# EEZ_DIB_DCP505_r1B3.net
KiCad netlist of a schematic drawn in EAGLE
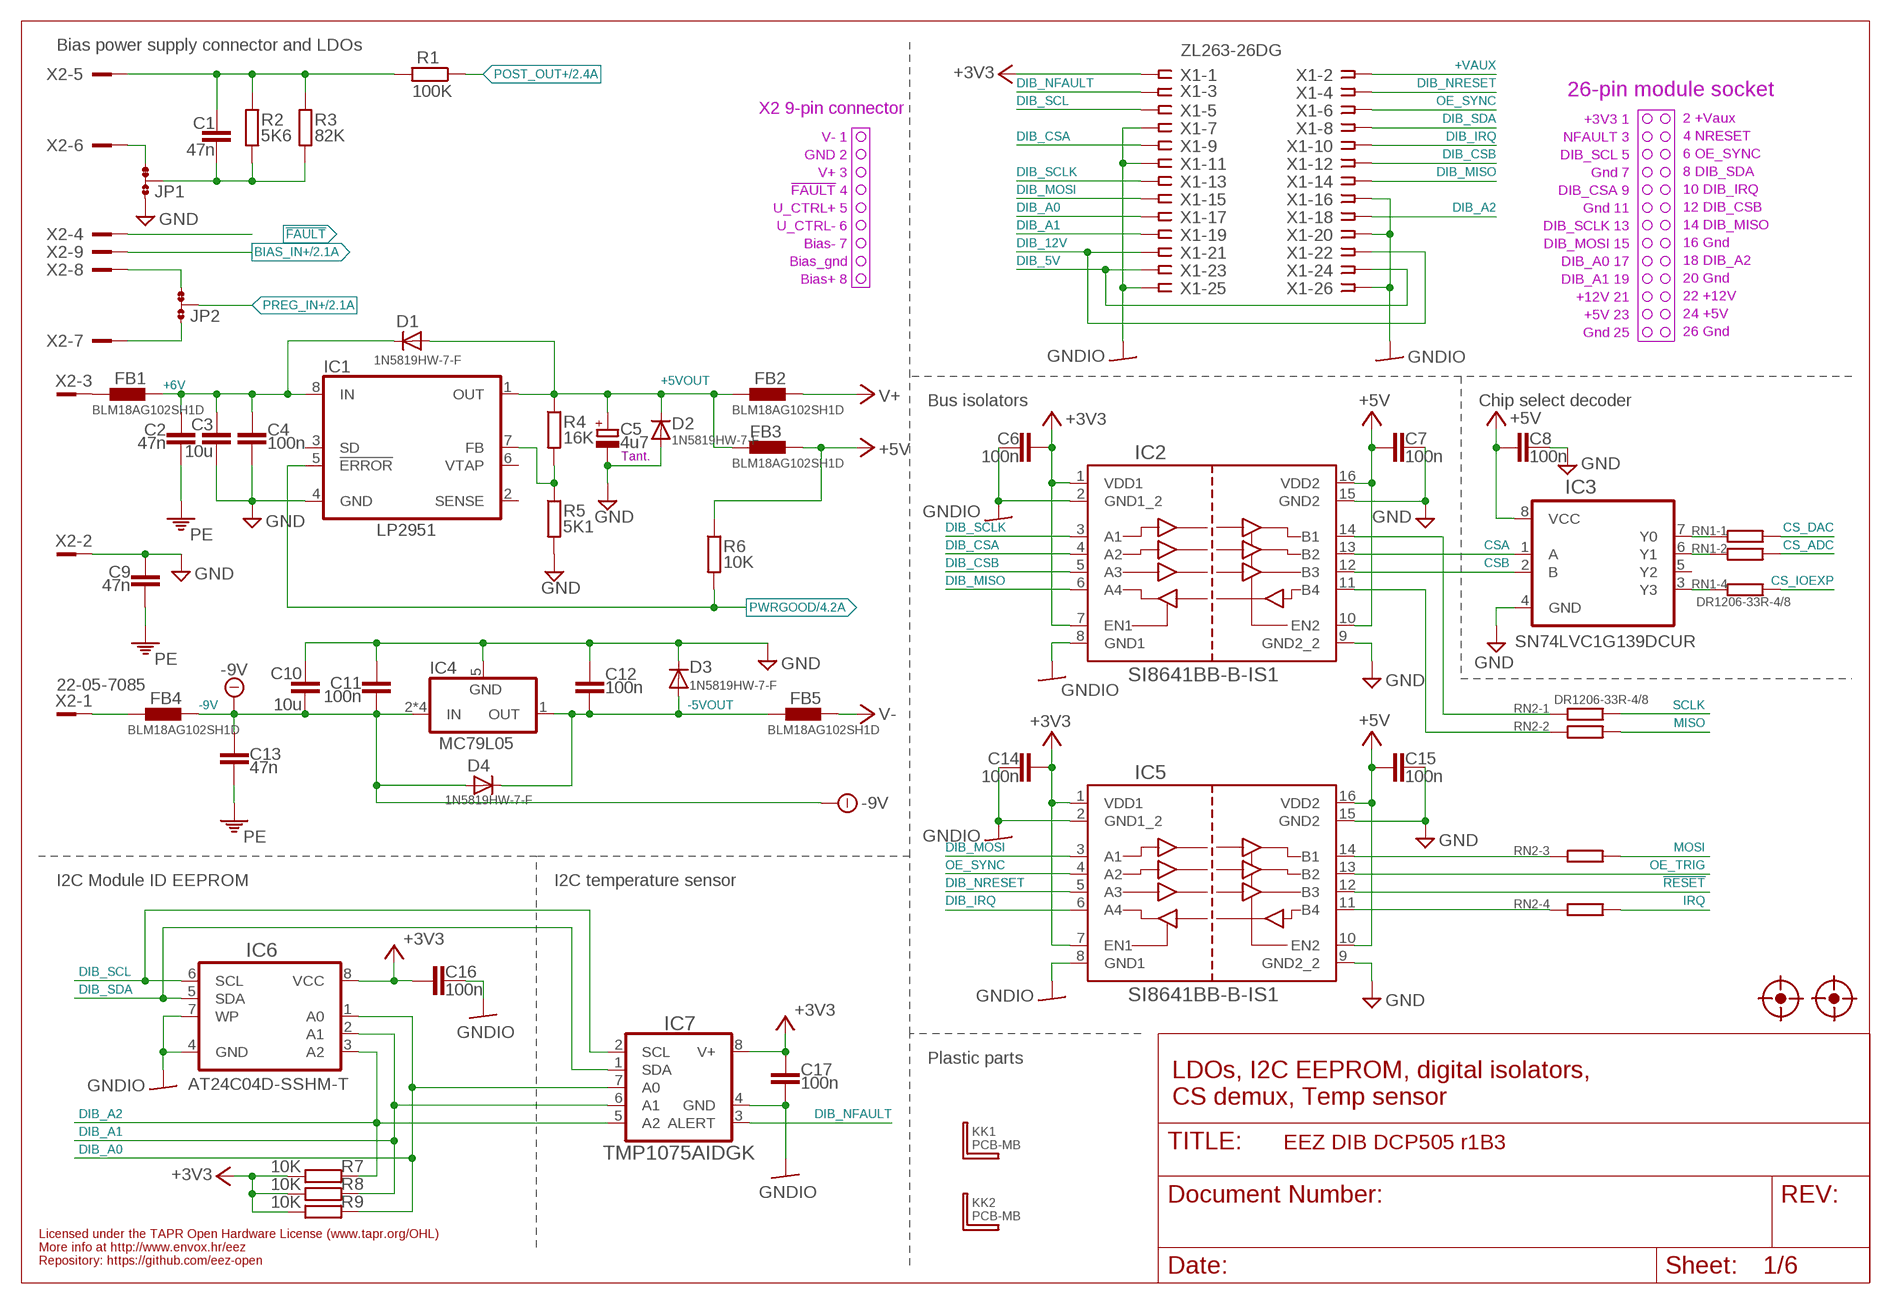
[diagram p0: schematic, sheet 1]
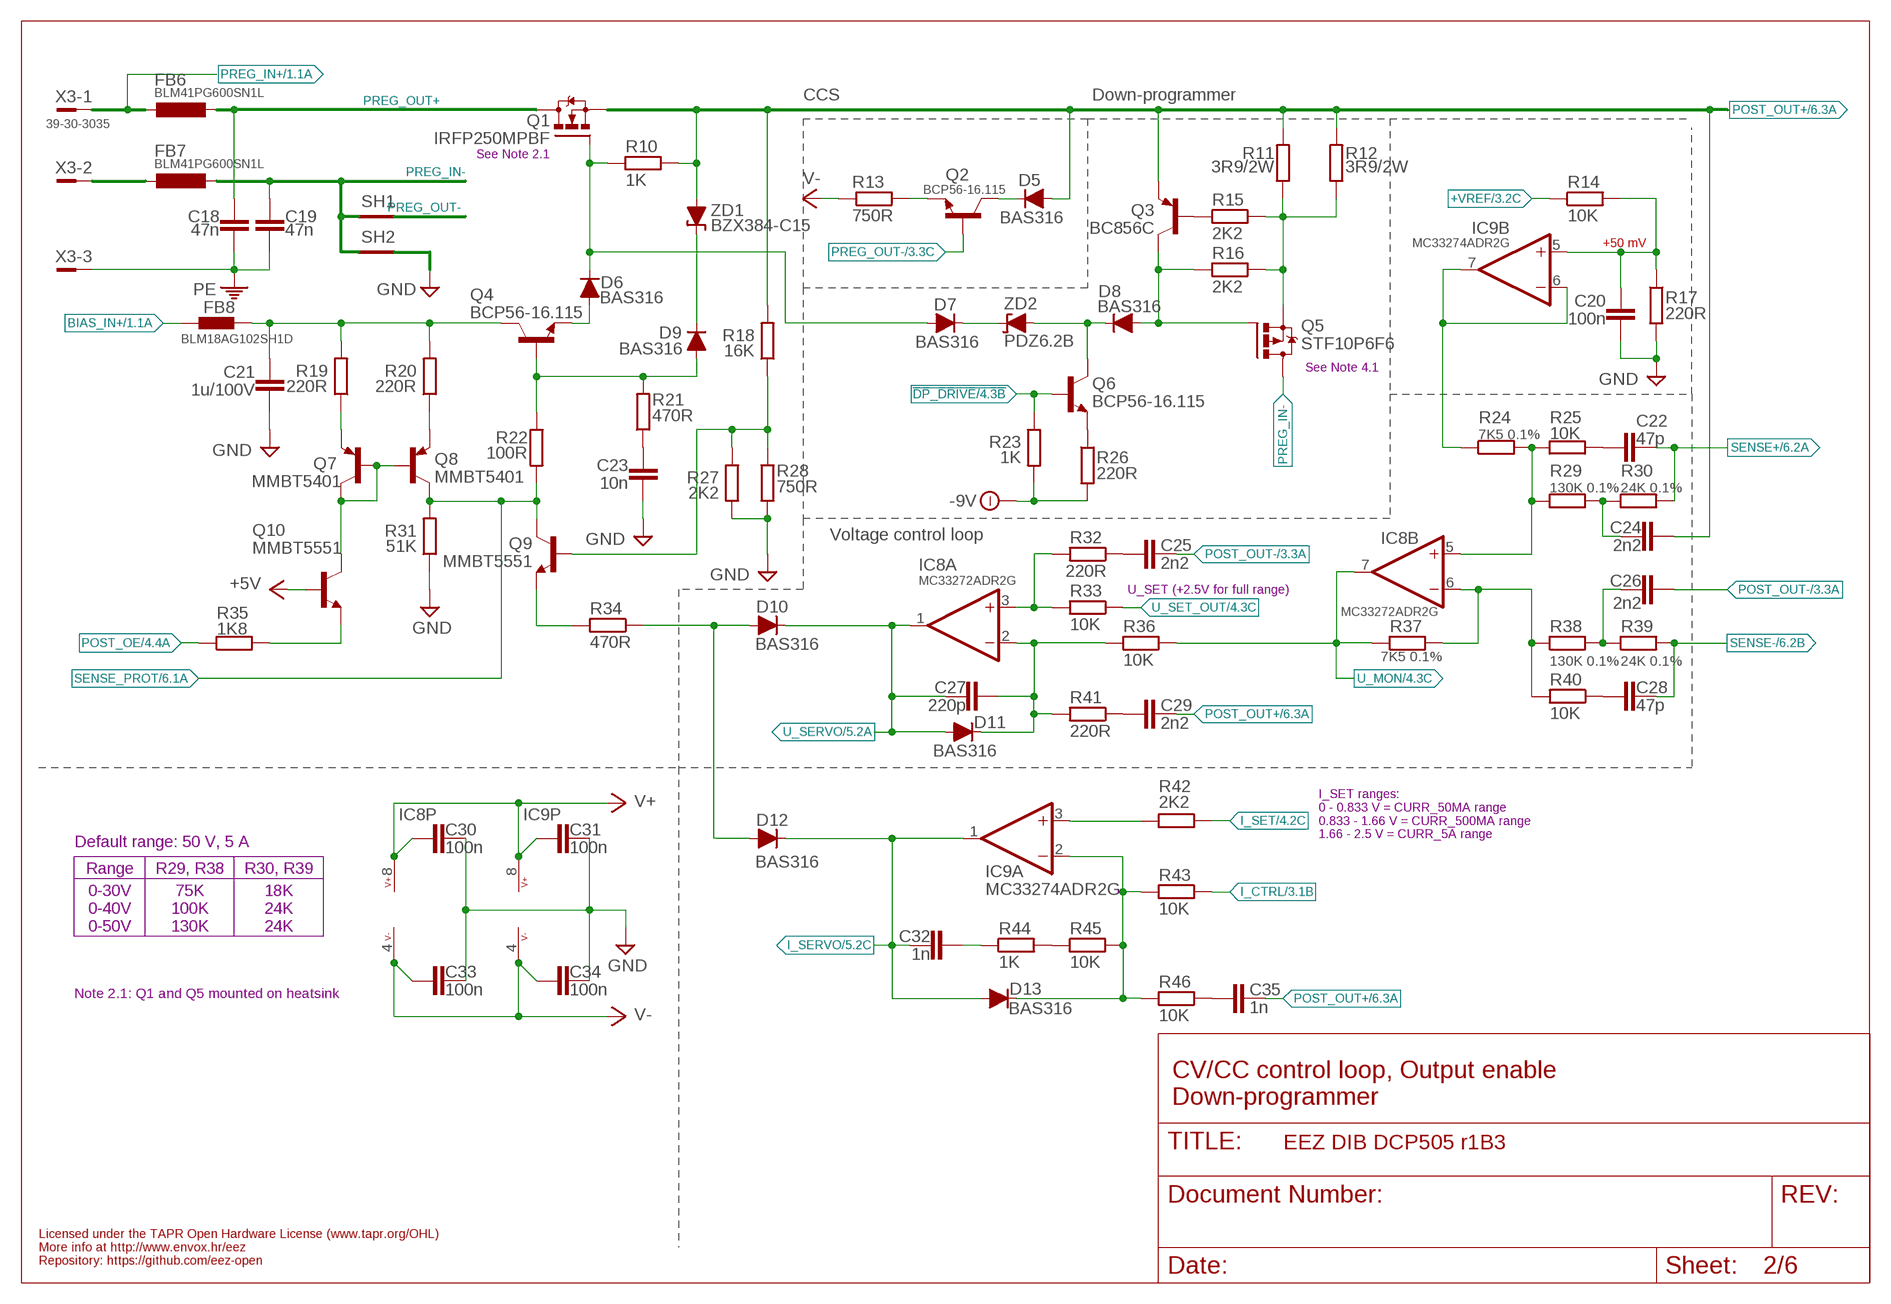
[diagram p1: schematic, sheet 2]
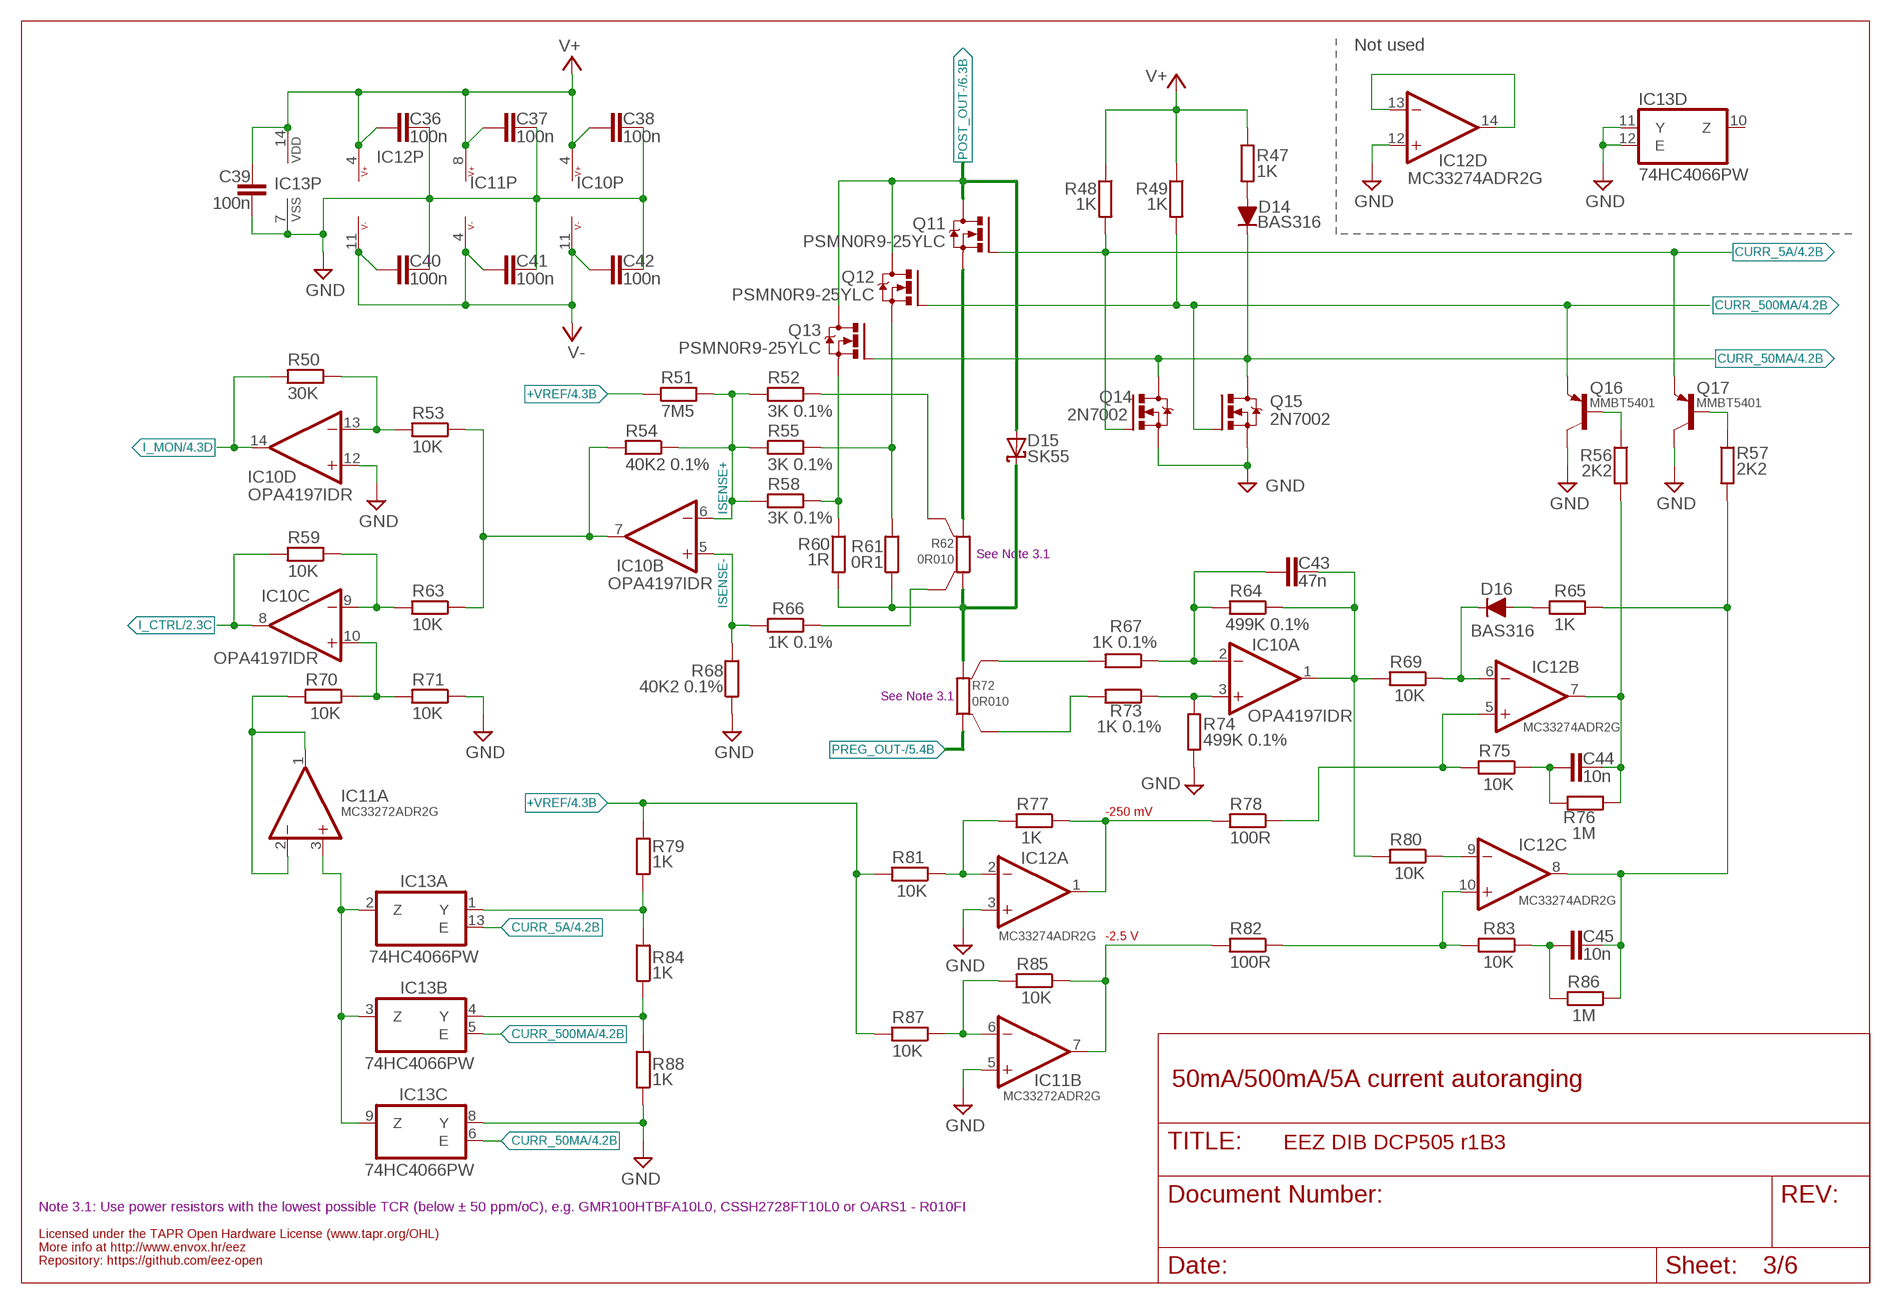
[diagram p2: schematic, sheet 3]
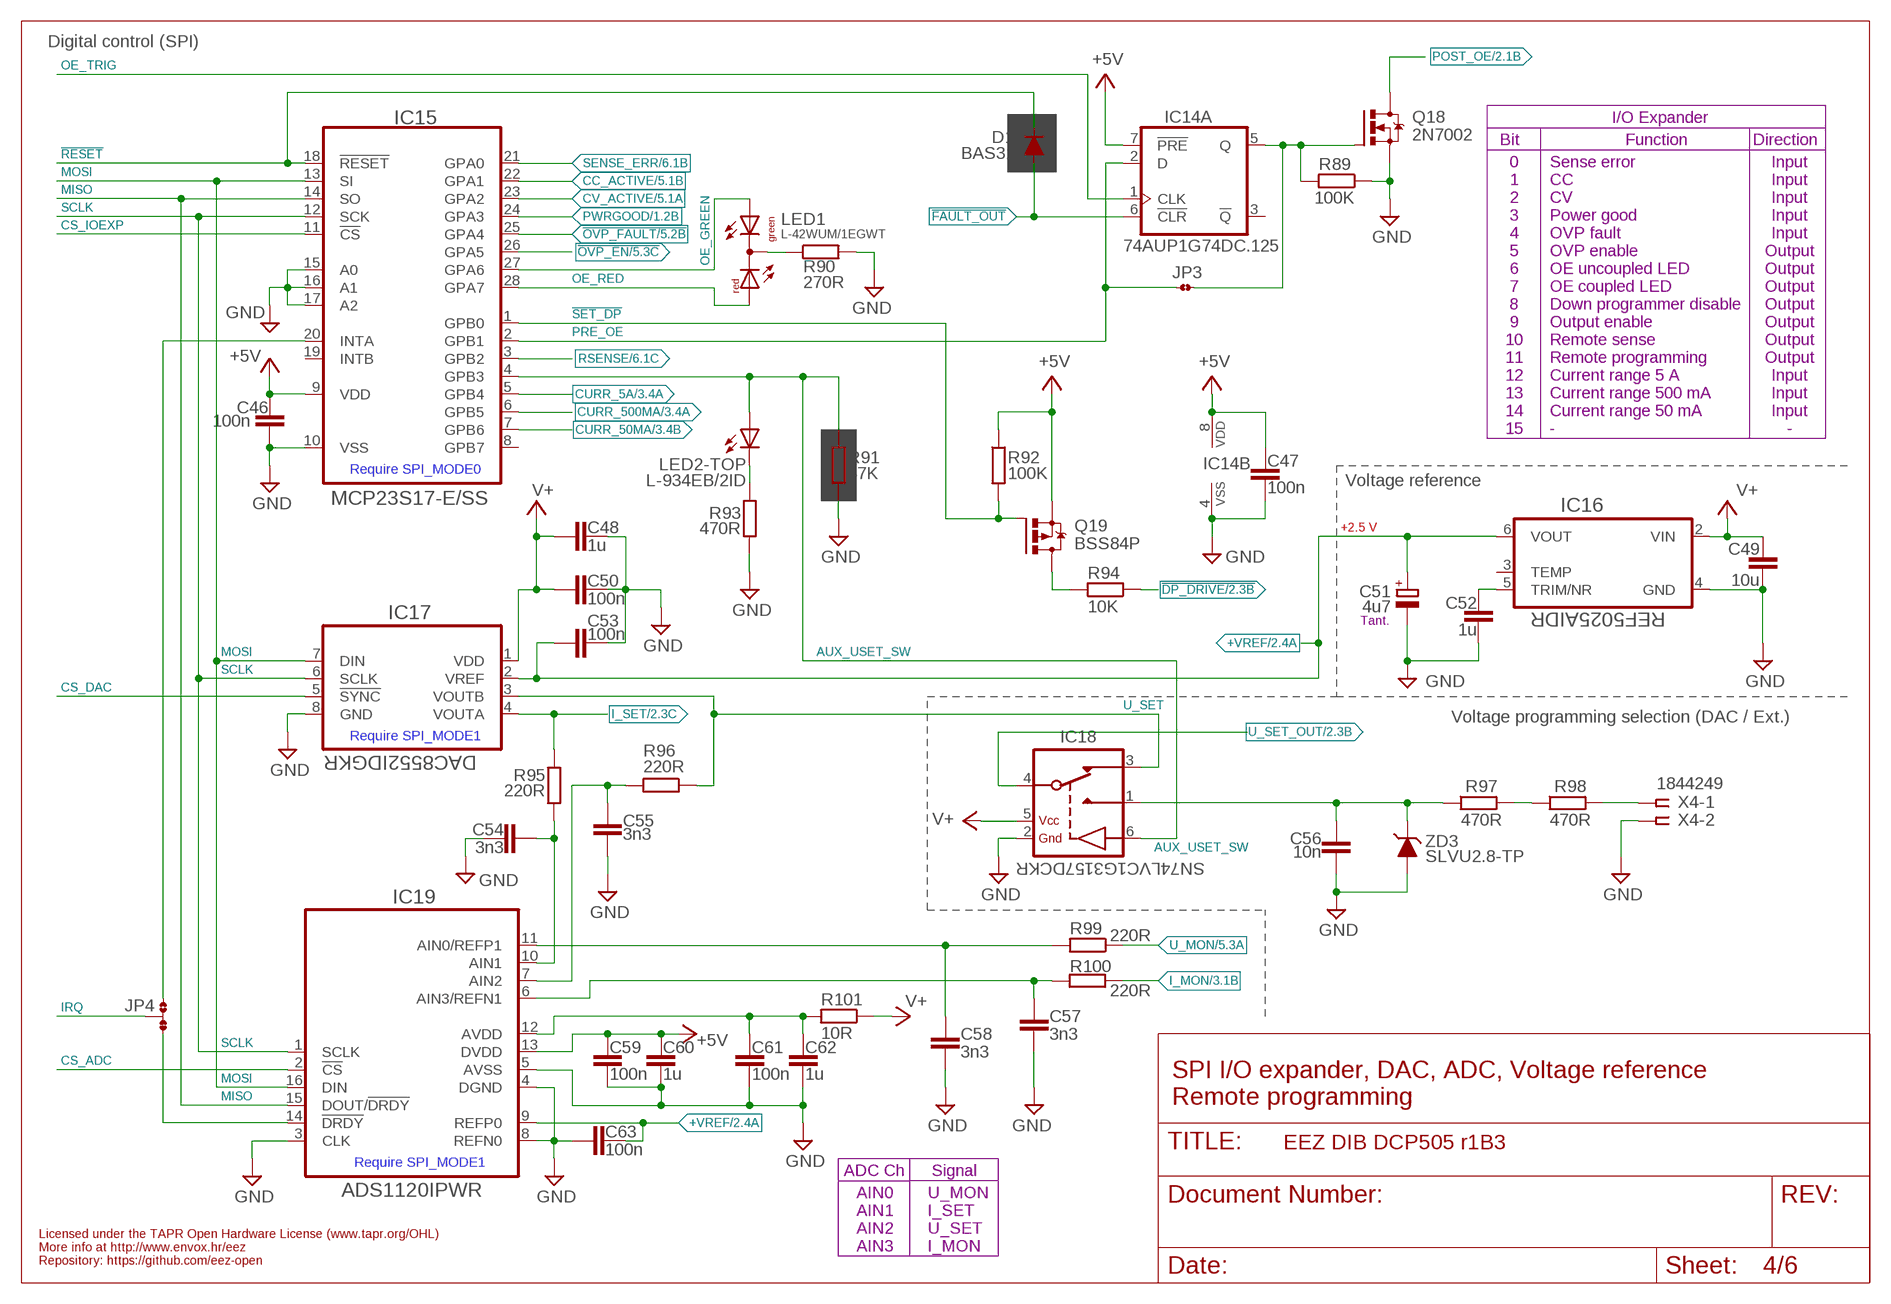
[diagram p3: schematic, sheet 4]
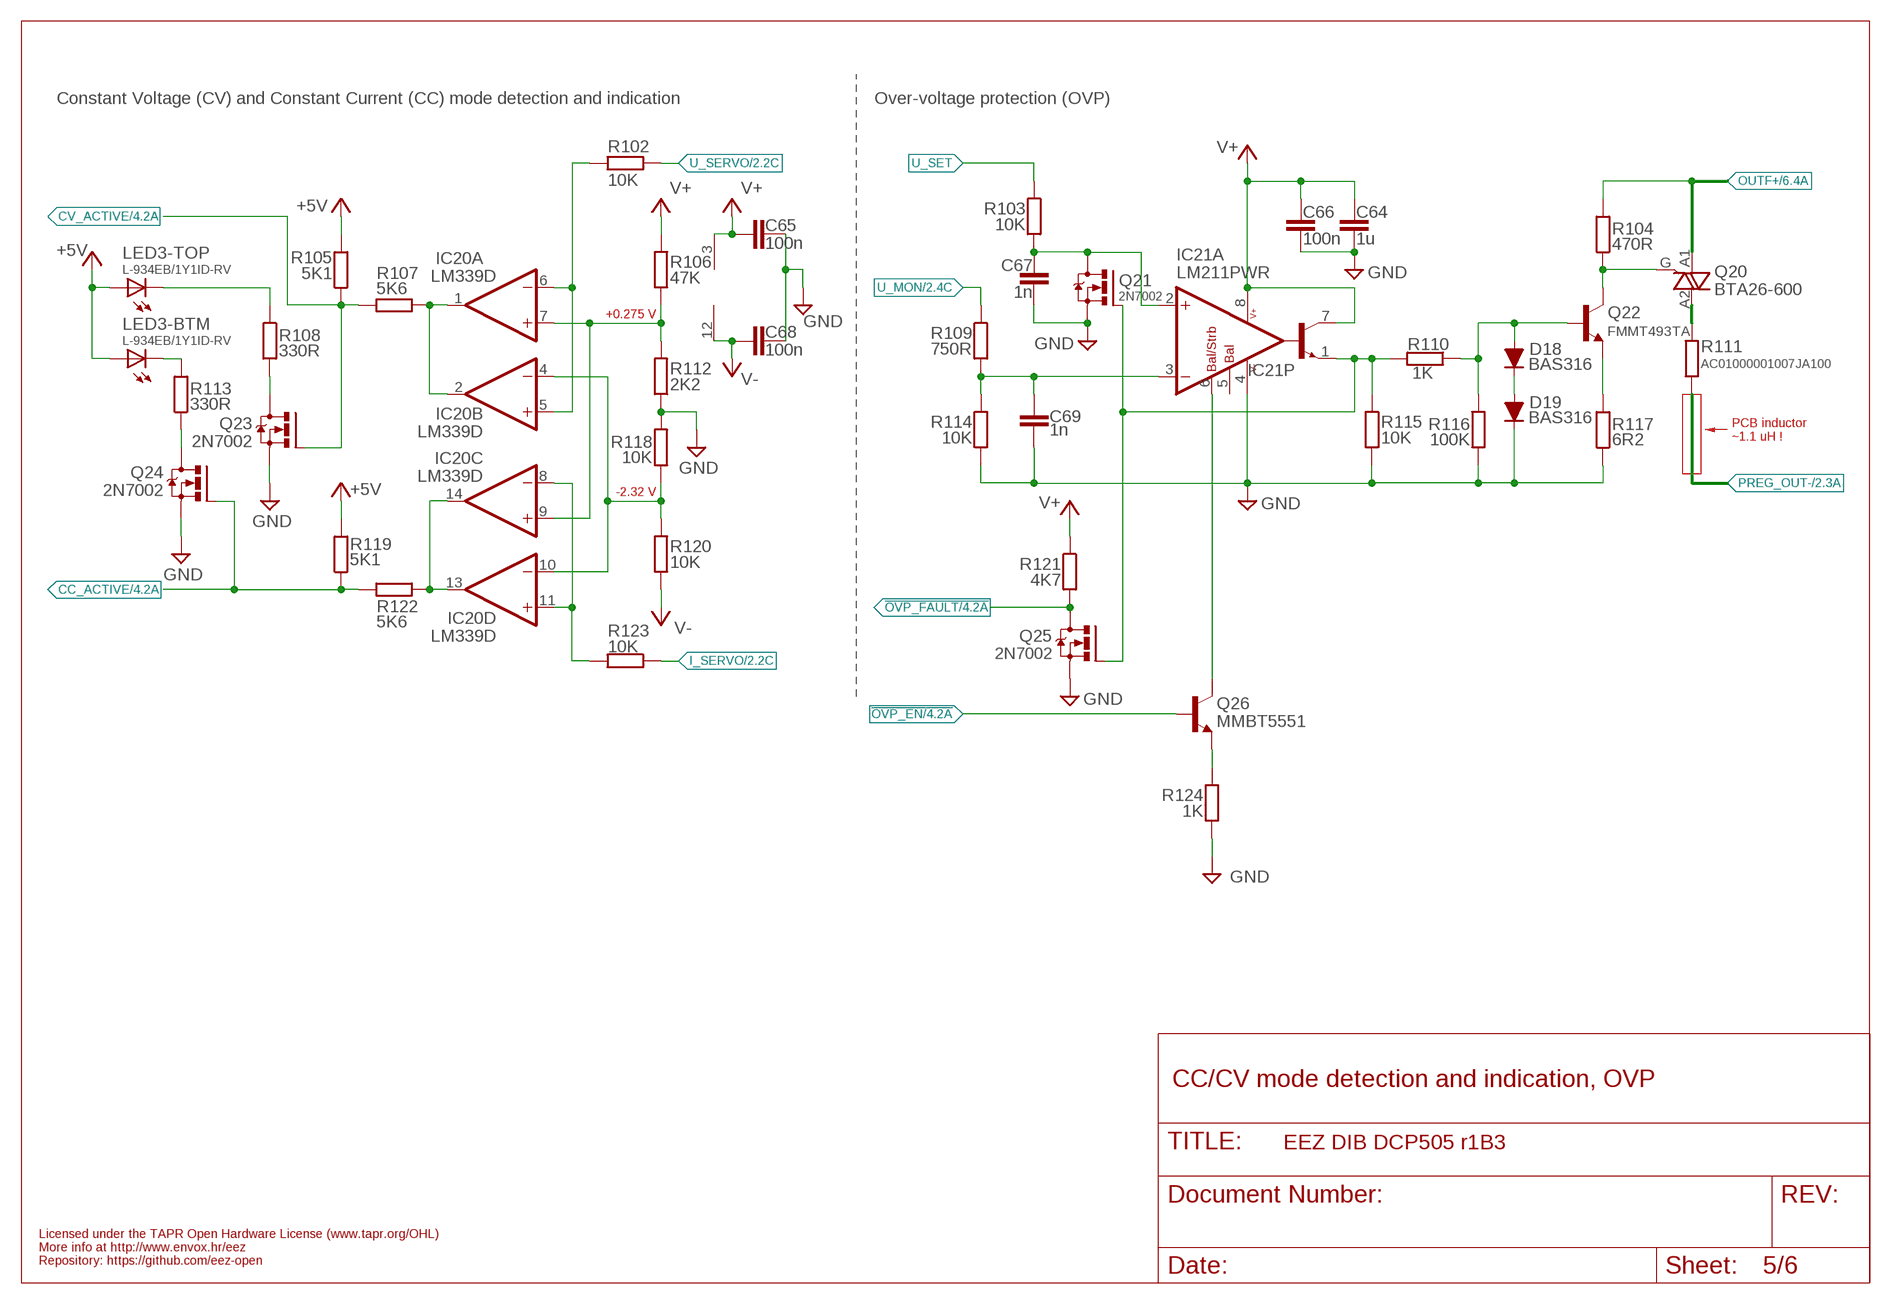
[diagram p4: schematic, sheet 5]
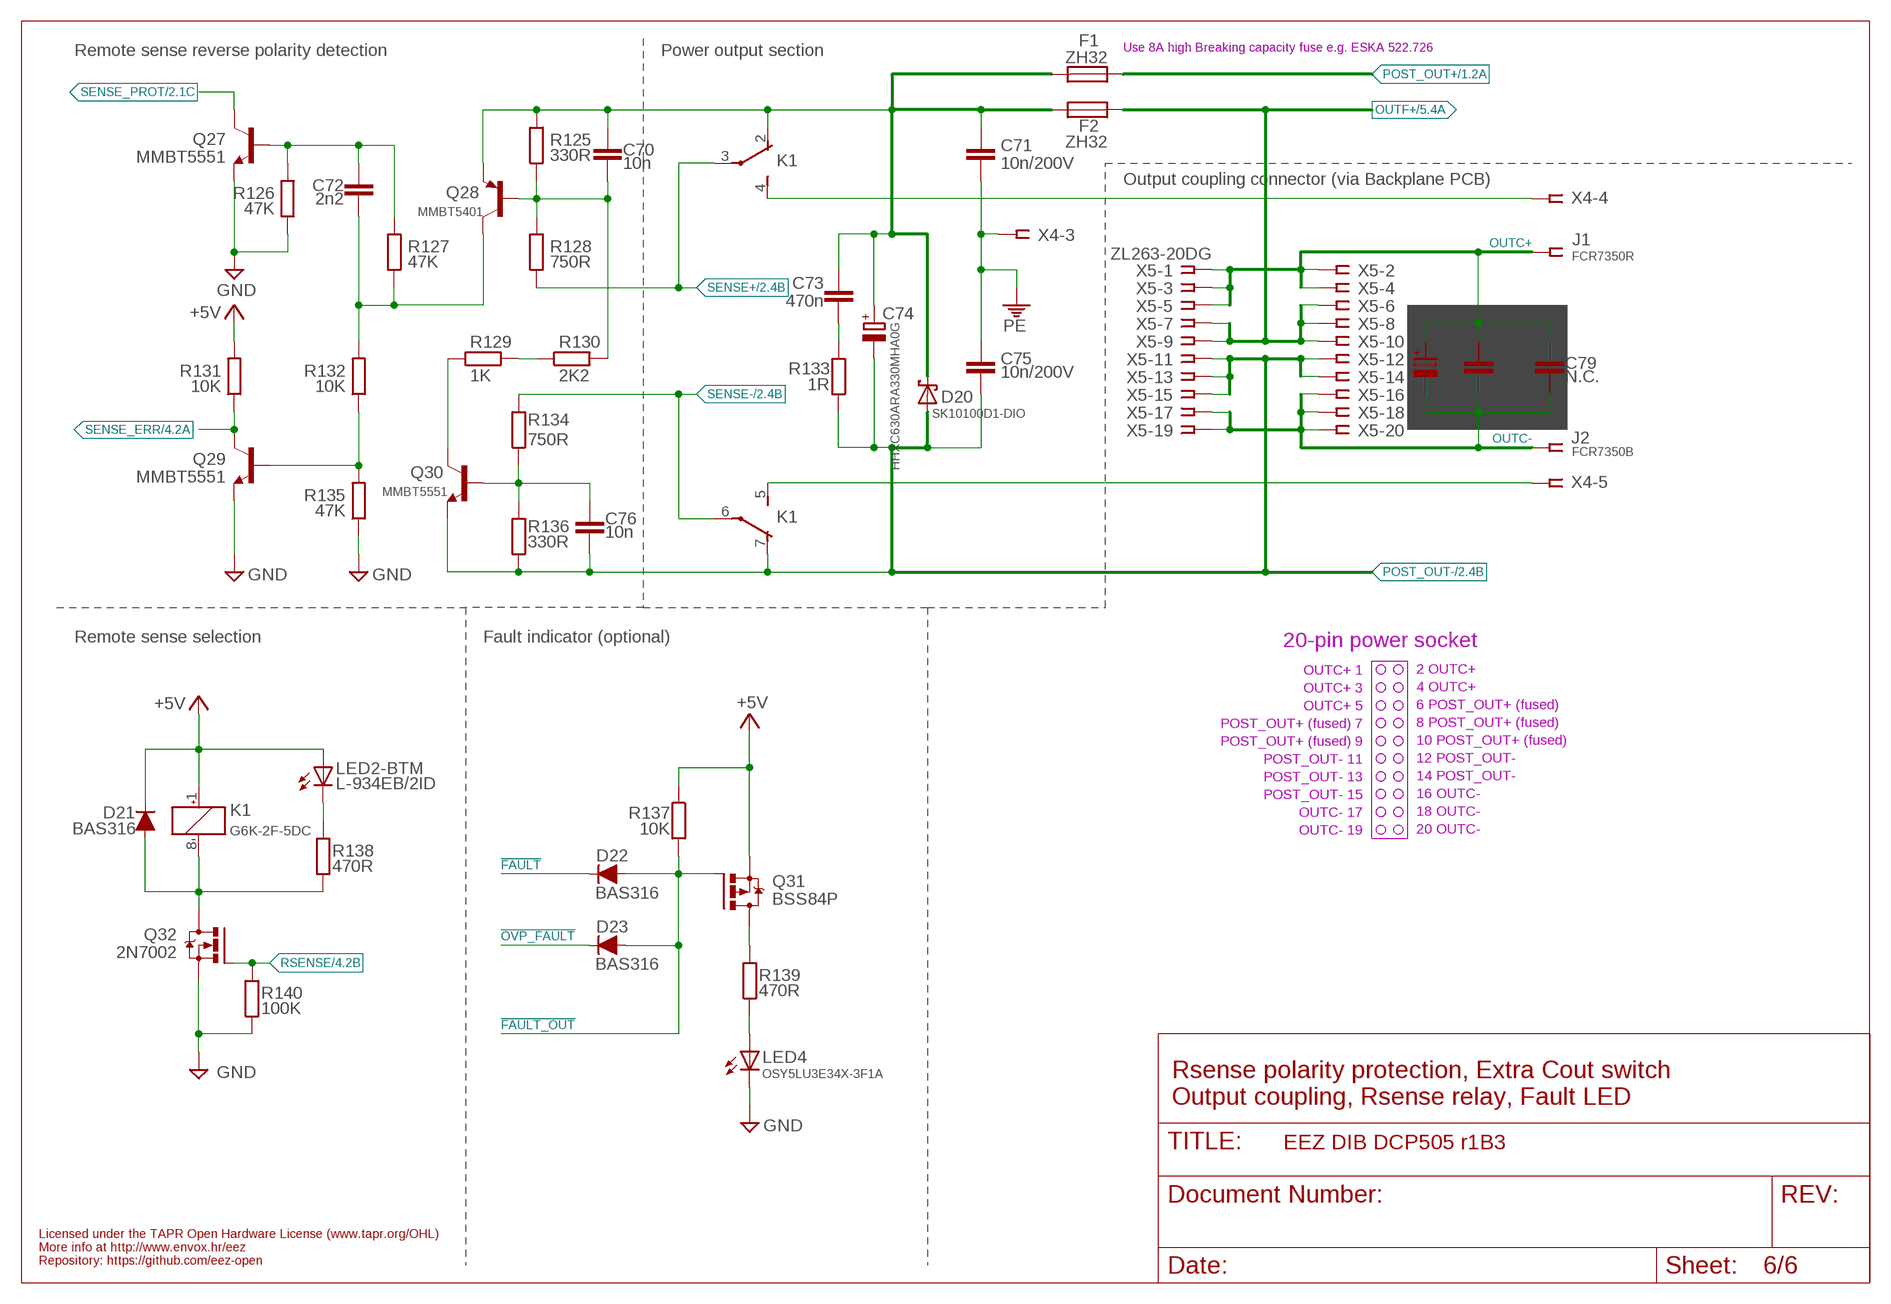
[diagram p5: schematic, sheet 6]

(export (version "E")
  (design (tool "Eeschema 10.0.6"))
  (components
    (comp (ref "C1")
      (value "47n")
      (footprint "eagle-import:C0805")
      (libsource (lib "eagle-import") (part "C-EUC0805"))
    )
    (comp (ref "C2")
      (value "47n")
      (footprint "eagle-import:C1206")
      (libsource (lib "eagle-import") (part "C-EUC1206"))
    )
    (comp (ref "C3")
      (value "10u")
      (footprint "eagle-import:C1206")
      (libsource (lib "eagle-import") (part "C-EUC1206"))
    )
    (comp (ref "C4")
      (value "100n")
      (footprint "eagle-import:C0603")
      (libsource (lib "eagle-import") (part "C-EUC0603"))
    )
    (comp (ref "C5")
      (value "4u7")
      (footprint "eagle-import:EC1206")
      (libsource (lib "eagle-import") (part "ECAP1206"))
    )
    (comp (ref "C6")
      (value "100n")
      (footprint "eagle-import:C0603")
      (libsource (lib "eagle-import") (part "C-EUC0603"))
    )
    (comp (ref "C7")
      (value "100n")
      (footprint "eagle-import:C0603")
      (libsource (lib "eagle-import") (part "C-EUC0603"))
    )
    (comp (ref "C8")
      (value "100n")
      (footprint "eagle-import:C0603")
      (libsource (lib "eagle-import") (part "C-EUC0603"))
    )
    (comp (ref "C9")
      (value "47n")
      (footprint "eagle-import:C1206")
      (libsource (lib "eagle-import") (part "C-EUC1206"))
    )
    (comp (ref "C10")
      (value "10u")
      (footprint "eagle-import:C1206")
      (libsource (lib "eagle-import") (part "C-EUC1206"))
    )
    (comp (ref "C11")
      (value "100n")
      (footprint "eagle-import:C0603")
      (libsource (lib "eagle-import") (part "C-EUC0603"))
    )
    (comp (ref "C12")
      (value "100n")
      (footprint "eagle-import:C0603")
      (libsource (lib "eagle-import") (part "C-EUC0603"))
    )
    (comp (ref "C13")
      (value "47n")
      (footprint "eagle-import:C1206")
      (libsource (lib "eagle-import") (part "C-EUC1206"))
    )
    (comp (ref "C14")
      (value "100n")
      (footprint "eagle-import:C0603")
      (libsource (lib "eagle-import") (part "C-EUC0603"))
    )
    (comp (ref "C15")
      (value "100n")
      (footprint "eagle-import:C0603")
      (libsource (lib "eagle-import") (part "C-EUC0603"))
    )
    (comp (ref "C16")
      (value "100n")
      (footprint "eagle-import:C0603")
      (libsource (lib "eagle-import") (part "C-EUC0603"))
    )
    (comp (ref "C17")
      (value "100n")
      (footprint "eagle-import:C0603")
      (libsource (lib "eagle-import") (part "C-EUC0603"))
    )
    (comp (ref "D1")
      (value "1N5819HW-7-F")
      (footprint "eagle-import:SOD323-W")
      (libsource (lib "eagle-import") (part "DIODE-SOD323-W"))
    )
    (comp (ref "D2")
      (value "1N5819HW-7-F")
      (footprint "eagle-import:SOD323-W")
      (libsource (lib "eagle-import") (part "DIODE-SOD323-W"))
    )
    (comp (ref "D3")
      (value "1N5819HW-7-F")
      (footprint "eagle-import:SOD323-W")
      (libsource (lib "eagle-import") (part "DIODE-SOD323-W"))
    )
    (comp (ref "D4")
      (value "1N5819HW-7-F")
      (footprint "eagle-import:SOD323-W")
      (libsource (lib "eagle-import") (part "DIODE-SOD323-W"))
    )
    (comp (ref "FB1")
      (value "BLM18AG102SH1D")
      (footprint "eagle-import:BEAD0603")
      (libsource (lib "eagle-import") (part "EEZ_inductors_and_transformers_FERRITE_BEAD0603"))
    )
    (comp (ref "FB2")
      (value "BLM18AG102SH1D")
      (footprint "eagle-import:BEAD0603")
      (libsource (lib "eagle-import") (part "EEZ_inductors_and_transformers_FERRITE_BEAD0603"))
    )
    (comp (ref "FB3")
      (value "BLM18AG102SH1D")
      (footprint "eagle-import:BEAD0603")
      (libsource (lib "eagle-import") (part "EEZ_inductors_and_transformers_FERRITE_BEAD0603"))
    )
    (comp (ref "FB4")
      (value "BLM18AG102SH1D")
      (footprint "eagle-import:BEAD0603")
      (libsource (lib "eagle-import") (part "EEZ_inductors_and_transformers_FERRITE_BEAD0603"))
    )
    (comp (ref "FB5")
      (value "BLM18AG102SH1D")
      (footprint "eagle-import:BEAD0603")
      (libsource (lib "eagle-import") (part "EEZ_inductors_and_transformers_FERRITE_BEAD0603"))
    )
    (comp (ref "FM1")
      (value "FIDUCIAL_2")
      (footprint "eagle-import:FIDUCIAL_DUAL")
      (libsource (lib "eagle-import") (part "FIDUCIAL_2"))
    )
    (comp (ref "FM2")
      (value "FIDUCIAL_2")
      (footprint "eagle-import:FIDUCIAL_DUAL")
      (libsource (lib "eagle-import") (part "FIDUCIAL_2"))
    )
    (comp (ref "IC1")
      (value "LP2951")
      (footprint "eagle-import:SOIC127P600X175-8N")
      (libsource (lib "eagle-import") (part "LP2951SO8"))
    )
    (comp (ref "IC2")
      (value "SI8641BB-B-IS1")
      (footprint "eagle-import:SOIC-16")
      (libsource (lib "eagle-import") (part "SI8641NSOIC-16"))
    )
    (comp (ref "IC3")
      (value "SN74LVC1G139DCUR")
      (footprint "eagle-import:DCU8")
      (libsource (lib "eagle-import") (part "SN74LVC1G139-VSSOP"))
    )
    (comp (ref "IC4")
      (value "MC79L05")
      (footprint "eagle-import:SOIC127P600X173-8N")
      (libsource (lib "eagle-import") (part "MC79LXXSOIC"))
    )
    (comp (ref "IC5")
      (value "SI8641BB-B-IS1")
      (footprint "eagle-import:SOIC-16")
      (libsource (lib "eagle-import") (part "SI8641NSOIC-16"))
    )
    (comp (ref "IC6")
      (value "AT24C04D-SSHM-T")
      (footprint "eagle-import:SOIC127P600X173-8N")
      (libsource (lib "eagle-import") (part "AT24CXXSOIC8"))
    )
    (comp (ref "IC7")
      (value "TMP1075AIDGK")
      (footprint "eagle-import:DGK8")
      (libsource (lib "eagle-import") (part "TMPX75DGK"))
    )
    (comp (ref "JP1")
      (value "JP3-CUT")
      (footprint "eagle-import:JP3-CUT")
      (libsource (lib "eagle-import") (part "JP3-CUT"))
    )
    (comp (ref "JP2")
      (value "JP3-CUT")
      (footprint "eagle-import:JP3-CUT")
      (libsource (lib "eagle-import") (part "JP3-CUT"))
    )
    (comp (ref "KK1")
      (value "PCB-MB")
      (footprint "eagle-import:PCB-MB")
      (libsource (lib "eagle-import") (part "PCB-MB"))
    )
    (comp (ref "KK2")
      (value "PCB-MB")
      (footprint "eagle-import:PCB-MB")
      (libsource (lib "eagle-import") (part "PCB-MB"))
    )
    (comp (ref "R1")
      (value "100K")
      (footprint "eagle-import:R0805")
      (libsource (lib "eagle-import") (part "R-EU_R0805"))
    )
    (comp (ref "R2")
      (value "5K6")
      (footprint "eagle-import:R0805")
      (libsource (lib "eagle-import") (part "R-EU_R0805"))
    )
    (comp (ref "R3")
      (value "82K")
      (footprint "eagle-import:R0805")
      (libsource (lib "eagle-import") (part "R-EU_R0805"))
    )
    (comp (ref "R4")
      (value "16K")
      (footprint "eagle-import:R0805")
      (libsource (lib "eagle-import") (part "R-EU_R0805"))
    )
    (comp (ref "R5")
      (value "5K1")
      (footprint "eagle-import:R0805")
      (libsource (lib "eagle-import") (part "R-EU_R0805"))
    )
    (comp (ref "R6")
      (value "10K")
      (footprint "eagle-import:R0805")
      (libsource (lib "eagle-import") (part "R-EU_R0805"))
    )
    (comp (ref "R7")
      (value "10K")
      (footprint "eagle-import:R0805")
      (libsource (lib "eagle-import") (part "R-EU_R0805"))
    )
    (comp (ref "R8")
      (value "10K")
      (footprint "eagle-import:R0805")
      (libsource (lib "eagle-import") (part "R-EU_R0805"))
    )
    (comp (ref "R9")
      (value "10K")
      (footprint "eagle-import:R0805")
      (libsource (lib "eagle-import") (part "R-EU_R0805"))
    )
    (comp (ref "RN1")
      (value "DR1206-33R-4/8")
      (footprint "eagle-import:CAY16")
      (libsource (lib "eagle-import") (part "R_ARRAY4"))
    )
    (comp (ref "RN2")
      (value "DR1206-33R-4/8")
      (footprint "eagle-import:CAY16")
      (libsource (lib "eagle-import") (part "R_ARRAY4"))
    )
    (comp (ref "X1")
      (value "ZL263-26DG")
      (footprint "eagle-import:SSW-113-02-T-D-RA")
      (libsource (lib "eagle-import") (part "SSW-113-02-T-D-RA"))
    )
    (comp (ref "X2")
      (value "22-05-7085")
      (footprint "eagle-import:SPOX_22-05-7095")
      (libsource (lib "eagle-import") (part "SPOX_22-05-7095"))
    )
    (comp (ref "C36")
      (value "100n")
      (footprint "eagle-import:C0603")
      (libsource (lib "eagle-import") (part "C-EUC0603"))
    )
    (comp (ref "C37")
      (value "100n")
      (footprint "eagle-import:C0603")
      (libsource (lib "eagle-import") (part "C-EUC0603"))
    )
    (comp (ref "C38")
      (value "100n")
      (footprint "eagle-import:C0603")
      (libsource (lib "eagle-import") (part "C-EUC0603"))
    )
    (comp (ref "C39")
      (value "100n")
      (footprint "eagle-import:C0603")
      (libsource (lib "eagle-import") (part "C-EUC0603"))
    )
    (comp (ref "C40")
      (value "100n")
      (footprint "eagle-import:C0603")
      (libsource (lib "eagle-import") (part "C-EUC0603"))
    )
    (comp (ref "C41")
      (value "100n")
      (footprint "eagle-import:C0603")
      (libsource (lib "eagle-import") (part "C-EUC0603"))
    )
    (comp (ref "C42")
      (value "100n")
      (footprint "eagle-import:C0603")
      (libsource (lib "eagle-import") (part "C-EUC0603"))
    )
    (comp (ref "C43")
      (value "47n")
      (footprint "eagle-import:C0805")
      (libsource (lib "eagle-import") (part "C-EUC0805"))
    )
    (comp (ref "C44")
      (value "10n")
      (footprint "eagle-import:C0805")
      (libsource (lib "eagle-import") (part "C-EUC0805"))
    )
    (comp (ref "C45")
      (value "10n")
      (footprint "eagle-import:C0805")
      (libsource (lib "eagle-import") (part "C-EUC0805"))
    )
    (comp (ref "D14")
      (value "BAS316")
      (footprint "eagle-import:SOD323-R")
      (libsource (lib "eagle-import") (part "DIODESOD323R"))
    )
    (comp (ref "D15")
      (value "SK55")
      (footprint "eagle-import:SMB")
      (libsource (lib "eagle-import") (part "SCHOTTKYSMB"))
    )
    (comp (ref "D16")
      (value "BAS316")
      (footprint "eagle-import:SOD323-R")
      (libsource (lib "eagle-import") (part "DIODESOD323R"))
    )
    (comp (ref "IC10")
      (value "OPA4197IDR")
      (footprint "eagle-import:SOIC127P600X175-14N")
      (fields (field (name "MPN") "TL074ACD"))
      (libsource (lib "eagle-import") (part "TL074SOIC14"))
    )
    (comp (ref "IC11")
      (value "MC33272ADR2G")
      (footprint "eagle-import:SOIC127P600X173-8N")
      (libsource (lib "eagle-import") (part "TL072SOIC8"))
    )
    (comp (ref "IC12")
      (value "MC33274ADR2G")
      (footprint "eagle-import:SOIC127P600X175-14N")
      (fields (field (name "MPN") "TL074ACD"))
      (libsource (lib "eagle-import") (part "TL074SOIC14"))
    )
    (comp (ref "IC13")
      (value "74HC4066PW")
      (footprint "eagle-import:SOP65P640X120-14N")
      (libsource (lib "eagle-import") (part "74HC4066PW"))
    )
    (comp (ref "Q11")
      (value "PSMN0R9-25YLC")
      (footprint "eagle-import:SOT669")
      (libsource (lib "eagle-import") (part "N-MOSFETLFPAK"))
    )
    (comp (ref "Q12")
      (value "PSMN0R9-25YLC")
      (footprint "eagle-import:SOT669")
      (libsource (lib "eagle-import") (part "N-MOSFETLFPAK"))
    )
    (comp (ref "Q13")
      (value "PSMN0R9-25YLC")
      (footprint "eagle-import:SOT669")
      (libsource (lib "eagle-import") (part "N-MOSFETLFPAK"))
    )
    (comp (ref "Q14")
      (value "2N7002")
      (footprint "eagle-import:SOT103P240X110-3N")
      (fields
        (field (name "MPN") "2N7002-7-F")
        (field (name "MPN_1") "2N7002-7-F")
        (field (name "OC_FARNELL") "1713823")
        (field (name "OC_NEWARK") "25R5679")
        (field (name "PACKAGE") "SOT-23-3")
        (field (name "SUPPLIER") "DIODES INC.")
      )
      (libsource (lib "eagle-import") (part "2N7002"))
    )
    (comp (ref "Q15")
      (value "2N7002")
      (footprint "eagle-import:SOT103P240X110-3N")
      (fields
        (field (name "MPN") "2N7002-7-F")
        (field (name "MPN_1") "2N7002-7-F")
        (field (name "OC_FARNELL") "1713823")
        (field (name "OC_NEWARK") "25R5679")
        (field (name "PACKAGE") "SOT-23-3")
        (field (name "SUPPLIER") "DIODES INC.")
      )
      (libsource (lib "eagle-import") (part "2N7002"))
    )
    (comp (ref "Q16")
      (value "MMBT5401")
      (footprint "eagle-import:SOT23-BEC")
      (libsource (lib "eagle-import") (part "-PNP-SOT23-BECBC857B"))
    )
    (comp (ref "Q17")
      (value "MMBT5401")
      (footprint "eagle-import:SOT23-BEC")
      (libsource (lib "eagle-import") (part "-PNP-SOT23-BECBC857B"))
    )
    (comp (ref "R47")
      (value "1K")
      (footprint "eagle-import:R0805")
      (libsource (lib "eagle-import") (part "R-EU_R0805"))
    )
    (comp (ref "R48")
      (value "1K")
      (footprint "eagle-import:R0805")
      (libsource (lib "eagle-import") (part "R-EU_R0805"))
    )
    (comp (ref "R49")
      (value "1K")
      (footprint "eagle-import:R0805")
      (libsource (lib "eagle-import") (part "R-EU_R0805"))
    )
    (comp (ref "R50")
      (value "30K")
      (footprint "eagle-import:R0805")
      (libsource (lib "eagle-import") (part "R-EU_R0805"))
    )
    (comp (ref "R51")
      (value "7M5")
      (footprint "eagle-import:R0603")
      (libsource (lib "eagle-import") (part "R-EU_R0603"))
    )
    (comp (ref "R52")
      (value "3K 0.1%")
      (footprint "eagle-import:R0603")
      (libsource (lib "eagle-import") (part "R-EU_R0603"))
    )
    (comp (ref "R53")
      (value "10K")
      (footprint "eagle-import:R0805")
      (libsource (lib "eagle-import") (part "R-EU_R0805"))
    )
    (comp (ref "R54")
      (value "40K2 0.1%")
      (footprint "eagle-import:R0603")
      (libsource (lib "eagle-import") (part "R-EU_R0603"))
    )
    (comp (ref "R55")
      (value "3K 0.1%")
      (footprint "eagle-import:R0603")
      (libsource (lib "eagle-import") (part "R-EU_R0603"))
    )
    (comp (ref "R56")
      (value "2K2")
      (footprint "eagle-import:R0805")
      (libsource (lib "eagle-import") (part "R-EU_R0805"))
    )
    (comp (ref "R57")
      (value "2K2")
      (footprint "eagle-import:R0805")
      (libsource (lib "eagle-import") (part "R-EU_R0805"))
    )
    (comp (ref "R58")
      (value "3K 0.1%")
      (footprint "eagle-import:R0603")
      (libsource (lib "eagle-import") (part "R-EU_R0603"))
    )
    (comp (ref "R59")
      (value "10K")
      (footprint "eagle-import:R0805")
      (libsource (lib "eagle-import") (part "R-EU_R0805"))
    )
    (comp (ref "R60")
      (value "1R")
      (footprint "eagle-import:R0805")
      (libsource (lib "eagle-import") (part "R-EU_R0805"))
    )
    (comp (ref "R61")
      (value "0R1")
      (footprint "eagle-import:R1206")
      (libsource (lib "eagle-import") (part "R-EU_R1206"))
    )
    (comp (ref "R62")
      (value "0R010")
      (footprint "eagle-import:R_H2728")
      (libsource (lib "eagle-import") (part "R-EU_4WIREH2728"))
    )
    (comp (ref "R63")
      (value "10K")
      (footprint "eagle-import:R0805")
      (libsource (lib "eagle-import") (part "R-EU_R0805"))
    )
    (comp (ref "R64")
      (value "499K 0.1%")
      (footprint "eagle-import:R0603")
      (libsource (lib "eagle-import") (part "R-EU_R0603"))
    )
    (comp (ref "R65")
      (value "1K")
      (footprint "eagle-import:R0805")
      (libsource (lib "eagle-import") (part "R-EU_R0805"))
    )
    (comp (ref "R66")
      (value "1K 0.1%")
      (footprint "eagle-import:R0603")
      (libsource (lib "eagle-import") (part "R-EU_R0603"))
    )
    (comp (ref "R67")
      (value "1K 0.1%")
      (footprint "eagle-import:R0603")
      (libsource (lib "eagle-import") (part "R-EU_R0603"))
    )
    (comp (ref "R68")
      (value "40K2 0.1%")
      (footprint "eagle-import:R0603")
      (libsource (lib "eagle-import") (part "R-EU_R0603"))
    )
    (comp (ref "R69")
      (value "10K")
      (footprint "eagle-import:R0805")
      (libsource (lib "eagle-import") (part "R-EU_R0805"))
    )
    (comp (ref "R70")
      (value "10K")
      (footprint "eagle-import:R0805")
      (libsource (lib "eagle-import") (part "R-EU_R0805"))
    )
    (comp (ref "R71")
      (value "10K")
      (footprint "eagle-import:R0805")
      (libsource (lib "eagle-import") (part "R-EU_R0805"))
    )
    (comp (ref "R72")
      (value "0R010")
      (footprint "eagle-import:R_H2728")
      (libsource (lib "eagle-import") (part "R-EU_4WIREH2728"))
    )
    (comp (ref "R73")
      (value "1K 0.1%")
      (footprint "eagle-import:R0603")
      (libsource (lib "eagle-import") (part "R-EU_R0603"))
    )
    (comp (ref "R74")
      (value "499K 0.1%")
      (footprint "eagle-import:R0603")
      (libsource (lib "eagle-import") (part "R-EU_R0603"))
    )
    (comp (ref "R75")
      (value "10K")
      (footprint "eagle-import:R0805")
      (libsource (lib "eagle-import") (part "R-EU_R0805"))
    )
    (comp (ref "R76")
      (value "1M")
      (footprint "eagle-import:R0805")
      (libsource (lib "eagle-import") (part "R-EU_R0805"))
    )
    (comp (ref "R77")
      (value "1K")
      (footprint "eagle-import:R0805")
      (libsource (lib "eagle-import") (part "R-EU_R0805"))
    )
    (comp (ref "R78")
      (value "100R")
      (footprint "eagle-import:R0805")
      (libsource (lib "eagle-import") (part "R-EU_R0805"))
    )
    (comp (ref "R79")
      (value "1K")
      (footprint "eagle-import:R0805")
      (libsource (lib "eagle-import") (part "R-EU_R0805"))
    )
    (comp (ref "R80")
      (value "10K")
      (footprint "eagle-import:R0805")
      (libsource (lib "eagle-import") (part "R-EU_R0805"))
    )
    (comp (ref "R81")
      (value "10K")
      (footprint "eagle-import:R0805")
      (libsource (lib "eagle-import") (part "R-EU_R0805"))
    )
    (comp (ref "R82")
      (value "100R")
      (footprint "eagle-import:R0805")
      (libsource (lib "eagle-import") (part "R-EU_R0805"))
    )
    (comp (ref "R83")
      (value "10K")
      (footprint "eagle-import:R0805")
      (libsource (lib "eagle-import") (part "R-EU_R0805"))
    )
    (comp (ref "R84")
      (value "1K")
      (footprint "eagle-import:R0805")
      (libsource (lib "eagle-import") (part "R-EU_R0805"))
    )
    (comp (ref "R85")
      (value "10K")
      (footprint "eagle-import:R0805")
      (libsource (lib "eagle-import") (part "R-EU_R0805"))
    )
    (comp (ref "R86")
      (value "1M")
      (footprint "eagle-import:R0805")
      (libsource (lib "eagle-import") (part "R-EU_R0805"))
    )
    (comp (ref "R87")
      (value "10K")
      (footprint "eagle-import:R0805")
      (libsource (lib "eagle-import") (part "R-EU_R0805"))
    )
    (comp (ref "R88")
      (value "1K")
      (footprint "eagle-import:R0805")
      (libsource (lib "eagle-import") (part "R-EU_R0805"))
    )
    (comp (ref "C18")
      (value "47n")
      (footprint "eagle-import:C1206")
      (libsource (lib "eagle-import") (part "C-EUC1206"))
    )
    (comp (ref "C19")
      (value "47n")
      (footprint "eagle-import:C1206")
      (libsource (lib "eagle-import") (part "C-EUC1206"))
    )
    (comp (ref "C20")
      (value "100n")
      (footprint "eagle-import:C0603")
      (libsource (lib "eagle-import") (part "C-EUC0603"))
    )
    (comp (ref "C21")
      (value "1u/100V")
      (footprint "eagle-import:C1206")
      (libsource (lib "eagle-import") (part "C-EUC1206"))
    )
    (comp (ref "C22")
      (value "47p")
      (footprint "eagle-import:C0805")
      (libsource (lib "eagle-import") (part "C-EUC0805"))
    )
    (comp (ref "C23")
      (value "10n")
      (footprint "eagle-import:C0805")
      (libsource (lib "eagle-import") (part "C-EUC0805"))
    )
    (comp (ref "C24")
      (value "2n2")
      (footprint "eagle-import:C0805")
      (libsource (lib "eagle-import") (part "C-EUC0805"))
    )
    (comp (ref "C25")
      (value "2n2")
      (footprint "eagle-import:C0805")
      (libsource (lib "eagle-import") (part "C-EUC0805"))
    )
    (comp (ref "C26")
      (value "2n2")
      (footprint "eagle-import:C0805")
      (libsource (lib "eagle-import") (part "C-EUC0805"))
    )
    (comp (ref "C27")
      (value "220p")
      (footprint "eagle-import:C0805")
      (libsource (lib "eagle-import") (part "C-EUC0805"))
    )
    (comp (ref "C28")
      (value "47p")
      (footprint "eagle-import:C0805")
      (libsource (lib "eagle-import") (part "C-EUC0805"))
    )
    (comp (ref "C29")
      (value "2n2")
      (footprint "eagle-import:C0805")
      (libsource (lib "eagle-import") (part "C-EUC0805"))
    )
    (comp (ref "C30")
      (value "100n")
      (footprint "eagle-import:C0603")
      (libsource (lib "eagle-import") (part "C-EUC0603"))
    )
    (comp (ref "C31")
      (value "100n")
      (footprint "eagle-import:C0603")
      (libsource (lib "eagle-import") (part "C-EUC0603"))
    )
    (comp (ref "C32")
      (value "1n")
      (footprint "eagle-import:C0805")
      (libsource (lib "eagle-import") (part "C-EUC0805"))
    )
    (comp (ref "C33")
      (value "100n")
      (footprint "eagle-import:C0603")
      (libsource (lib "eagle-import") (part "C-EUC0603"))
    )
    (comp (ref "C34")
      (value "100n")
      (footprint "eagle-import:C0603")
      (libsource (lib "eagle-import") (part "C-EUC0603"))
    )
    (comp (ref "C35")
      (value "1n")
      (footprint "eagle-import:C0805")
      (libsource (lib "eagle-import") (part "C-EUC0805"))
    )
    (comp (ref "D5")
      (value "BAS316")
      (footprint "eagle-import:SOD323-R")
      (libsource (lib "eagle-import") (part "DIODESOD323R"))
    )
    (comp (ref "D6")
      (value "BAS316")
      (footprint "eagle-import:SOD323-R")
      (libsource (lib "eagle-import") (part "DIODESOD323R"))
    )
    (comp (ref "D7")
      (value "BAS316")
      (footprint "eagle-import:SOD323-R")
      (libsource (lib "eagle-import") (part "DIODESOD323R"))
    )
    (comp (ref "D8")
      (value "BAS316")
      (footprint "eagle-import:SOD323-R")
      (libsource (lib "eagle-import") (part "DIODESOD323R"))
    )
    (comp (ref "D9")
      (value "BAS316")
      (footprint "eagle-import:SOD323-R")
      (libsource (lib "eagle-import") (part "DIODESOD323R"))
    )
    (comp (ref "D10")
      (value "BAS316")
      (footprint "eagle-import:SOD323-R")
      (libsource (lib "eagle-import") (part "DIODESOD323R"))
    )
    (comp (ref "D11")
      (value "BAS316")
      (footprint "eagle-import:SOD323-R")
      (libsource (lib "eagle-import") (part "DIODESOD323R"))
    )
    (comp (ref "D12")
      (value "BAS316")
      (footprint "eagle-import:SOD323-R")
      (libsource (lib "eagle-import") (part "DIODESOD323R"))
    )
    (comp (ref "D13")
      (value "BAS316")
      (footprint "eagle-import:SOD323-R")
      (libsource (lib "eagle-import") (part "DIODESOD323R"))
    )
    (comp (ref "FB6")
      (value "BLM41PG600SN1L")
      (footprint "eagle-import:L1812")
      (libsource (lib "eagle-import") (part "L-EUL1812"))
    )
    (comp (ref "FB7")
      (value "BLM41PG600SN1L")
      (footprint "eagle-import:L1812")
      (libsource (lib "eagle-import") (part "L-EUL1812"))
    )
    (comp (ref "FB8")
      (value "BLM18AG102SH1D")
      (footprint "eagle-import:BEAD0603")
      (libsource (lib "eagle-import") (part "EEZ_inductors_and_transformers_FERRITE_BEAD0603"))
    )
    (comp (ref "IC8")
      (value "MC33272ADR2G")
      (footprint "eagle-import:SOIC127P600X173-8N")
      (libsource (lib "eagle-import") (part "TL072SOIC8"))
    )
    (comp (ref "IC9")
      (value "MC33274ADR2G")
      (footprint "eagle-import:SOIC127P600X173-8N")
      (libsource (lib "eagle-import") (part "TL072SOIC8"))
    )
    (comp (ref "Q1")
      (value "IRFP250MPBF")
      (footprint "eagle-import:TO247BH-CLR2")
      (libsource (lib "eagle-import") (part "IRFP240MIRROR2"))
    )
    (comp (ref "Q2")
      (value "BCP56-16.115")
      (footprint "eagle-import:SOT230P700X180-4N")
      (libsource (lib "eagle-import") (part "BCP56"))
    )
    (comp (ref "Q3")
      (value "BC856C")
      (footprint "eagle-import:SOT23-BEC")
      (libsource (lib "eagle-import") (part "-PNP-SOT23-BECBC857C"))
    )
    (comp (ref "Q4")
      (value "BCP56-16.115")
      (footprint "eagle-import:SOT230P700X180-4N")
      (libsource (lib "eagle-import") (part "BCP56"))
    )
    (comp (ref "Q5")
      (value "STF10P6F6")
      (footprint "eagle-import:TO220H-CLR2")
      (libsource (lib "eagle-import") (part "P-MOSFETMIRROR2"))
    )
    (comp (ref "Q6")
      (value "BCP56-16.115")
      (footprint "eagle-import:SOT230P700X180-4N")
      (libsource (lib "eagle-import") (part "BCP56"))
    )
    (comp (ref "Q7")
      (value "MMBT5401")
      (footprint "eagle-import:SOT23-BEC")
      (libsource (lib "eagle-import") (part "-PNP-SOT23-BECBC857B"))
    )
    (comp (ref "Q8")
      (value "MMBT5401")
      (footprint "eagle-import:SOT23-BEC")
      (libsource (lib "eagle-import") (part "-PNP-SOT23-BECBC857B"))
    )
    (comp (ref "Q9")
      (value "MMBT5551")
      (footprint "eagle-import:SOT23-BEC")
      (libsource (lib "eagle-import") (part "-NPN-SOT23-BECMMBT5551LT1"))
    )
    (comp (ref "Q10")
      (value "MMBT5551")
      (footprint "eagle-import:SOT23-BEC")
      (libsource (lib "eagle-import") (part "-NPN-SOT23-BECMMBT5551LT1"))
    )
    (comp (ref "R10")
      (value "1K")
      (footprint "eagle-import:R0805")
      (libsource (lib "eagle-import") (part "R-EU_R0805"))
    )
    (comp (ref "R11")
      (value "3R9/2W")
      (footprint "eagle-import:R2512")
      (libsource (lib "eagle-import") (part "R-EU_R2512"))
    )
    (comp (ref "R12")
      (value "3R9/2W")
      (footprint "eagle-import:R2512")
      (libsource (lib "eagle-import") (part "R-EU_R2512"))
    )
    (comp (ref "R13")
      (value "750R")
      (footprint "eagle-import:R0805")
      (libsource (lib "eagle-import") (part "R-EU_R0805"))
    )
    (comp (ref "R14")
      (value "10K")
      (footprint "eagle-import:R0805")
      (libsource (lib "eagle-import") (part "R-EU_R0805"))
    )
    (comp (ref "R15")
      (value "2K2")
      (footprint "eagle-import:R0805")
      (libsource (lib "eagle-import") (part "R-EU_R0805"))
    )
    (comp (ref "R16")
      (value "2K2")
      (footprint "eagle-import:R0805")
      (libsource (lib "eagle-import") (part "R-EU_R0805"))
    )
    (comp (ref "R17")
      (value "220R")
      (footprint "eagle-import:R0805")
      (libsource (lib "eagle-import") (part "R-EU_R0805"))
    )
    (comp (ref "R18")
      (value "16K")
      (footprint "eagle-import:R0805")
      (libsource (lib "eagle-import") (part "R-EU_R0805"))
    )
    (comp (ref "R19")
      (value "220R")
      (footprint "eagle-import:R0805")
      (libsource (lib "eagle-import") (part "R-EU_R0805"))
    )
    (comp (ref "R20")
      (value "220R")
      (footprint "eagle-import:R0805")
      (libsource (lib "eagle-import") (part "R-EU_R0805"))
    )
    (comp (ref "R21")
      (value "470R")
      (footprint "eagle-import:R0805")
      (libsource (lib "eagle-import") (part "R-EU_R0805"))
    )
    (comp (ref "R22")
      (value "100R")
      (footprint "eagle-import:R0805")
      (libsource (lib "eagle-import") (part "R-EU_R0805"))
    )
    (comp (ref "R23")
      (value "1K")
      (footprint "eagle-import:R0805")
      (libsource (lib "eagle-import") (part "R-EU_R0805"))
    )
    (comp (ref "R24")
      (value "7K5 0.1%")
      (footprint "eagle-import:R0805")
      (libsource (lib "eagle-import") (part "R-EU_R0805"))
    )
    (comp (ref "R25")
      (value "10K")
      (footprint "eagle-import:R0805")
      (libsource (lib "eagle-import") (part "R-EU_R0805"))
    )
    (comp (ref "R26")
      (value "220R")
      (footprint "eagle-import:R0805")
      (libsource (lib "eagle-import") (part "R-EU_R0805"))
    )
    (comp (ref "R27")
      (value "2K2")
      (footprint "eagle-import:R0805")
      (libsource (lib "eagle-import") (part "R-EU_R0805"))
    )
    (comp (ref "R28")
      (value "750R")
      (footprint "eagle-import:R0805")
      (libsource (lib "eagle-import") (part "R-EU_R0805"))
    )
    (comp (ref "R29")
      (value "130K 0.1%")
      (footprint "eagle-import:R0805")
      (libsource (lib "eagle-import") (part "R-EU_R0805"))
    )
    (comp (ref "R30")
      (value "24K 0.1%")
      (footprint "eagle-import:R0805")
      (libsource (lib "eagle-import") (part "R-EU_R0805"))
    )
    (comp (ref "R31")
      (value "51K")
      (footprint "eagle-import:R0805")
      (libsource (lib "eagle-import") (part "R-EU_R0805"))
    )
    (comp (ref "R32")
      (value "220R")
      (footprint "eagle-import:R0805")
      (libsource (lib "eagle-import") (part "R-EU_R0805"))
    )
    (comp (ref "R33")
      (value "10K")
      (footprint "eagle-import:R0805")
      (libsource (lib "eagle-import") (part "R-EU_R0805"))
    )
    (comp (ref "R34")
      (value "470R")
      (footprint "eagle-import:R0805")
      (libsource (lib "eagle-import") (part "R-EU_R0805"))
    )
    (comp (ref "R35")
      (value "1K8")
      (footprint "eagle-import:R0805")
      (libsource (lib "eagle-import") (part "R-EU_R0805"))
    )
    (comp (ref "R36")
      (value "10K")
      (footprint "eagle-import:R0805")
      (libsource (lib "eagle-import") (part "R-EU_R0805"))
    )
    (comp (ref "R37")
      (value "7K5 0.1%")
      (footprint "eagle-import:R0805")
      (libsource (lib "eagle-import") (part "R-EU_R0805"))
    )
    (comp (ref "R38")
      (value "130K 0.1%")
      (footprint "eagle-import:R0805")
      (libsource (lib "eagle-import") (part "R-EU_R0805"))
    )
    (comp (ref "R39")
      (value "24K 0.1%")
      (footprint "eagle-import:R0805")
      (libsource (lib "eagle-import") (part "R-EU_R0805"))
    )
    (comp (ref "R40")
      (value "10K")
      (footprint "eagle-import:R0805")
      (libsource (lib "eagle-import") (part "R-EU_R0805"))
    )
    (comp (ref "R41")
      (value "220R")
      (footprint "eagle-import:R0805")
      (libsource (lib "eagle-import") (part "R-EU_R0805"))
    )
    (comp (ref "R42")
      (value "2K2")
      (footprint "eagle-import:R0805")
      (libsource (lib "eagle-import") (part "R-EU_R0805"))
    )
    (comp (ref "R43")
      (value "10K")
      (footprint "eagle-import:R0805")
      (libsource (lib "eagle-import") (part "R-EU_R0805"))
    )
    (comp (ref "R44")
      (value "1K")
      (footprint "eagle-import:R0805")
      (libsource (lib "eagle-import") (part "R-EU_R0805"))
    )
    (comp (ref "R45")
      (value "10K")
      (footprint "eagle-import:R0805")
      (libsource (lib "eagle-import") (part "R-EU_R0805"))
    )
    (comp (ref "R46")
      (value "10K")
      (footprint "eagle-import:R0805")
      (libsource (lib "eagle-import") (part "R-EU_R0805"))
    )
    (comp (ref "SH1")
      (value "SHORTNOHOLE")
      (footprint "eagle-import:SHORT_NOHOLE")
      (libsource (lib "eagle-import") (part "SHORTNOHOLE"))
    )
    (comp (ref "SH2")
      (value "SHORTNOHOLE")
      (footprint "eagle-import:SHORT_NOHOLE")
      (libsource (lib "eagle-import") (part "SHORTNOHOLE"))
    )
    (comp (ref "X3")
      (value "39-30-3035")
      (footprint "eagle-import:MINIFIT_6659-3")
      (libsource (lib "eagle-import") (part "MINIFIT_6659-3"))
    )
    (comp (ref "ZD1")
      (value "BZX384-C15")
      (footprint "eagle-import:SOD323-W")
      (libsource (lib "eagle-import") (part "ZENER-DIODESOD323"))
    )
    (comp (ref "ZD2")
      (value "PDZ6.2B")
      (footprint "eagle-import:SOD323-W")
      (libsource (lib "eagle-import") (part "ZENER-DIODESOD323"))
    )
    (comp (ref "C70")
      (value "10n")
      (footprint "eagle-import:C0805")
      (libsource (lib "eagle-import") (part "C-EUC0805"))
    )
    (comp (ref "C71")
      (value "10n/200V")
      (footprint "eagle-import:C1206")
      (libsource (lib "eagle-import") (part "C-EUC1206"))
    )
    (comp (ref "C72")
      (value "2n2")
      (footprint "eagle-import:C0805")
      (libsource (lib "eagle-import") (part "C-EUC0805"))
    )
    (comp (ref "C73")
      (value "470n")
      (footprint "eagle-import:C1206")
      (libsource (lib "eagle-import") (part "C-EUC1206"))
    )
    (comp (ref "C74")
      (value "HHXC630ARA330MHA0G")
      (footprint "eagle-import:CAPAE830X1050N")
      (libsource (lib "eagle-import") (part "ECAPSMD8.3MM/HA0"))
    )
    (comp (ref "C75")
      (value "10n/200V")
      (footprint "eagle-import:C1206")
      (libsource (lib "eagle-import") (part "C-EUC1206"))
    )
    (comp (ref "C76")
      (value "10n")
      (footprint "eagle-import:C0805")
      (libsource (lib "eagle-import") (part "C-EUC0805"))
    )
    (comp (ref "C77")
      (value "N.C.")
      (footprint "eagle-import:ECAP2_5")
      (libsource (lib "eagle-import") (part "ECAP2G/5"))
    )
    (comp (ref "C78")
      (value "N.C.")
      (footprint "eagle-import:C0805")
      (libsource (lib "eagle-import") (part "C-EUC0805"))
    )
    (comp (ref "C79")
      (value "N.C.")
      (footprint "eagle-import:C0805")
      (libsource (lib "eagle-import") (part "C-EUC0805"))
    )
    (comp (ref "D20")
      (value "SK10100D1-DIO")
      (footprint "eagle-import:TO252-L")
      (libsource (lib "eagle-import") (part "SCHOTTKY-DUAL_A_L"))
    )
    (comp (ref "D21")
      (value "BAS316")
      (footprint "eagle-import:SOD323-R")
      (libsource (lib "eagle-import") (part "DIODESOD323R"))
    )
    (comp (ref "D22")
      (value "BAS316")
      (footprint "eagle-import:SOD323-R")
      (libsource (lib "eagle-import") (part "DIODESOD323R"))
    )
    (comp (ref "D23")
      (value "BAS316")
      (footprint "eagle-import:SOD323-R")
      (libsource (lib "eagle-import") (part "DIODESOD323R"))
    )
    (comp (ref "F1")
      (value "ZH32")
      (footprint "eagle-import:ZH32")
      (libsource (lib "eagle-import") (part "ZH32"))
    )
    (comp (ref "F2")
      (value "ZH32")
      (footprint "eagle-import:ZH32")
      (libsource (lib "eagle-import") (part "ZH32"))
    )
    (comp (ref "J1")
      (value "FCR7350R")
      (footprint "eagle-import:S16N-PC")
      (libsource (lib "eagle-import") (part "BINDING_POSTCLIFF"))
    )
    (comp (ref "J2")
      (value "FCR7350B")
      (footprint "eagle-import:S16N-PC")
      (libsource (lib "eagle-import") (part "BINDING_POSTCLIFF"))
    )
    (comp (ref "K1")
      (value "G6K-2F-5DC")
      (footprint "eagle-import:G6K-2F")
      (fields
        (field (name "MF") "OMRON COMPONENTS USA")
        (field (name "MPN") "G6K-2F DC24")
        (field (name "MF_1") "OMRON COMPONENTS USA")
        (field (name "MPN_1") "G6K-2F DC24")
        (field (name "OC_FARNELL") "1690427")
        (field (name "OC_NEWARK") "36K7467")
      )
      (libsource (lib "eagle-import") (part "G6K-2F"))
    )
    (comp (ref "LED2")
      (value "L-934EB/2ID")
      (footprint "eagle-import:L-934EB")
      (libsource (lib "eagle-import") (part "LED_L-934EB/2ID"))
    )
    (comp (ref "LED4")
      (value "OSY5LU3E34X-3F1A")
      (footprint "eagle-import:OSG8")
      (libsource (lib "eagle-import") (part "LEDOSG8"))
    )
    (comp (ref "Q27")
      (value "MMBT5551")
      (footprint "eagle-import:SOT23-BEC")
      (libsource (lib "eagle-import") (part "-NPN-SOT23-BECMMBT5551LT1"))
    )
    (comp (ref "Q28")
      (value "MMBT5401")
      (footprint "eagle-import:SOT23-BEC")
      (libsource (lib "eagle-import") (part "-PNP-SOT23-BECBC857B"))
    )
    (comp (ref "Q29")
      (value "MMBT5551")
      (footprint "eagle-import:SOT23-BEC")
      (libsource (lib "eagle-import") (part "-NPN-SOT23-BECMMBT5551LT1"))
    )
    (comp (ref "Q30")
      (value "MMBT5551")
      (footprint "eagle-import:SOT23-BEC")
      (libsource (lib "eagle-import") (part "-NPN-SOT23-BECMMBT5551LT1"))
    )
    (comp (ref "Q31")
      (value "BSS84P")
      (footprint "eagle-import:SOT95P237X112-3N")
      (fields (field (name "MPN") "IRLML2246TRPBF"))
      (libsource (lib "eagle-import") (part "IRLML2246TRPBF"))
    )
    (comp (ref "Q32")
      (value "2N7002")
      (footprint "eagle-import:SOT103P240X110-3N")
      (fields
        (field (name "MPN") "2N7002-7-F")
        (field (name "MPN_1") "2N7002-7-F")
        (field (name "OC_FARNELL") "1713823")
        (field (name "OC_NEWARK") "25R5679")
        (field (name "PACKAGE") "SOT-23-3")
        (field (name "SUPPLIER") "DIODES INC.")
      )
      (libsource (lib "eagle-import") (part "2N7002"))
    )
    (comp (ref "R125")
      (value "330R")
      (footprint "eagle-import:R0805")
      (libsource (lib "eagle-import") (part "R-EU_R0805"))
    )
    (comp (ref "R126")
      (value "47K")
      (footprint "eagle-import:R0805")
      (libsource (lib "eagle-import") (part "R-EU_R0805"))
    )
    (comp (ref "R127")
      (value "47K")
      (footprint "eagle-import:R0805")
      (libsource (lib "eagle-import") (part "R-EU_R0805"))
    )
    (comp (ref "R128")
      (value "750R")
      (footprint "eagle-import:R0805")
      (libsource (lib "eagle-import") (part "R-EU_R0805"))
    )
    (comp (ref "R129")
      (value "1K")
      (footprint "eagle-import:R0805")
      (libsource (lib "eagle-import") (part "R-EU_R0805"))
    )
    (comp (ref "R130")
      (value "2K2")
      (footprint "eagle-import:R0805")
      (libsource (lib "eagle-import") (part "R-EU_R0805"))
    )
    (comp (ref "R131")
      (value "10K")
      (footprint "eagle-import:R0805")
      (libsource (lib "eagle-import") (part "R-EU_R0805"))
    )
    (comp (ref "R132")
      (value "10K")
      (footprint "eagle-import:R0805")
      (libsource (lib "eagle-import") (part "R-EU_R0805"))
    )
    (comp (ref "R133")
      (value "1R")
      (footprint "eagle-import:R0805")
      (libsource (lib "eagle-import") (part "R-EU_R0805"))
    )
    (comp (ref "R134")
      (value "750R")
      (footprint "eagle-import:R0805")
      (libsource (lib "eagle-import") (part "R-EU_R0805"))
    )
    (comp (ref "R135")
      (value "47K")
      (footprint "eagle-import:R0805")
      (libsource (lib "eagle-import") (part "R-EU_R0805"))
    )
    (comp (ref "R136")
      (value "330R")
      (footprint "eagle-import:R0805")
      (libsource (lib "eagle-import") (part "R-EU_R0805"))
    )
    (comp (ref "R137")
      (value "10K")
      (footprint "eagle-import:R0805")
      (libsource (lib "eagle-import") (part "R-EU_R0805"))
    )
    (comp (ref "R138")
      (value "470R")
      (footprint "eagle-import:R0805")
      (libsource (lib "eagle-import") (part "R-EU_R0805"))
    )
    (comp (ref "R139")
      (value "470R")
      (footprint "eagle-import:R0805")
      (libsource (lib "eagle-import") (part "R-EU_R0805"))
    )
    (comp (ref "R140")
      (value "100K")
      (footprint "eagle-import:R0805")
      (libsource (lib "eagle-import") (part "R-EU_R0805"))
    )
    (comp (ref "X4")
      (value "1844249")
      (footprint "eagle-import:MC1,5_5-G-3,5")
      (libsource (lib "eagle-import") (part "MC1,5/5-G-3,5"))
    )
    (comp (ref "X5")
      (value "ZL263-20DG")
      (footprint "eagle-import:SSW-110-02-T-D-RA")
      (libsource (lib "eagle-import") (part "SSW-110-02-T-D-RA"))
    )
    (comp (ref "C46")
      (value "100n")
      (footprint "eagle-import:C0603")
      (libsource (lib "eagle-import") (part "C-EUC0603"))
    )
    (comp (ref "C47")
      (value "100n")
      (footprint "eagle-import:C0603")
      (libsource (lib "eagle-import") (part "C-EUC0603"))
    )
    (comp (ref "C48")
      (value "1u")
      (footprint "eagle-import:C0805")
      (libsource (lib "eagle-import") (part "C-EUC0805"))
    )
    (comp (ref "C49")
      (value "10u")
      (footprint "eagle-import:C1206")
      (libsource (lib "eagle-import") (part "C-EUC1206"))
    )
    (comp (ref "C50")
      (value "100n")
      (footprint "eagle-import:C0603")
      (libsource (lib "eagle-import") (part "C-EUC0603"))
    )
    (comp (ref "C51")
      (value "4u7")
      (footprint "eagle-import:EC1206")
      (libsource (lib "eagle-import") (part "ECAP1206"))
    )
    (comp (ref "C52")
      (value "1u")
      (footprint "eagle-import:C0805")
      (libsource (lib "eagle-import") (part "C-EUC0805"))
    )
    (comp (ref "C53")
      (value "100n")
      (footprint "eagle-import:C0603")
      (libsource (lib "eagle-import") (part "C-EUC0603"))
    )
    (comp (ref "C54")
      (value "3n3")
      (footprint "eagle-import:C0805")
      (libsource (lib "eagle-import") (part "C-EUC0805"))
    )
    (comp (ref "C55")
      (value "3n3")
      (footprint "eagle-import:C0805")
      (libsource (lib "eagle-import") (part "C-EUC0805"))
    )
    (comp (ref "C56")
      (value "10n")
      (footprint "eagle-import:C0805")
      (libsource (lib "eagle-import") (part "C-EUC0805"))
    )
    (comp (ref "C57")
      (value "3n3")
      (footprint "eagle-import:C0805")
      (libsource (lib "eagle-import") (part "C-EUC0805"))
    )
    (comp (ref "C58")
      (value "3n3")
      (footprint "eagle-import:C0805")
      (libsource (lib "eagle-import") (part "C-EUC0805"))
    )
    (comp (ref "C59")
      (value "100n")
      (footprint "eagle-import:C0603")
      (libsource (lib "eagle-import") (part "C-EUC0603"))
    )
    (comp (ref "C60")
      (value "1u")
      (footprint "eagle-import:C0805")
      (libsource (lib "eagle-import") (part "C-EUC0805"))
    )
    (comp (ref "C61")
      (value "100n")
      (footprint "eagle-import:C0603")
      (libsource (lib "eagle-import") (part "C-EUC0603"))
    )
    (comp (ref "C62")
      (value "1u")
      (footprint "eagle-import:C0805")
      (libsource (lib "eagle-import") (part "C-EUC0805"))
    )
    (comp (ref "C63")
      (value "100n")
      (footprint "eagle-import:C0603")
      (libsource (lib "eagle-import") (part "C-EUC0603"))
    )
    (comp (ref "D17")
      (value "BAS316")
      (footprint "eagle-import:SOD323-R")
      (libsource (lib "eagle-import") (part "DIODESOD323R"))
    )
    (comp (ref "IC14")
      (value "74AUP1G74DC.125")
      (footprint "eagle-import:DCU8")
      (libsource (lib "eagle-import") (part "SN74LVC1G74DCTR-VSSOP"))
    )
    (comp (ref "IC15")
      (value "MCP23S17-E/SS")
      (footprint "eagle-import:SOP65P780X200-28N")
      (libsource (lib "eagle-import") (part "MCP23S17-E/SSSSOP"))
    )
    (comp (ref "IC16")
      (value "REF5025AIDR")
      (footprint "eagle-import:SOIC127P600X175-8N")
      (libsource (lib "eagle-import") (part "REF50XX"))
    )
    (comp (ref "IC17")
      (value "DAC8552IDGKR")
      (footprint "eagle-import:DGK8-M")
      (libsource (lib "eagle-import") (part "DAC8552_DGK_8M"))
    )
    (comp (ref "IC18")
      (value "SN74LVC1G3157DCKR")
      (footprint "eagle-import:SOT65P210X110-6N")
      (libsource (lib "eagle-import") (part "SN74LVC1G3157-DCK"))
    )
    (comp (ref "IC19")
      (value "ADS1120IPWR")
      (footprint "eagle-import:PW(R-PDSO-G16)")
      (libsource (lib "eagle-import") (part "ADS1120TSSOP-16"))
    )
    (comp (ref "JP3")
      (value "JP2-CUT")
      (footprint "eagle-import:JP2-CUT")
      (libsource (lib "eagle-import") (part "JP2-CUT"))
    )
    (comp (ref "JP4")
      (value "JP3-CUT")
      (footprint "eagle-import:JP3-CUT")
      (libsource (lib "eagle-import") (part "JP3-CUT"))
    )
    (comp (ref "LED1")
      (value "L-42WUM/1EGWT")
      (footprint "eagle-import:L-42WUM-1EGWT")
      (libsource (lib "eagle-import") (part "LED_L-42WUM/1EGWT"))
    )
    (comp (ref "Q18")
      (value "2N7002")
      (footprint "eagle-import:SOT103P240X110-3N")
      (fields
        (field (name "MPN") "2N7002-7-F")
        (field (name "MPN_1") "2N7002-7-F")
        (field (name "OC_FARNELL") "1713823")
        (field (name "OC_NEWARK") "25R5679")
        (field (name "PACKAGE") "SOT-23-3")
        (field (name "SUPPLIER") "DIODES INC.")
      )
      (libsource (lib "eagle-import") (part "2N7002"))
    )
    (comp (ref "Q19")
      (value "BSS84P")
      (footprint "eagle-import:SOT95P237X112-3N")
      (fields (field (name "MPN") "IRLML2246TRPBF"))
      (libsource (lib "eagle-import") (part "IRLML2246TRPBF"))
    )
    (comp (ref "R89")
      (value "100K")
      (footprint "eagle-import:R0805")
      (libsource (lib "eagle-import") (part "R-EU_R0805"))
    )
    (comp (ref "R90")
      (value "270R")
      (footprint "eagle-import:R0805")
      (libsource (lib "eagle-import") (part "R-EU_R0805"))
    )
    (comp (ref "R91")
      (value "47K")
      (footprint "eagle-import:R0805")
      (libsource (lib "eagle-import") (part "R-EU_R0805"))
    )
    (comp (ref "R92")
      (value "100K")
      (footprint "eagle-import:R0805")
      (libsource (lib "eagle-import") (part "R-EU_R0805"))
    )
    (comp (ref "R93")
      (value "470R")
      (footprint "eagle-import:R0805")
      (libsource (lib "eagle-import") (part "R-EU_R0805"))
    )
    (comp (ref "R94")
      (value "10K")
      (footprint "eagle-import:R0805")
      (libsource (lib "eagle-import") (part "R-EU_R0805"))
    )
    (comp (ref "R95")
      (value "220R")
      (footprint "eagle-import:R0805")
      (libsource (lib "eagle-import") (part "R-EU_R0805"))
    )
    (comp (ref "R96")
      (value "220R")
      (footprint "eagle-import:R0805")
      (libsource (lib "eagle-import") (part "R-EU_R0805"))
    )
    (comp (ref "R97")
      (value "470R")
      (footprint "eagle-import:R0805")
      (libsource (lib "eagle-import") (part "R-EU_R0805"))
    )
    (comp (ref "R98")
      (value "470R")
      (footprint "eagle-import:R0805")
      (libsource (lib "eagle-import") (part "R-EU_R0805"))
    )
    (comp (ref "R99")
      (value "220R")
      (footprint "eagle-import:R0805")
      (libsource (lib "eagle-import") (part "R-EU_R0805"))
    )
    (comp (ref "R100")
      (value "220R")
      (footprint "eagle-import:R0805")
      (libsource (lib "eagle-import") (part "R-EU_R0805"))
    )
    (comp (ref "R101")
      (value "10R")
      (footprint "eagle-import:R0805")
      (libsource (lib "eagle-import") (part "R-EU_R0805"))
    )
    (comp (ref "ZD3")
      (value "SLVU2.8-TP")
      (footprint "eagle-import:SOT23")
      (libsource (lib "eagle-import") (part "SLVU2.8"))
    )
    (comp (ref "C64")
      (value "1u")
      (footprint "eagle-import:C0805")
      (libsource (lib "eagle-import") (part "C-EUC0805"))
    )
    (comp (ref "C65")
      (value "100n")
      (footprint "eagle-import:C0603")
      (libsource (lib "eagle-import") (part "C-EUC0603"))
    )
    (comp (ref "C66")
      (value "100n")
      (footprint "eagle-import:C0603")
      (libsource (lib "eagle-import") (part "C-EUC0603"))
    )
    (comp (ref "C67")
      (value "1n")
      (footprint "eagle-import:C0805")
      (libsource (lib "eagle-import") (part "C-EUC0805"))
    )
    (comp (ref "C68")
      (value "100n")
      (footprint "eagle-import:C0603")
      (libsource (lib "eagle-import") (part "C-EUC0603"))
    )
    (comp (ref "C69")
      (value "1n")
      (footprint "eagle-import:C0805")
      (libsource (lib "eagle-import") (part "C-EUC0805"))
    )
    (comp (ref "D18")
      (value "BAS316")
      (footprint "eagle-import:SOD323-R")
      (libsource (lib "eagle-import") (part "DIODESOD323R"))
    )
    (comp (ref "D19")
      (value "BAS316")
      (footprint "eagle-import:SOD323-R")
      (libsource (lib "eagle-import") (part "DIODESOD323R"))
    )
    (comp (ref "IC20")
      (value "LM339D")
      (footprint "eagle-import:SOIC127P600X175-14N")
      (libsource (lib "eagle-import") (part "LM339SO14"))
    )
    (comp (ref "IC21")
      (value "LM211PWR")
      (footprint "eagle-import:PW8_TSSOP8")
      (libsource (lib "eagle-import") (part "LM211"))
    )
    (comp (ref "LED3")
      (value "L-934EB/1Y1ID-RV")
      (footprint "eagle-import:L-934EB")
      (libsource (lib "eagle-import") (part "LED_L-934EB/1Y1ID-RV"))
    )
    (comp (ref "Q20")
      (value "BTA26-600")
      (footprint "eagle-import:TOP3_TRIAC_NOHOLE")
      (libsource (lib "eagle-import") (part "BTA41-2"))
    )
    (comp (ref "Q21")
      (value "2N7002")
      (footprint "eagle-import:SOT103P240X110-3N")
      (fields
        (field (name "MPN") "2N7002-7-F")
        (field (name "MPN_1") "2N7002-7-F")
        (field (name "OC_FARNELL") "1713823")
        (field (name "OC_NEWARK") "25R5679")
        (field (name "PACKAGE") "SOT-23-3")
        (field (name "SUPPLIER") "DIODES INC.")
      )
      (libsource (lib "eagle-import") (part "2N7002"))
    )
    (comp (ref "Q22")
      (value "FMMT493TA")
      (footprint "eagle-import:SOT23-BEC")
      (libsource (lib "eagle-import") (part "-NPN-SOT23-BECMMBT5551LT1"))
    )
    (comp (ref "Q23")
      (value "2N7002")
      (footprint "eagle-import:SOT103P240X110-3N")
      (fields (field (name "MPN") "2N7002-7-F"))
      (libsource (lib "eagle-import") (part "2N7002"))
    )
    (comp (ref "Q24")
      (value "2N7002")
      (footprint "eagle-import:SOT103P240X110-3N")
      (fields (field (name "MPN") "2N7002-7-F"))
      (libsource (lib "eagle-import") (part "2N7002"))
    )
    (comp (ref "Q25")
      (value "2N7002")
      (footprint "eagle-import:SOT103P240X110-3N")
      (fields (field (name "MPN") "2N7002-7-F"))
      (libsource (lib "eagle-import") (part "2N7002"))
    )
    (comp (ref "Q26")
      (value "MMBT5551")
      (footprint "eagle-import:SOT23-BEC")
      (libsource (lib "eagle-import") (part "-NPN-SOT23-BECMMBT5551LT1"))
    )
    (comp (ref "R102")
      (value "10K")
      (footprint "eagle-import:R0805")
      (libsource (lib "eagle-import") (part "R-EU_R0805"))
    )
    (comp (ref "R103")
      (value "10K")
      (footprint "eagle-import:R0805")
      (libsource (lib "eagle-import") (part "R-EU_R0805"))
    )
    (comp (ref "R104")
      (value "470R")
      (footprint "eagle-import:R0805")
      (libsource (lib "eagle-import") (part "R-EU_R0805"))
    )
    (comp (ref "R105")
      (value "5K1")
      (footprint "eagle-import:R0805")
      (libsource (lib "eagle-import") (part "R-EU_R0805"))
    )
    (comp (ref "R106")
      (value "47K")
      (footprint "eagle-import:R0805")
      (libsource (lib "eagle-import") (part "R-EU_R0805"))
    )
    (comp (ref "R107")
      (value "5K6")
      (footprint "eagle-import:R0805")
      (libsource (lib "eagle-import") (part "R-EU_R0805"))
    )
    (comp (ref "R108")
      (value "330R")
      (footprint "eagle-import:R0805")
      (libsource (lib "eagle-import") (part "R-EU_R0805"))
    )
    (comp (ref "R109")
      (value "750R")
      (footprint "eagle-import:R0805")
      (libsource (lib "eagle-import") (part "R-EU_R0805"))
    )
    (comp (ref "R110")
      (value "1K")
      (footprint "eagle-import:R0805")
      (libsource (lib "eagle-import") (part "R-EU_R0805"))
    )
    (comp (ref "R111")
      (value "AC01000001007JA100")
      (footprint "eagle-import:0411_15")
      (libsource (lib "eagle-import") (part "R-EU_0411/15"))
    )
    (comp (ref "R112")
      (value "2K2")
      (footprint "eagle-import:R0805")
      (libsource (lib "eagle-import") (part "R-EU_R0805"))
    )
    (comp (ref "R113")
      (value "330R")
      (footprint "eagle-import:R0805")
      (libsource (lib "eagle-import") (part "R-EU_R0805"))
    )
    (comp (ref "R114")
      (value "10K")
      (footprint "eagle-import:R0805")
      (libsource (lib "eagle-import") (part "R-EU_R0805"))
    )
    (comp (ref "R115")
      (value "10K")
      (footprint "eagle-import:R0805")
      (libsource (lib "eagle-import") (part "R-EU_R0805"))
    )
    (comp (ref "R116")
      (value "100K")
      (footprint "eagle-import:R0805")
      (libsource (lib "eagle-import") (part "R-EU_R0805"))
    )
    (comp (ref "R117")
      (value "6R2")
      (footprint "eagle-import:R0805")
      (libsource (lib "eagle-import") (part "R-EU_R0805"))
    )
    (comp (ref "R118")
      (value "10K")
      (footprint "eagle-import:R0805")
      (libsource (lib "eagle-import") (part "R-EU_R0805"))
    )
    (comp (ref "R119")
      (value "5K1")
      (footprint "eagle-import:R0805")
      (libsource (lib "eagle-import") (part "R-EU_R0805"))
    )
    (comp (ref "R120")
      (value "10K")
      (footprint "eagle-import:R0805")
      (libsource (lib "eagle-import") (part "R-EU_R0805"))
    )
    (comp (ref "R121")
      (value "4K7")
      (footprint "eagle-import:R0805")
      (libsource (lib "eagle-import") (part "R-EU_R0805"))
    )
    (comp (ref "R122")
      (value "5K6")
      (footprint "eagle-import:R0805")
      (libsource (lib "eagle-import") (part "R-EU_R0805"))
    )
    (comp (ref "R123")
      (value "10K")
      (footprint "eagle-import:R0805")
      (libsource (lib "eagle-import") (part "R-EU_R0805"))
    )
    (comp (ref "R124")
      (value "1K")
      (footprint "eagle-import:R0805")
      (libsource (lib "eagle-import") (part "R-EU_R0805"))
    )
  )
  (nets
    (net (code "1") (name "+3V3") (class "Default")
      (node (ref "C14") (pin "1") (pinfunction "1_1") (pintype "passive"))
      (node (ref "C16") (pin "2") (pinfunction "2_2") (pintype "passive"))
      (node (ref "C17") (pin "1") (pinfunction "1_1") (pintype "passive"))
      (node (ref "C6") (pin "1") (pinfunction "1_1") (pintype "passive"))
      (node (ref "IC2") (pin "1") (pinfunction "VDD1_1") (pintype "passive"))
      (node (ref "IC2") (pin "7") (pinfunction "EN1_7") (pintype "input"))
      (node (ref "IC5") (pin "1") (pinfunction "VDD1_1") (pintype "passive"))
      (node (ref "IC5") (pin "7") (pinfunction "EN1_7") (pintype "input"))
      (node (ref "IC6") (pin "8") (pinfunction "VCC_8") (pintype "power_in"))
      (node (ref "IC7") (pin "8") (pinfunction "V+_8") (pintype "passive"))
      (node (ref "R7") (pin "1") (pinfunction "1_1") (pintype "passive"))
      (node (ref "R8") (pin "1") (pinfunction "1_1") (pintype "passive"))
      (node (ref "R9") (pin "1") (pinfunction "1_1") (pintype "passive"))
      (node (ref "X1") (pin "1") (pinfunction "1_1") (pintype "passive"))
    )
    (net (code "2") (name "+5V") (class "Default")
      (node (ref "C15") (pin "2") (pinfunction "2_2") (pintype "passive"))
      (node (ref "C46") (pin "1") (pinfunction "1_1") (pintype "passive"))
      (node (ref "C47") (pin "2") (pinfunction "2_2") (pintype "passive"))
      (node (ref "C59") (pin "2") (pinfunction "2_2") (pintype "passive"))
      (node (ref "C60") (pin "2") (pinfunction "2_2") (pintype "passive"))
      (node (ref "C7") (pin "2") (pinfunction "2_2") (pintype "passive"))
      (node (ref "C8") (pin "1") (pinfunction "1_1") (pintype "passive"))
      (node (ref "D21") (pin "C") (pinfunction "C_C") (pintype "passive"))
      (node (ref "FB3") (pin "P$2") (pinfunction "2_P$2") (pintype "passive"))
      (node (ref "IC14") (pin "7") (pinfunction "~{PRE}_7") (pintype "input"))
      (node (ref "IC14") (pin "8") (pinfunction "VDD_8") (pintype "power_in"))
      (node (ref "IC15") (pin "9") (pinfunction "VDD_9") (pintype "power_in"))
      (node (ref "IC19") (pin "13") (pinfunction "DVDD_13") (pintype "power_in"))
      (node (ref "IC2") (pin "10") (pinfunction "EN2_10") (pintype "input"))
      (node (ref "IC2") (pin "16") (pinfunction "VDD2_16") (pintype "passive"))
      (node (ref "IC3") (pin "8") (pinfunction "VCC_8") (pintype "passive"))
      (node (ref "IC5") (pin "10") (pinfunction "EN2_10") (pintype "input"))
      (node (ref "IC5") (pin "16") (pinfunction "VDD2_16") (pintype "passive"))
      (node (ref "K1") (pin "1") (pinfunction "+_1") (pintype "passive"))
      (node (ref "LED2") (pin "BA") (pinfunction "A_BA") (pintype "passive"))
      (node (ref "LED3") (pin "BA") (pinfunction "A_BA") (pintype "passive"))
      (node (ref "LED3") (pin "TA") (pinfunction "A_TA") (pintype "passive"))
      (node (ref "Q10") (pin "B") (pinfunction "B_B") (pintype "passive"))
      (node (ref "Q19") (pin "2") (pinfunction "S_2") (pintype "passive"))
      (node (ref "Q31") (pin "2") (pinfunction "S_2") (pintype "passive"))
      (node (ref "R105") (pin "2") (pinfunction "2_2") (pintype "passive"))
      (node (ref "R119") (pin "2") (pinfunction "2_2") (pintype "passive"))
      (node (ref "R131") (pin "2") (pinfunction "2_2") (pintype "passive"))
      (node (ref "R137") (pin "1") (pinfunction "1_1") (pintype "passive"))
      (node (ref "R6") (pin "1") (pinfunction "1_1") (pintype "passive"))
      (node (ref "R92") (pin "1") (pinfunction "1_1") (pintype "passive"))
    )
    (net (code "3") (name "+5VOUT") (class "Default")
      (node (ref "C5") (pin "+") (pinfunction "+_+") (pintype "passive"))
      (node (ref "D1") (pin "A") (pinfunction "A_A") (pintype "passive"))
      (node (ref "D2") (pin "C") (pinfunction "C_C") (pintype "passive"))
      (node (ref "FB2") (pin "P$1") (pinfunction "1_P$1") (pintype "passive"))
      (node (ref "FB3") (pin "P$1") (pinfunction "1_P$1") (pintype "passive"))
      (node (ref "IC1") (pin "1") (pinfunction "OUT_1") (pintype "output"))
      (node (ref "R4") (pin "1") (pinfunction "1_1") (pintype "passive"))
    )
    (net (code "4") (name "+6V") (class "Default")
      (node (ref "C2") (pin "1") (pinfunction "1_1") (pintype "passive"))
      (node (ref "C3") (pin "1") (pinfunction "1_1") (pintype "passive"))
      (node (ref "C4") (pin "1") (pinfunction "1_1") (pintype "passive"))
      (node (ref "D1") (pin "C") (pinfunction "C_C") (pintype "passive"))
      (node (ref "FB1") (pin "P$2") (pinfunction "2_P$2") (pintype "passive"))
      (node (ref "IC1") (pin "8") (pinfunction "IN_8") (pintype "power_in"))
    )
    (net (code "5") (name "+VAUX") (class "Default")
      (node (ref "X1") (pin "2") (pinfunction "1_2") (pintype "passive"))
    )
    (net (code "6") (name "+VREF") (class "Default")
      (node (ref "C51") (pin "+") (pinfunction "+_+") (pintype "passive"))
      (node (ref "C53") (pin "2") (pinfunction "2_2") (pintype "passive"))
      (node (ref "C63") (pin "2") (pinfunction "2_2") (pintype "passive"))
      (node (ref "IC16") (pin "6") (pinfunction "VOUT_6") (pintype "output"))
      (node (ref "IC17") (pin "2") (pinfunction "VREF_2") (pintype "input"))
      (node (ref "IC19") (pin "9") (pinfunction "REFP0_9") (pintype "input"))
      (node (ref "R14") (pin "1") (pinfunction "1_1") (pintype "passive"))
      (node (ref "R51") (pin "1") (pinfunction "1_1") (pintype "passive"))
      (node (ref "R79") (pin "2") (pinfunction "2_2") (pintype "passive"))
      (node (ref "R81") (pin "2") (pinfunction "2_2") (pintype "passive"))
      (node (ref "R87") (pin "2") (pinfunction "2_2") (pintype "passive"))
    )
    (net (code "7") (name "-5VOUT") (class "Default")
      (node (ref "C12") (pin "2") (pinfunction "2_2") (pintype "passive"))
      (node (ref "D3") (pin "A") (pinfunction "A_A") (pintype "passive"))
      (node (ref "D4") (pin "C") (pinfunction "C_C") (pintype "passive"))
      (node (ref "FB5") (pin "P$1") (pinfunction "1_P$1") (pintype "passive"))
      (node (ref "IC4") (pin "1") (pinfunction "OUT_1") (pintype "passive"))
    )
    (net (code "8") (name "-9V") (class "Default")
      (node (ref "C10") (pin "2") (pinfunction "2_2") (pintype "passive"))
      (node (ref "C11") (pin "2") (pinfunction "2_2") (pintype "passive"))
      (node (ref "C13") (pin "1") (pinfunction "1_1") (pintype "passive"))
      (node (ref "D4") (pin "A") (pinfunction "A_A") (pintype "passive"))
      (node (ref "FB4") (pin "P$2") (pinfunction "2_P$2") (pintype "passive"))
      (node (ref "IC4") (pin "2") (pinfunction "IN_2") (pintype "input"))
      (node (ref "IC4") (pin "3") (pinfunction "IN_3") (pintype "input"))
      (node (ref "IC4") (pin "6") (pinfunction "IN_6") (pintype "input"))
      (node (ref "IC4") (pin "7") (pinfunction "IN_7") (pintype "input"))
      (node (ref "R23") (pin "2") (pinfunction "2_2") (pintype "passive"))
      (node (ref "R26") (pin "2") (pinfunction "2_2") (pintype "passive"))
    )
    (net (code "9") (name "AUX_USET_SW") (class "Default")
      (node (ref "IC15") (pin "4") (pinfunction "GPB3_4") (pintype "bidirectional"))
      (node (ref "IC18") (pin "6") (pinfunction "CTRL_6") (pintype "input"))
      (node (ref "LED2") (pin "TA") (pinfunction "A_TA") (pintype "passive"))
      (node (ref "R91") (pin "2") (pinfunction "2_2") (pintype "passive"))
    )
    (net (code "10") (name "BIAS_IN+") (class "Default")
      (node (ref "FB8") (pin "P$1") (pinfunction "1_P$1") (pintype "passive"))
      (node (ref "X2") (pin "9") (pinfunction "1_9") (pintype "passive"))
    )
    (net (code "11") (name "CC_ACTIVE") (class "Default")
      (node (ref "IC15") (pin "22") (pinfunction "GPA1_22") (pintype "bidirectional"))
      (node (ref "Q24") (pin "1") (pinfunction "G_1") (pintype "passive"))
      (node (ref "R119") (pin "1") (pinfunction "1_1") (pintype "passive"))
      (node (ref "R122") (pin "2") (pinfunction "2_2") (pintype "passive"))
    )
    (net (code "12") (name "CSA") (class "Default")
      (node (ref "IC2") (pin "13") (pinfunction "B2_13") (pintype "output"))
      (node (ref "IC3") (pin "1") (pinfunction "A_1") (pintype "input"))
    )
    (net (code "13") (name "CSB") (class "Default")
      (node (ref "IC2") (pin "12") (pinfunction "B3_12") (pintype "output"))
      (node (ref "IC3") (pin "2") (pinfunction "B_2") (pintype "input"))
    )
    (net (code "14") (name "CS_ADC") (class "Default")
      (node (ref "IC19") (pin "2") (pinfunction "~{CS}_2") (pintype "input"))
      (node (ref "RN1") (pin "7") (pinfunction "2_7") (pintype "passive"))
    )
    (net (code "15") (name "CS_DAC") (class "Default")
      (node (ref "IC17") (pin "5") (pinfunction "~{SYNC}_5") (pintype "input"))
      (node (ref "RN1") (pin "8") (pinfunction "2_8") (pintype "passive"))
    )
    (net (code "16") (name "CS_IOEXP") (class "Default")
      (node (ref "IC15") (pin "11") (pinfunction "~{CS}_11") (pintype "input"))
      (node (ref "RN1") (pin "5") (pinfunction "2_5") (pintype "passive"))
    )
    (net (code "17") (name "CURR_5A") (class "Default")
      (node (ref "IC13") (pin "13") (pinfunction "E_13") (pintype "input"))
      (node (ref "IC15") (pin "5") (pinfunction "GPB4_5") (pintype "bidirectional"))
      (node (ref "Q11") (pin "4") (pinfunction "G_4") (pintype "passive"))
      (node (ref "Q14") (pin "1") (pinfunction "G_1") (pintype "passive"))
      (node (ref "Q17") (pin "E") (pinfunction "E_E") (pintype "passive"))
      (node (ref "R48") (pin "2") (pinfunction "2_2") (pintype "passive"))
    )
    (net (code "18") (name "CURR_50MA") (class "Default")
      (node (ref "D14") (pin "C") (pinfunction "C_C") (pintype "passive"))
      (node (ref "IC13") (pin "6") (pinfunction "E_6") (pintype "input"))
      (node (ref "IC15") (pin "7") (pinfunction "GPB6_7") (pintype "bidirectional"))
      (node (ref "Q13") (pin "4") (pinfunction "G_4") (pintype "passive"))
      (node (ref "Q14") (pin "3") (pinfunction "D_3") (pintype "passive"))
      (node (ref "Q15") (pin "3") (pinfunction "D_3") (pintype "passive"))
    )
    (net (code "19") (name "CURR_500MA") (class "Default")
      (node (ref "IC13") (pin "5") (pinfunction "E_5") (pintype "input"))
      (node (ref "IC15") (pin "6") (pinfunction "GPB5_6") (pintype "bidirectional"))
      (node (ref "Q12") (pin "4") (pinfunction "G_4") (pintype "passive"))
      (node (ref "Q15") (pin "1") (pinfunction "G_1") (pintype "passive"))
      (node (ref "Q16") (pin "E") (pinfunction "E_E") (pintype "passive"))
      (node (ref "R49") (pin "2") (pinfunction "2_2") (pintype "passive"))
    )
    (net (code "20") (name "CV_ACTIVE") (class "Default")
      (node (ref "IC15") (pin "23") (pinfunction "GPA2_23") (pintype "bidirectional"))
      (node (ref "Q23") (pin "1") (pinfunction "G_1") (pintype "passive"))
      (node (ref "R105") (pin "1") (pinfunction "1_1") (pintype "passive"))
      (node (ref "R107") (pin "2") (pinfunction "2_2") (pintype "passive"))
    )
    (net (code "21") (name "DIB_5V") (class "Default")
      (node (ref "X1") (pin "23") (pinfunction "1_23") (pintype "passive"))
      (node (ref "X1") (pin "24") (pinfunction "1_24") (pintype "passive"))
    )
    (net (code "22") (name "DIB_12V") (class "Default")
      (node (ref "X1") (pin "21") (pinfunction "1_21") (pintype "passive"))
      (node (ref "X1") (pin "22") (pinfunction "1_22") (pintype "passive"))
    )
    (net (code "23") (name "DIB_A0") (class "Default")
      (node (ref "IC6") (pin "1") (pinfunction "A0_1") (pintype "input"))
      (node (ref "IC7") (pin "7") (pinfunction "A0_7") (pintype "input"))
      (node (ref "R9") (pin "2") (pinfunction "2_2") (pintype "passive"))
      (node (ref "X1") (pin "17") (pinfunction "1_17") (pintype "passive"))
    )
    (net (code "24") (name "DIB_A1") (class "Default")
      (node (ref "IC6") (pin "2") (pinfunction "A1_2") (pintype "input"))
      (node (ref "IC7") (pin "6") (pinfunction "A1_6") (pintype "input"))
      (node (ref "R8") (pin "2") (pinfunction "2_2") (pintype "passive"))
      (node (ref "X1") (pin "19") (pinfunction "1_19") (pintype "passive"))
    )
    (net (code "25") (name "DIB_A2") (class "Default")
      (node (ref "IC6") (pin "3") (pinfunction "A2_3") (pintype "input"))
      (node (ref "IC7") (pin "5") (pinfunction "A2_5") (pintype "input"))
      (node (ref "R7") (pin "2") (pinfunction "2_2") (pintype "passive"))
      (node (ref "X1") (pin "18") (pinfunction "1_18") (pintype "passive"))
    )
    (net (code "26") (name "DIB_CSA") (class "Default")
      (node (ref "IC2") (pin "4") (pinfunction "A2_4") (pintype "input"))
      (node (ref "X1") (pin "9") (pinfunction "1_9") (pintype "passive"))
    )
    (net (code "27") (name "DIB_CSB") (class "Default")
      (node (ref "IC2") (pin "5") (pinfunction "A3_5") (pintype "input"))
      (node (ref "X1") (pin "12") (pinfunction "1_12") (pintype "passive"))
    )
    (net (code "28") (name "DIB_IRQ") (class "Default")
      (node (ref "IC5") (pin "6") (pinfunction "A4_6") (pintype "output"))
      (node (ref "X1") (pin "10") (pinfunction "1_10") (pintype "passive"))
    )
    (net (code "29") (name "DIB_MISO") (class "Default")
      (node (ref "IC2") (pin "6") (pinfunction "A4_6") (pintype "output"))
      (node (ref "X1") (pin "14") (pinfunction "1_14") (pintype "passive"))
    )
    (net (code "30") (name "DIB_MOSI") (class "Default")
      (node (ref "IC5") (pin "3") (pinfunction "A1_3") (pintype "input"))
      (node (ref "X1") (pin "15") (pinfunction "1_15") (pintype "passive"))
    )
    (net (code "31") (name "DIB_NFAULT") (class "Default")
      (node (ref "IC7") (pin "3") (pinfunction "ALERT_3") (pintype "passive"))
      (node (ref "X1") (pin "3") (pinfunction "1_3") (pintype "passive"))
    )
    (net (code "32") (name "DIB_NRESET") (class "Default")
      (node (ref "IC5") (pin "5") (pinfunction "A3_5") (pintype "input"))
      (node (ref "X1") (pin "4") (pinfunction "1_4") (pintype "passive"))
    )
    (net (code "33") (name "DIB_SCL") (class "Default")
      (node (ref "IC6") (pin "6") (pinfunction "SCL_6") (pintype "bidirectional"))
      (node (ref "IC7") (pin "2") (pinfunction "SCL_2") (pintype "bidirectional"))
      (node (ref "X1") (pin "5") (pinfunction "1_5") (pintype "passive"))
    )
    (net (code "34") (name "DIB_SCLK") (class "Default")
      (node (ref "IC2") (pin "3") (pinfunction "A1_3") (pintype "input"))
      (node (ref "X1") (pin "13") (pinfunction "1_13") (pintype "passive"))
    )
    (net (code "35") (name "DIB_SDA") (class "Default")
      (node (ref "IC6") (pin "5") (pinfunction "SDA_5") (pintype "bidirectional"))
      (node (ref "IC7") (pin "1") (pinfunction "SDA_1") (pintype "bidirectional"))
      (node (ref "X1") (pin "8") (pinfunction "1_8") (pintype "passive"))
    )
    (net (code "36") (name "GND") (class "Default")
      (node (ref "C10") (pin "1") (pinfunction "1_1") (pintype "passive"))
      (node (ref "C11") (pin "1") (pinfunction "1_1") (pintype "passive"))
      (node (ref "C12") (pin "1") (pinfunction "1_1") (pintype "passive"))
      (node (ref "C15") (pin "1") (pinfunction "1_1") (pintype "passive"))
      (node (ref "C20") (pin "2") (pinfunction "2_2") (pintype "passive"))
      (node (ref "C21") (pin "2") (pinfunction "2_2") (pintype "passive"))
      (node (ref "C23") (pin "2") (pinfunction "2_2") (pintype "passive"))
      (node (ref "C3") (pin "2") (pinfunction "2_2") (pintype "passive"))
      (node (ref "C30") (pin "1") (pinfunction "1_1") (pintype "passive"))
      (node (ref "C31") (pin "1") (pinfunction "1_1") (pintype "passive"))
      (node (ref "C33") (pin "1") (pinfunction "1_1") (pintype "passive"))
      (node (ref "C34") (pin "1") (pinfunction "1_1") (pintype "passive"))
      (node (ref "C36") (pin "2") (pinfunction "2_2") (pintype "passive"))
      (node (ref "C37") (pin "2") (pinfunction "2_2") (pintype "passive"))
      (node (ref "C38") (pin "2") (pinfunction "2_2") (pintype "passive"))
      (node (ref "C39") (pin "1") (pinfunction "1_1") (pintype "passive"))
      (node (ref "C4") (pin "2") (pinfunction "2_2") (pintype "passive"))
      (node (ref "C40") (pin "2") (pinfunction "2_2") (pintype "passive"))
      (node (ref "C41") (pin "2") (pinfunction "2_2") (pintype "passive"))
      (node (ref "C42") (pin "2") (pinfunction "2_2") (pintype "passive"))
      (node (ref "C46") (pin "2") (pinfunction "2_2") (pintype "passive"))
      (node (ref "C47") (pin "1") (pinfunction "1_1") (pintype "passive"))
      (node (ref "C48") (pin "2") (pinfunction "2_2") (pintype "passive"))
      (node (ref "C49") (pin "2") (pinfunction "2_2") (pintype "passive"))
      (node (ref "C5") (pin "-") (pinfunction "-_-") (pintype "passive"))
      (node (ref "C50") (pin "1") (pinfunction "1_1") (pintype "passive"))
      (node (ref "C51") (pin "-") (pinfunction "-_-") (pintype "passive"))
      (node (ref "C52") (pin "2") (pinfunction "2_2") (pintype "passive"))
      (node (ref "C53") (pin "1") (pinfunction "1_1") (pintype "passive"))
      (node (ref "C54") (pin "1") (pinfunction "1_1") (pintype "passive"))
      (node (ref "C55") (pin "1") (pinfunction "1_1") (pintype "passive"))
      (node (ref "C56") (pin "1") (pinfunction "1_1") (pintype "passive"))
      (node (ref "C57") (pin "2") (pinfunction "2_2") (pintype "passive"))
      (node (ref "C58") (pin "1") (pinfunction "1_1") (pintype "passive"))
      (node (ref "C59") (pin "1") (pinfunction "1_1") (pintype "passive"))
      (node (ref "C60") (pin "1") (pinfunction "1_1") (pintype "passive"))
      (node (ref "C61") (pin "1") (pinfunction "1_1") (pintype "passive"))
      (node (ref "C62") (pin "1") (pinfunction "1_1") (pintype "passive"))
      (node (ref "C63") (pin "1") (pinfunction "1_1") (pintype "passive"))
      (node (ref "C64") (pin "2") (pinfunction "2_2") (pintype "passive"))
      (node (ref "C65") (pin "1") (pinfunction "1_1") (pintype "passive"))
      (node (ref "C66") (pin "1") (pinfunction "1_1") (pintype "passive"))
      (node (ref "C67") (pin "1") (pinfunction "1_1") (pintype "passive"))
      (node (ref "C68") (pin "1") (pinfunction "1_1") (pintype "passive"))
      (node (ref "C69") (pin "1") (pinfunction "1_1") (pintype "passive"))
      (node (ref "C7") (pin "1") (pinfunction "1_1") (pintype "passive"))
      (node (ref "C8") (pin "2") (pinfunction "2_2") (pintype "passive"))
      (node (ref "C9") (pin "1") (pinfunction "1_1") (pintype "passive"))
      (node (ref "D19") (pin "C") (pinfunction "C_C") (pintype "passive"))
      (node (ref "D2") (pin "A") (pinfunction "A_A") (pintype "passive"))
      (node (ref "D3") (pin "C") (pinfunction "C_C") (pintype "passive"))
      (node (ref "IC1") (pin "4") (pinfunction "GND_4") (pintype "passive"))
      (node (ref "IC10") (pin "12") (pinfunction "+IN_12") (pintype "input"))
      (node (ref "IC11") (pin "5") (pinfunction "+IN_5") (pintype "input"))
      (node (ref "IC12") (pin "12") (pinfunction "+IN_12") (pintype "input"))
      (node (ref "IC12") (pin "3") (pinfunction "+IN_3") (pintype "input"))
      (node (ref "IC13") (pin "11") (pinfunction "Y_11") (pintype "tri_state"))
      (node (ref "IC13") (pin "12") (pinfunction "E_12") (pintype "input"))
      (node (ref "IC13") (pin "7") (pinfunction "VSS_7") (pintype "power_in"))
      (node (ref "IC13") (pin "8") (pinfunction "Y_8") (pintype "tri_state"))
      (node (ref "IC14") (pin "4") (pinfunction "VSS_4") (pintype "power_in"))
      (node (ref "IC15") (pin "10") (pinfunction "VSS_10") (pintype "power_in"))
      (node (ref "IC15") (pin "15") (pinfunction "A0_15") (pintype "input"))
      (node (ref "IC15") (pin "16") (pinfunction "A1_16") (pintype "input"))
      (node (ref "IC15") (pin "17") (pinfunction "A2_17") (pintype "input"))
      (node (ref "IC16") (pin "4") (pinfunction "GND_4") (pintype "passive"))
      (node (ref "IC17") (pin "8") (pinfunction "GND_8") (pintype "power_in"))
      (node (ref "IC18") (pin "2") (pinfunction "GND_2") (pintype "passive"))
      (node (ref "IC19") (pin "3") (pinfunction "CLK_3") (pintype "bidirectional"))
      (node (ref "IC19") (pin "4") (pinfunction "DGND_4") (pintype "passive"))
      (node (ref "IC19") (pin "5") (pinfunction "AVSS_5") (pintype "passive"))
      (node (ref "IC19") (pin "8") (pinfunction "REFN0_8") (pintype "input"))
      (node (ref "IC2") (pin "15") (pinfunction "GND2_15") (pintype "passive"))
      (node (ref "IC2") (pin "9") (pinfunction "GND2_2_9") (pintype "passive"))
      (node (ref "IC21") (pin "4") (pinfunction "V-_4") (pintype "power_in"))
      (node (ref "IC3") (pin "4") (pinfunction "GND_4") (pintype "passive"))
      (node (ref "IC4") (pin "5") (pinfunction "GND_5") (pintype "passive"))
      (node (ref "IC5") (pin "15") (pinfunction "GND2_15") (pintype "passive"))
      (node (ref "IC5") (pin "9") (pinfunction "GND2_2_9") (pintype "passive"))
      (node (ref "JP1") (pin "NO") (pinfunction "NO_NO") (pintype "passive"))
      (node (ref "LED4") (pin "C") (pinfunction "C_C") (pintype "passive"))
      (node (ref "Q14") (pin "2") (pinfunction "S_2") (pintype "passive"))
      (node (ref "Q15") (pin "2") (pinfunction "S_2") (pintype "passive"))
      (node (ref "Q16") (pin "C") (pinfunction "C_C") (pintype "passive"))
      (node (ref "Q17") (pin "C") (pinfunction "C_C") (pintype "passive"))
      (node (ref "Q18") (pin "2") (pinfunction "S_2") (pintype "passive"))
      (node (ref "Q21") (pin "2") (pinfunction "S_2") (pintype "passive"))
      (node (ref "Q23") (pin "2") (pinfunction "S_2") (pintype "passive"))
      (node (ref "Q24") (pin "2") (pinfunction "S_2") (pintype "passive"))
      (node (ref "Q25") (pin "2") (pinfunction "S_2") (pintype "passive"))
      (node (ref "Q27") (pin "E") (pinfunction "E_E") (pintype "passive"))
      (node (ref "Q29") (pin "E") (pinfunction "E_E") (pintype "passive"))
      (node (ref "Q32") (pin "2") (pinfunction "S_2") (pintype "passive"))
      (node (ref "R112") (pin "1") (pinfunction "1_1") (pintype "passive"))
      (node (ref "R114") (pin "2") (pinfunction "2_2") (pintype "passive"))
      (node (ref "R115") (pin "2") (pinfunction "2_2") (pintype "passive"))
      (node (ref "R116") (pin "1") (pinfunction "1_1") (pintype "passive"))
      (node (ref "R117") (pin "1") (pinfunction "1_1") (pintype "passive"))
      (node (ref "R118") (pin "2") (pinfunction "2_2") (pintype "passive"))
      (node (ref "R124") (pin "2") (pinfunction "2_2") (pintype "passive"))
      (node (ref "R126") (pin "1") (pinfunction "1_1") (pintype "passive"))
      (node (ref "R135") (pin "1") (pinfunction "1_1") (pintype "passive"))
      (node (ref "R140") (pin "1") (pinfunction "1_1") (pintype "passive"))
      (node (ref "R17") (pin "2") (pinfunction "2_2") (pintype "passive"))
      (node (ref "R27") (pin "1") (pinfunction "1_1") (pintype "passive"))
      (node (ref "R28") (pin "1") (pinfunction "1_1") (pintype "passive"))
      (node (ref "R31") (pin "1") (pinfunction "1_1") (pintype "passive"))
      (node (ref "R5") (pin "2") (pinfunction "2_2") (pintype "passive"))
      (node (ref "R68") (pin "1") (pinfunction "1_1") (pintype "passive"))
      (node (ref "R71") (pin "1") (pinfunction "1_1") (pintype "passive"))
      (node (ref "R74") (pin "2") (pinfunction "2_2") (pintype "passive"))
      (node (ref "R88") (pin "1") (pinfunction "1_1") (pintype "passive"))
      (node (ref "R89") (pin "1") (pinfunction "1_1") (pintype "passive"))
      (node (ref "R90") (pin "2") (pinfunction "2_2") (pintype "passive"))
      (node (ref "R91") (pin "1") (pinfunction "1_1") (pintype "passive"))
      (node (ref "R93") (pin "1") (pinfunction "1_1") (pintype "passive"))
      (node (ref "SH2") (pin "P$2") (pinfunction "GND_B_P$2") (pintype "bidirectional"))
      (node (ref "X2") (pin "2") (pinfunction "1_2") (pintype "passive"))
      (node (ref "X4") (pin "2") (pinfunction "1_2") (pintype "passive"))
      (node (ref "ZD3") (pin "1") (pinfunction "A_1") (pintype "passive"))
      (node (ref "ZD3") (pin "2") (pinfunction "A_2") (pintype "passive"))
    )
    (net (code "37") (name "GNDIO") (class "Default")
      (node (ref "C14") (pin "2") (pinfunction "2_2") (pintype "passive"))
      (node (ref "C16") (pin "1") (pinfunction "1_1") (pintype "passive"))
      (node (ref "C17") (pin "2") (pinfunction "2_2") (pintype "passive"))
      (node (ref "C6") (pin "2") (pinfunction "2_2") (pintype "passive"))
      (node (ref "IC2") (pin "2") (pinfunction "GND1_2_2") (pintype "passive"))
      (node (ref "IC2") (pin "8") (pinfunction "GND1_8") (pintype "passive"))
      (node (ref "IC5") (pin "2") (pinfunction "GND1_2_2") (pintype "passive"))
      (node (ref "IC5") (pin "8") (pinfunction "GND1_8") (pintype "passive"))
      (node (ref "IC6") (pin "4") (pinfunction "GND_4") (pintype "passive"))
      (node (ref "IC6") (pin "7") (pinfunction "WP_7") (pintype "input"))
      (node (ref "IC7") (pin "4") (pinfunction "GND_4") (pintype "passive"))
      (node (ref "X1") (pin "11") (pinfunction "1_11") (pintype "passive"))
      (node (ref "X1") (pin "16") (pinfunction "1_16") (pintype "passive"))
      (node (ref "X1") (pin "20") (pinfunction "1_20") (pintype "passive"))
      (node (ref "X1") (pin "25") (pinfunction "1_25") (pintype "passive"))
      (node (ref "X1") (pin "26") (pinfunction "1_26") (pintype "passive"))
      (node (ref "X1") (pin "7") (pinfunction "1_7") (pintype "passive"))
    )
    (net (code "38") (name "IRQ") (class "Default")
      (node (ref "JP4") (pin "COM") (pinfunction "COM_COM") (pintype "passive"))
      (node (ref "RN2") (pin "5") (pinfunction "2_5") (pintype "passive"))
    )
    (net (code "39") (name "ISENSE+") (class "Default")
      (node (ref "IC10") (pin "6") (pinfunction "-IN_6") (pintype "input"))
      (node (ref "R51") (pin "2") (pinfunction "2_2") (pintype "passive"))
      (node (ref "R52") (pin "2") (pinfunction "2_2") (pintype "passive"))
      (node (ref "R54") (pin "1") (pinfunction "1_1") (pintype "passive"))
      (node (ref "R55") (pin "2") (pinfunction "2_2") (pintype "passive"))
      (node (ref "R58") (pin "2") (pinfunction "2_2") (pintype "passive"))
    )
    (net (code "40") (name "ISENSE-") (class "Default")
      (node (ref "IC10") (pin "5") (pinfunction "+IN_5") (pintype "input"))
      (node (ref "R66") (pin "2") (pinfunction "2_2") (pintype "passive"))
      (node (ref "R68") (pin "2") (pinfunction "2_2") (pintype "passive"))
    )
    (net (code "41") (name "I_CTRL") (class "Default")
      (node (ref "IC10") (pin "8") (pinfunction "OUT_8") (pintype "output"))
      (node (ref "R43") (pin "1") (pinfunction "1_1") (pintype "passive"))
      (node (ref "R59") (pin "2") (pinfunction "2_2") (pintype "passive"))
    )
    (net (code "42") (name "I_MON") (class "Default")
      (node (ref "IC10") (pin "14") (pinfunction "OUT_14") (pintype "output"))
      (node (ref "R100") (pin "1") (pinfunction "1_1") (pintype "passive"))
      (node (ref "R50") (pin "2") (pinfunction "2_2") (pintype "passive"))
    )
    (net (code "43") (name "I_SERVO") (class "Default")
      (node (ref "C32") (pin "2") (pinfunction "2_2") (pintype "passive"))
      (node (ref "D12") (pin "C") (pinfunction "C_C") (pintype "passive"))
      (node (ref "D13") (pin "A") (pinfunction "A_A") (pintype "passive"))
      (node (ref "IC9") (pin "1") (pinfunction "OUT_1") (pintype "output"))
      (node (ref "R123") (pin "1") (pinfunction "1_1") (pintype "passive"))
    )
    (net (code "44") (name "I_SET") (class "Default")
      (node (ref "IC17") (pin "4") (pinfunction "VOUTA_4") (pintype "output"))
      (node (ref "R42") (pin "1") (pinfunction "1_1") (pintype "passive"))
      (node (ref "R95") (pin "1") (pinfunction "1_1") (pintype "passive"))
    )
    (net (code "45") (name "MISO") (class "Default")
      (node (ref "IC15") (pin "14") (pinfunction "SO_14") (pintype "output"))
      (node (ref "IC19") (pin "15") (pinfunction "DOUT/~{DRDY}_15") (pintype "output"))
      (node (ref "RN2") (pin "7") (pinfunction "2_7") (pintype "passive"))
    )
    (net (code "46") (name "MOSI") (class "Default")
      (node (ref "IC15") (pin "13") (pinfunction "SI_13") (pintype "input"))
      (node (ref "IC17") (pin "7") (pinfunction "DIN_7") (pintype "input"))
      (node (ref "IC19") (pin "16") (pinfunction "DIN_16") (pintype "input"))
      (node (ref "RN2") (pin "6") (pinfunction "2_6") (pintype "passive"))
    )
    (net (code "47") (name "Net-(C1-Pad2)") (class "Default")
      (node (ref "C1") (pin "2") (pinfunction "2_2") (pintype "passive"))
      (node (ref "JP1") (pin "COM") (pinfunction "COM_COM") (pintype "passive"))
      (node (ref "R2") (pin "2") (pinfunction "2_2") (pintype "passive"))
      (node (ref "R3") (pin "2") (pinfunction "2_2") (pintype "passive"))
    )
    (net (code "48") (name "Net-(C22-Pad2)") (class "Default")
      (node (ref "C22") (pin "2") (pinfunction "2_2") (pintype "passive"))
      (node (ref "R25") (pin "1") (pinfunction "1_1") (pintype "passive"))
    )
    (net (code "49") (name "Net-(C23-Pad1)") (class "Default")
      (node (ref "C23") (pin "1") (pinfunction "1_1") (pintype "passive"))
      (node (ref "R21") (pin "1") (pinfunction "1_1") (pintype "passive"))
    )
    (net (code "50") (name "Net-(C24-Pad1)") (class "Default")
      (node (ref "C24") (pin "1") (pinfunction "1_1") (pintype "passive"))
      (node (ref "R29") (pin "2") (pinfunction "2_2") (pintype "passive"))
      (node (ref "R30") (pin "1") (pinfunction "1_1") (pintype "passive"))
    )
    (net (code "51") (name "Net-(C25-Pad2)") (class "Default")
      (node (ref "C25") (pin "2") (pinfunction "2_2") (pintype "passive"))
      (node (ref "R32") (pin "1") (pinfunction "1_1") (pintype "passive"))
    )
    (net (code "52") (name "Net-(C26-Pad1)") (class "Default")
      (node (ref "C26") (pin "1") (pinfunction "1_1") (pintype "passive"))
      (node (ref "R38") (pin "2") (pinfunction "2_2") (pintype "passive"))
      (node (ref "R39") (pin "1") (pinfunction "1_1") (pintype "passive"))
    )
    (net (code "53") (name "Net-(C28-Pad2)") (class "Default")
      (node (ref "C28") (pin "2") (pinfunction "2_2") (pintype "passive"))
      (node (ref "R40") (pin "1") (pinfunction "1_1") (pintype "passive"))
    )
    (net (code "54") (name "Net-(C29-Pad2)") (class "Default")
      (node (ref "C29") (pin "2") (pinfunction "2_2") (pintype "passive"))
      (node (ref "R41") (pin "1") (pinfunction "1_1") (pintype "passive"))
    )
    (net (code "55") (name "Net-(C32-Pad1)") (class "Default")
      (node (ref "C32") (pin "1") (pinfunction "1_1") (pintype "passive"))
      (node (ref "R44") (pin "1") (pinfunction "1_1") (pintype "passive"))
    )
    (net (code "56") (name "Net-(C35-Pad2)") (class "Default")
      (node (ref "C35") (pin "2") (pinfunction "2_2") (pintype "passive"))
      (node (ref "R46") (pin "1") (pinfunction "1_1") (pintype "passive"))
    )
    (net (code "57") (name "Net-(C44-Pad1)") (class "Default")
      (node (ref "C44") (pin "1") (pinfunction "1_1") (pintype "passive"))
      (node (ref "R75") (pin "1") (pinfunction "1_1") (pintype "passive"))
      (node (ref "R76") (pin "2") (pinfunction "2_2") (pintype "passive"))
    )
    (net (code "58") (name "Net-(C45-Pad1)") (class "Default")
      (node (ref "C45") (pin "1") (pinfunction "1_1") (pintype "passive"))
      (node (ref "R83") (pin "1") (pinfunction "1_1") (pintype "passive"))
      (node (ref "R86") (pin "2") (pinfunction "2_2") (pintype "passive"))
    )
    (net (code "59") (name "Net-(C70-Pad2)") (class "Default")
      (node (ref "C70") (pin "2") (pinfunction "2_2") (pintype "passive"))
      (node (ref "Q28") (pin "B") (pinfunction "B_B") (pintype "passive"))
      (node (ref "R125") (pin "1") (pinfunction "1_1") (pintype "passive"))
      (node (ref "R128") (pin "2") (pinfunction "2_2") (pintype "passive"))
      (node (ref "R130") (pin "2") (pinfunction "2_2") (pintype "passive"))
    )
    (net (code "60") (name "Net-(C72-Pad1)") (class "Default")
      (node (ref "C72") (pin "1") (pinfunction "1_1") (pintype "passive"))
      (node (ref "Q27") (pin "B") (pinfunction "B_B") (pintype "passive"))
      (node (ref "R126") (pin "2") (pinfunction "2_2") (pintype "passive"))
      (node (ref "R127") (pin "2") (pinfunction "2_2") (pintype "passive"))
    )
    (net (code "61") (name "Net-(C72-Pad2)") (class "Default")
      (node (ref "C72") (pin "2") (pinfunction "2_2") (pintype "passive"))
      (node (ref "Q28") (pin "C") (pinfunction "C_C") (pintype "passive"))
      (node (ref "R127") (pin "1") (pinfunction "1_1") (pintype "passive"))
      (node (ref "R132") (pin "2") (pinfunction "2_2") (pintype "passive"))
    )
    (net (code "62") (name "Net-(C73-Pad2)") (class "Default")
      (node (ref "C73") (pin "2") (pinfunction "2_2") (pintype "passive"))
      (node (ref "R133") (pin "2") (pinfunction "2_2") (pintype "passive"))
    )
    (net (code "63") (name "Net-(C76-Pad1)") (class "Default")
      (node (ref "C76") (pin "1") (pinfunction "1_1") (pintype "passive"))
      (node (ref "Q30") (pin "B") (pinfunction "B_B") (pintype "passive"))
      (node (ref "R134") (pin "1") (pinfunction "1_1") (pintype "passive"))
      (node (ref "R136") (pin "2") (pinfunction "2_2") (pintype "passive"))
    )
    (net (code "64") (name "Net-(D5-PadC)") (class "Default")
      (node (ref "D5") (pin "C") (pinfunction "C_C") (pintype "passive"))
      (node (ref "Q2") (pin "2") (pinfunction "C_2") (pintype "passive"))
      (node (ref "Q2") (pin "4") (pinfunction "C_4") (pintype "passive"))
    )
    (net (code "65") (name "Net-(D7-PadC)") (class "Default")
      (node (ref "D7") (pin "C") (pinfunction "C_C") (pintype "passive"))
      (node (ref "ZD2") (pin "C") (pinfunction "C_C") (pintype "passive"))
    )
    (net (code "66") (name "Net-(D8-PadC)") (class "Default")
      (node (ref "D8") (pin "C") (pinfunction "C_C") (pintype "passive"))
      (node (ref "Q6") (pin "2") (pinfunction "C_2") (pintype "passive"))
      (node (ref "Q6") (pin "4") (pinfunction "C_4") (pintype "passive"))
      (node (ref "ZD2") (pin "A") (pinfunction "A_A") (pintype "passive"))
    )
    (net (code "67") (name "Net-(D9-PadC)") (class "Default")
      (node (ref "D9") (pin "C") (pinfunction "C_C") (pintype "passive"))
      (node (ref "ZD1") (pin "C") (pinfunction "C_C") (pintype "passive"))
    )
    (net (code "68") (name "Net-(D10-PadA)") (class "Default")
      (node (ref "D10") (pin "A") (pinfunction "A_A") (pintype "passive"))
      (node (ref "D12") (pin "A") (pinfunction "A_A") (pintype "passive"))
      (node (ref "R34") (pin "1") (pinfunction "1_1") (pintype "passive"))
    )
    (net (code "69") (name "Net-(D14-PadA)") (class "Default")
      (node (ref "D14") (pin "A") (pinfunction "A_A") (pintype "passive"))
      (node (ref "R47") (pin "2") (pinfunction "2_2") (pintype "passive"))
    )
    (net (code "70") (name "Net-(D15-PadC)") (class "Default")
      (node (ref "D15") (pin "C") (pinfunction "C_C") (pintype "passive"))
      (node (ref "R60") (pin "2") (pinfunction "2_2") (pintype "passive"))
      (node (ref "R61") (pin "1") (pinfunction "1_1") (pintype "passive"))
      (node (ref "R62") (pin "1") (pinfunction "1_1") (pintype "passive"))
      (node (ref "R72") (pin "2") (pinfunction "2_2") (pintype "passive"))
    )
    (net (code "71") (name "Net-(D16-PadA)") (class "Default")
      (node (ref "D16") (pin "A") (pinfunction "A_A") (pintype "passive"))
      (node (ref "R65") (pin "1") (pinfunction "1_1") (pintype "passive"))
    )
    (net (code "72") (name "Net-(D18-PadA)") (class "Default")
      (node (ref "D18") (pin "A") (pinfunction "A_A") (pintype "passive"))
      (node (ref "Q22") (pin "B") (pinfunction "B_B") (pintype "passive"))
      (node (ref "R110") (pin "1") (pinfunction "1_1") (pintype "passive"))
      (node (ref "R116") (pin "2") (pinfunction "2_2") (pintype "passive"))
    )
    (net (code "73") (name "Net-(D18-PadC)") (class "Default")
      (node (ref "D18") (pin "C") (pinfunction "C_C") (pintype "passive"))
      (node (ref "D19") (pin "A") (pinfunction "A_A") (pintype "passive"))
    )
    (net (code "74") (name "Net-(D20-C)") (class "Default")
      (node (ref "C70") (pin "1") (pinfunction "1_1") (pintype "passive"))
      (node (ref "C71") (pin "1") (pinfunction "1_1") (pintype "passive"))
      (node (ref "C73") (pin "1") (pinfunction "1_1") (pintype "passive"))
      (node (ref "C74") (pin "+") (pinfunction "+_+") (pintype "passive"))
      (node (ref "D20") (pin "3") (pinfunction "C_3") (pintype "passive"))
      (node (ref "F1") (pin "2") (pinfunction "2_2") (pintype "passive"))
      (node (ref "F2") (pin "1") (pinfunction "1_1") (pintype "passive"))
      (node (ref "K1") (pin "2") (pinfunction "O_2") (pintype "passive"))
      (node (ref "Q28") (pin "E") (pinfunction "E_E") (pintype "passive"))
      (node (ref "R125") (pin "2") (pinfunction "2_2") (pintype "passive"))
    )
    (net (code "75") (name "Net-(FB1-1)") (class "Default")
      (node (ref "FB1") (pin "P$1") (pinfunction "1_P$1") (pintype "passive"))
      (node (ref "X2") (pin "3") (pinfunction "1_3") (pintype "passive"))
    )
    (net (code "76") (name "Net-(FB4-1)") (class "Default")
      (node (ref "FB4") (pin "P$1") (pinfunction "1_P$1") (pintype "passive"))
      (node (ref "X2") (pin "1") (pinfunction "1_1") (pintype "passive"))
    )
    (net (code "77") (name "Net-(FB8-2)") (class "Default")
      (node (ref "C21") (pin "1") (pinfunction "1_1") (pintype "passive"))
      (node (ref "FB8") (pin "P$2") (pinfunction "2_P$2") (pintype "passive"))
      (node (ref "Q4") (pin "2") (pinfunction "C_2") (pintype "passive"))
      (node (ref "Q4") (pin "4") (pinfunction "C_4") (pintype "passive"))
      (node (ref "R19") (pin "2") (pinfunction "2_2") (pintype "passive"))
      (node (ref "R20") (pin "2") (pinfunction "2_2") (pintype "passive"))
    )
    (net (code "78") (name "Net-(IC1-FB)") (class "Default")
      (node (ref "IC1") (pin "7") (pinfunction "FB_7") (pintype "input"))
      (node (ref "R4") (pin "2") (pinfunction "2_2") (pintype "passive"))
      (node (ref "R5") (pin "1") (pinfunction "1_1") (pintype "passive"))
    )
    (net (code "79") (name "Net-(IC2-B1)") (class "Default")
      (node (ref "IC2") (pin "14") (pinfunction "B1_14") (pintype "output"))
      (node (ref "RN2") (pin "1") (pinfunction "1_1") (pintype "passive"))
    )
    (net (code "80") (name "Net-(IC2-B4)") (class "Default")
      (node (ref "IC2") (pin "11") (pinfunction "B4_11") (pintype "input"))
      (node (ref "RN2") (pin "2") (pinfunction "1_2") (pintype "passive"))
    )
    (net (code "81") (name "Net-(IC3-Y0)") (class "Default")
      (node (ref "IC3") (pin "7") (pinfunction "Y0_7") (pintype "output"))
      (node (ref "RN1") (pin "1") (pinfunction "1_1") (pintype "passive"))
    )
    (net (code "82") (name "Net-(IC3-Y1)") (class "Default")
      (node (ref "IC3") (pin "6") (pinfunction "Y1_6") (pintype "output"))
      (node (ref "RN1") (pin "2") (pinfunction "1_2") (pintype "passive"))
    )
    (net (code "83") (name "Net-(IC3-Y3)") (class "Default")
      (node (ref "IC3") (pin "3") (pinfunction "Y3_3") (pintype "output"))
      (node (ref "RN1") (pin "4") (pinfunction "1_4") (pintype "passive"))
    )
    (net (code "84") (name "Net-(IC5-B1)") (class "Default")
      (node (ref "IC5") (pin "14") (pinfunction "B1_14") (pintype "output"))
      (node (ref "RN2") (pin "3") (pinfunction "1_3") (pintype "passive"))
    )
    (net (code "85") (name "Net-(IC5-B4)") (class "Default")
      (node (ref "IC5") (pin "11") (pinfunction "B4_11") (pintype "input"))
      (node (ref "RN2") (pin "4") (pinfunction "1_4") (pintype "passive"))
    )
    (net (code "86") (name "Net-(IC8A-+IN)") (class "Default")
      (node (ref "IC8") (pin "3") (pinfunction "+IN_3") (pintype "input"))
      (node (ref "R32") (pin "2") (pinfunction "2_2") (pintype "passive"))
      (node (ref "R33") (pin "2") (pinfunction "2_2") (pintype "passive"))
    )
    (net (code "87") (name "Net-(IC8A--IN)") (class "Default")
      (node (ref "C27") (pin "1") (pinfunction "1_1") (pintype "passive"))
      (node (ref "D11") (pin "C") (pinfunction "C_C") (pintype "passive"))
      (node (ref "IC8") (pin "2") (pinfunction "-IN_2") (pintype "input"))
      (node (ref "R36") (pin "2") (pinfunction "2_2") (pintype "passive"))
      (node (ref "R41") (pin "2") (pinfunction "2_2") (pintype "passive"))
    )
    (net (code "88") (name "Net-(IC8B-+IN)") (class "Default")
      (node (ref "IC8") (pin "5") (pinfunction "+IN_5") (pintype "input"))
      (node (ref "R24") (pin "2") (pinfunction "2_2") (pintype "passive"))
      (node (ref "R25") (pin "2") (pinfunction "2_2") (pintype "passive"))
      (node (ref "R29") (pin "1") (pinfunction "1_1") (pintype "passive"))
    )
    (net (code "89") (name "Net-(IC8B--IN)") (class "Default")
      (node (ref "IC8") (pin "6") (pinfunction "-IN_6") (pintype "input"))
      (node (ref "R37") (pin "2") (pinfunction "2_2") (pintype "passive"))
      (node (ref "R38") (pin "1") (pinfunction "1_1") (pintype "passive"))
      (node (ref "R40") (pin "2") (pinfunction "2_2") (pintype "passive"))
    )
    (net (code "90") (name "Net-(IC9A-+IN)") (class "Default")
      (node (ref "IC9") (pin "3") (pinfunction "+IN_3") (pintype "input"))
      (node (ref "R42") (pin "2") (pinfunction "2_2") (pintype "passive"))
    )
    (net (code "91") (name "Net-(IC9A--IN)") (class "Default")
      (node (ref "D13") (pin "C") (pinfunction "C_C") (pintype "passive"))
      (node (ref "IC9") (pin "2") (pinfunction "-IN_2") (pintype "input"))
      (node (ref "R43") (pin "2") (pinfunction "2_2") (pintype "passive"))
      (node (ref "R45") (pin "2") (pinfunction "2_2") (pintype "passive"))
      (node (ref "R46") (pin "2") (pinfunction "2_2") (pintype "passive"))
    )
    (net (code "92") (name "Net-(IC9B-+IN)") (class "Default")
      (node (ref "C20") (pin "1") (pinfunction "1_1") (pintype "passive"))
      (node (ref "IC9") (pin "5") (pinfunction "+IN_5") (pintype "input"))
      (node (ref "R14") (pin "2") (pinfunction "2_2") (pintype "passive"))
      (node (ref "R17") (pin "1") (pinfunction "1_1") (pintype "passive"))
    )
    (net (code "93") (name "Net-(IC9B--IN)") (class "Default")
      (node (ref "IC9") (pin "6") (pinfunction "-IN_6") (pintype "input"))
      (node (ref "IC9") (pin "7") (pinfunction "OUT_7") (pintype "output"))
      (node (ref "R24") (pin "1") (pinfunction "1_1") (pintype "passive"))
    )
    (net (code "94") (name "Net-(IC10A-+IN)") (class "Default")
      (node (ref "IC10") (pin "3") (pinfunction "+IN_3") (pintype "input"))
      (node (ref "R73") (pin "1") (pinfunction "1_1") (pintype "passive"))
      (node (ref "R74") (pin "1") (pinfunction "1_1") (pintype "passive"))
    )
    (net (code "95") (name "Net-(IC10A--IN)") (class "Default")
      (node (ref "C43") (pin "1") (pinfunction "1_1") (pintype "passive"))
      (node (ref "IC10") (pin "2") (pinfunction "-IN_2") (pintype "input"))
      (node (ref "R64") (pin "2") (pinfunction "2_2") (pintype "passive"))
      (node (ref "R67") (pin "1") (pinfunction "1_1") (pintype "passive"))
    )
    (net (code "96") (name "Net-(IC10A-OUT)") (class "Default")
      (node (ref "C43") (pin "2") (pinfunction "2_2") (pintype "passive"))
      (node (ref "IC10") (pin "1") (pinfunction "OUT_1") (pintype "output"))
      (node (ref "R64") (pin "1") (pinfunction "1_1") (pintype "passive"))
      (node (ref "R69") (pin "2") (pinfunction "2_2") (pintype "passive"))
      (node (ref "R80") (pin "2") (pinfunction "2_2") (pintype "passive"))
    )
    (net (code "97") (name "Net-(IC10B-OUT)") (class "Default")
      (node (ref "IC10") (pin "7") (pinfunction "OUT_7") (pintype "output"))
      (node (ref "R53") (pin "1") (pinfunction "1_1") (pintype "passive"))
      (node (ref "R54") (pin "2") (pinfunction "2_2") (pintype "passive"))
      (node (ref "R63") (pin "1") (pinfunction "1_1") (pintype "passive"))
    )
    (net (code "98") (name "Net-(IC10C-+IN)") (class "Default")
      (node (ref "IC10") (pin "10") (pinfunction "+IN_10") (pintype "input"))
      (node (ref "R70") (pin "1") (pinfunction "1_1") (pintype "passive"))
      (node (ref "R71") (pin "2") (pinfunction "2_2") (pintype "passive"))
    )
    (net (code "99") (name "Net-(IC10C--IN)") (class "Default")
      (node (ref "IC10") (pin "9") (pinfunction "-IN_9") (pintype "input"))
      (node (ref "R59") (pin "1") (pinfunction "1_1") (pintype "passive"))
      (node (ref "R63") (pin "2") (pinfunction "2_2") (pintype "passive"))
    )
    (net (code "100") (name "Net-(IC10D--IN)") (class "Default")
      (node (ref "IC10") (pin "13") (pinfunction "-IN_13") (pintype "input"))
      (node (ref "R50") (pin "1") (pinfunction "1_1") (pintype "passive"))
      (node (ref "R53") (pin "2") (pinfunction "2_2") (pintype "passive"))
    )
    (net (code "101") (name "Net-(IC11A-+IN)") (class "Default")
      (node (ref "IC11") (pin "3") (pinfunction "+IN_3") (pintype "input"))
      (node (ref "IC13") (pin "2") (pinfunction "Z_2") (pintype "tri_state"))
      (node (ref "IC13") (pin "3") (pinfunction "Z_3") (pintype "tri_state"))
      (node (ref "IC13") (pin "9") (pinfunction "Z_9") (pintype "tri_state"))
    )
    (net (code "102") (name "Net-(IC11A--IN)") (class "Default")
      (node (ref "IC11") (pin "1") (pinfunction "OUT_1") (pintype "output"))
      (node (ref "IC11") (pin "2") (pinfunction "-IN_2") (pintype "input"))
      (node (ref "R70") (pin "2") (pinfunction "2_2") (pintype "passive"))
    )
    (net (code "103") (name "Net-(IC11B--IN)") (class "Default")
      (node (ref "IC11") (pin "6") (pinfunction "-IN_6") (pintype "input"))
      (node (ref "R85") (pin "2") (pinfunction "2_2") (pintype "passive"))
      (node (ref "R87") (pin "1") (pinfunction "1_1") (pintype "passive"))
    )
    (net (code "104") (name "Net-(IC11B-OUT)") (class "Default")
      (node (ref "IC11") (pin "7") (pinfunction "OUT_7") (pintype "output"))
      (node (ref "R82") (pin "2") (pinfunction "2_2") (pintype "passive"))
      (node (ref "R85") (pin "1") (pinfunction "1_1") (pintype "passive"))
    )
    (net (code "105") (name "Net-(IC12A--IN)") (class "Default")
      (node (ref "IC12") (pin "2") (pinfunction "-IN_2") (pintype "input"))
      (node (ref "R77") (pin "2") (pinfunction "2_2") (pintype "passive"))
      (node (ref "R81") (pin "1") (pinfunction "1_1") (pintype "passive"))
    )
    (net (code "106") (name "Net-(IC12A-OUT)") (class "Default")
      (node (ref "IC12") (pin "1") (pinfunction "OUT_1") (pintype "output"))
      (node (ref "R77") (pin "1") (pinfunction "1_1") (pintype "passive"))
      (node (ref "R78") (pin "2") (pinfunction "2_2") (pintype "passive"))
    )
    (net (code "107") (name "Net-(IC12B-+IN)") (class "Default")
      (node (ref "IC12") (pin "5") (pinfunction "+IN_5") (pintype "input"))
      (node (ref "R75") (pin "2") (pinfunction "2_2") (pintype "passive"))
      (node (ref "R78") (pin "1") (pinfunction "1_1") (pintype "passive"))
    )
    (net (code "108") (name "Net-(IC12B--IN)") (class "Default")
      (node (ref "D16") (pin "C") (pinfunction "C_C") (pintype "passive"))
      (node (ref "IC12") (pin "6") (pinfunction "-IN_6") (pintype "input"))
      (node (ref "R69") (pin "1") (pinfunction "1_1") (pintype "passive"))
    )
    (net (code "109") (name "Net-(IC12B-OUT)") (class "Default")
      (node (ref "C44") (pin "2") (pinfunction "2_2") (pintype "passive"))
      (node (ref "IC12") (pin "7") (pinfunction "OUT_7") (pintype "output"))
      (node (ref "R56") (pin "2") (pinfunction "2_2") (pintype "passive"))
      (node (ref "R76") (pin "1") (pinfunction "1_1") (pintype "passive"))
    )
    (net (code "110") (name "Net-(IC12C-+IN)") (class "Default")
      (node (ref "IC12") (pin "10") (pinfunction "+IN_10") (pintype "input"))
      (node (ref "R82") (pin "1") (pinfunction "1_1") (pintype "passive"))
      (node (ref "R83") (pin "2") (pinfunction "2_2") (pintype "passive"))
    )
    (net (code "111") (name "Net-(IC12C--IN)") (class "Default")
      (node (ref "IC12") (pin "9") (pinfunction "-IN_9") (pintype "input"))
      (node (ref "R80") (pin "1") (pinfunction "1_1") (pintype "passive"))
    )
    (net (code "112") (name "Net-(IC12C-OUT)") (class "Default")
      (node (ref "C45") (pin "2") (pinfunction "2_2") (pintype "passive"))
      (node (ref "IC12") (pin "8") (pinfunction "OUT_8") (pintype "output"))
      (node (ref "R57") (pin "2") (pinfunction "2_2") (pintype "passive"))
      (node (ref "R65") (pin "2") (pinfunction "2_2") (pintype "passive"))
      (node (ref "R86") (pin "1") (pinfunction "1_1") (pintype "passive"))
    )
    (net (code "113") (name "Net-(IC12D--IN)") (class "Default")
      (node (ref "IC12") (pin "13") (pinfunction "-IN_13") (pintype "input"))
      (node (ref "IC12") (pin "14") (pinfunction "OUT_14") (pintype "output"))
    )
    (net (code "114") (name "Net-(IC13A-Y)") (class "Default")
      (node (ref "IC13") (pin "1") (pinfunction "Y_1") (pintype "tri_state"))
      (node (ref "R79") (pin "1") (pinfunction "1_1") (pintype "passive"))
      (node (ref "R84") (pin "2") (pinfunction "2_2") (pintype "passive"))
    )
    (net (code "115") (name "Net-(IC13B-Y)") (class "Default")
      (node (ref "IC13") (pin "4") (pinfunction "Y_4") (pintype "tri_state"))
      (node (ref "R84") (pin "1") (pinfunction "1_1") (pintype "passive"))
      (node (ref "R88") (pin "2") (pinfunction "2_2") (pintype "passive"))
    )
    (net (code "116") (name "Net-(IC14A-Q)") (class "Default")
      (node (ref "IC14") (pin "5") (pinfunction "Q_5") (pintype "output"))
      (node (ref "JP3") (pin "2") (pinfunction "2_2") (pintype "passive"))
      (node (ref "Q18") (pin "1") (pinfunction "G_1") (pintype "passive"))
      (node (ref "R89") (pin "2") (pinfunction "2_2") (pintype "passive"))
    )
    (net (code "117") (name "Net-(IC15-INTA)") (class "Default")
      (node (ref "IC15") (pin "20") (pinfunction "INTA_20") (pintype "output"))
      (node (ref "JP4") (pin "NO") (pinfunction "NO_NO") (pintype "passive"))
    )
    (net (code "118") (name "Net-(IC16-TRIM{slash}NR)") (class "Default")
      (node (ref "C52") (pin "1") (pinfunction "1_1") (pintype "passive"))
      (node (ref "IC16") (pin "5") (pinfunction "TRIM/NR_5") (pintype "input"))
    )
    (net (code "119") (name "Net-(IC18-NO)") (class "Default")
      (node (ref "C56") (pin "2") (pinfunction "2_2") (pintype "passive"))
      (node (ref "IC18") (pin "1") (pinfunction "NO_1") (pintype "bidirectional"))
      (node (ref "R97") (pin "1") (pinfunction "1_1") (pintype "passive"))
      (node (ref "ZD3") (pin "3") (pinfunction "C_3") (pintype "passive"))
    )
    (net (code "120") (name "Net-(IC19-AIN0{slash}REFP1)") (class "Default")
      (node (ref "C58") (pin "2") (pinfunction "2_2") (pintype "passive"))
      (node (ref "IC19") (pin "11") (pinfunction "AIN0/REFP1_11") (pintype "input"))
      (node (ref "R99") (pin "2") (pinfunction "2_2") (pintype "passive"))
    )
    (net (code "121") (name "Net-(IC19-AIN1)") (class "Default")
      (node (ref "C54") (pin "2") (pinfunction "2_2") (pintype "passive"))
      (node (ref "IC19") (pin "10") (pinfunction "AIN1_10") (pintype "input"))
      (node (ref "R95") (pin "2") (pinfunction "2_2") (pintype "passive"))
    )
    (net (code "122") (name "Net-(IC19-AIN2)") (class "Default")
      (node (ref "C55") (pin "2") (pinfunction "2_2") (pintype "passive"))
      (node (ref "IC19") (pin "7") (pinfunction "AIN2_7") (pintype "input"))
      (node (ref "R96") (pin "2") (pinfunction "2_2") (pintype "passive"))
    )
    (net (code "123") (name "Net-(IC19-AIN3{slash}REFN1)") (class "Default")
      (node (ref "C57") (pin "1") (pinfunction "1_1") (pintype "passive"))
      (node (ref "IC19") (pin "6") (pinfunction "AIN3/REFN1_6") (pintype "input"))
      (node (ref "R100") (pin "2") (pinfunction "2_2") (pintype "passive"))
    )
    (net (code "124") (name "Net-(IC19-AVDD)") (class "Default")
      (node (ref "C61") (pin "2") (pinfunction "2_2") (pintype "passive"))
      (node (ref "C62") (pin "2") (pinfunction "2_2") (pintype "passive"))
      (node (ref "IC19") (pin "12") (pinfunction "AVDD_12") (pintype "power_in"))
      (node (ref "R101") (pin "2") (pinfunction "2_2") (pintype "passive"))
    )
    (net (code "125") (name "Net-(IC19-~{DRDY})") (class "Default")
      (node (ref "IC19") (pin "14") (pinfunction "~{DRDY}_14") (pintype "output"))
      (node (ref "JP4") (pin "NC") (pinfunction "NC_NC") (pintype "passive"))
    )
    (net (code "126") (name "Net-(IC20A-+IN)") (class "Default")
      (node (ref "IC20") (pin "7") (pinfunction "+IN_7") (pintype "input"))
      (node (ref "IC20") (pin "9") (pinfunction "+IN_9") (pintype "input"))
      (node (ref "R106") (pin "1") (pinfunction "1_1") (pintype "passive"))
      (node (ref "R112") (pin "2") (pinfunction "2_2") (pintype "passive"))
    )
    (net (code "127") (name "Net-(IC20A--IN)") (class "Default")
      (node (ref "IC20") (pin "5") (pinfunction "+IN_5") (pintype "input"))
      (node (ref "IC20") (pin "6") (pinfunction "-IN_6") (pintype "input"))
      (node (ref "R102") (pin "2") (pinfunction "2_2") (pintype "passive"))
    )
    (net (code "128") (name "Net-(IC20A-OUT)") (class "Default")
      (node (ref "IC20") (pin "1") (pinfunction "OUT_1") (pintype "open_collector"))
      (node (ref "IC20") (pin "2") (pinfunction "OUT_2") (pintype "open_collector"))
      (node (ref "R107") (pin "1") (pinfunction "1_1") (pintype "passive"))
    )
    (net (code "129") (name "Net-(IC20B--IN)") (class "Default")
      (node (ref "IC20") (pin "10") (pinfunction "-IN_10") (pintype "input"))
      (node (ref "IC20") (pin "4") (pinfunction "-IN_4") (pintype "input"))
      (node (ref "R118") (pin "1") (pinfunction "1_1") (pintype "passive"))
      (node (ref "R120") (pin "2") (pinfunction "2_2") (pintype "passive"))
    )
    (net (code "130") (name "Net-(IC20C--IN)") (class "Default")
      (node (ref "IC20") (pin "11") (pinfunction "+IN_11") (pintype "input"))
      (node (ref "IC20") (pin "8") (pinfunction "-IN_8") (pintype "input"))
      (node (ref "R123") (pin "2") (pinfunction "2_2") (pintype "passive"))
    )
    (net (code "131") (name "Net-(IC20C-OUT)") (class "Default")
      (node (ref "IC20") (pin "13") (pinfunction "OUT_13") (pintype "open_collector"))
      (node (ref "IC20") (pin "14") (pinfunction "OUT_14") (pintype "open_collector"))
      (node (ref "R122") (pin "1") (pinfunction "1_1") (pintype "passive"))
    )
    (net (code "132") (name "Net-(IC21A-+IN)") (class "Default")
      (node (ref "C67") (pin "2") (pinfunction "2_2") (pintype "passive"))
      (node (ref "IC21") (pin "2") (pinfunction "+IN_2") (pintype "input"))
      (node (ref "Q21") (pin "3") (pinfunction "D_3") (pintype "passive"))
      (node (ref "R103") (pin "2") (pinfunction "2_2") (pintype "passive"))
    )
    (net (code "133") (name "Net-(IC21A--IN)") (class "Default")
      (node (ref "C69") (pin "2") (pinfunction "2_2") (pintype "passive"))
      (node (ref "IC21") (pin "3") (pinfunction "-IN_3") (pintype "input"))
      (node (ref "R109") (pin "2") (pinfunction "2_2") (pintype "passive"))
      (node (ref "R114") (pin "1") (pinfunction "1_1") (pintype "passive"))
    )
    (net (code "134") (name "Net-(IC21A-BAL{slash}STRB)") (class "Default")
      (node (ref "IC21") (pin "6") (pinfunction "BAL/STRB_6") (pintype "input"))
      (node (ref "Q26") (pin "C") (pinfunction "C_C") (pintype "passive"))
    )
    (net (code "135") (name "Net-(IC21A-E)") (class "Default")
      (node (ref "IC21") (pin "1") (pinfunction "E_1") (pintype "passive"))
      (node (ref "Q21") (pin "1") (pinfunction "G_1") (pintype "passive"))
      (node (ref "Q25") (pin "1") (pinfunction "G_1") (pintype "passive"))
      (node (ref "R110") (pin "2") (pinfunction "2_2") (pintype "passive"))
      (node (ref "R115") (pin "1") (pinfunction "1_1") (pintype "passive"))
    )
    (net (code "136") (name "Net-(K1A--)") (class "Default")
      (node (ref "D21") (pin "A") (pinfunction "A_A") (pintype "passive"))
      (node (ref "K1") (pin "8") (pinfunction "-_8") (pintype "passive"))
      (node (ref "Q32") (pin "3") (pinfunction "D_3") (pintype "passive"))
      (node (ref "R138") (pin "1") (pinfunction "1_1") (pintype "passive"))
    )
    (net (code "137") (name "Net-(K1B-S)") (class "Default")
      (node (ref "K1") (pin "4") (pinfunction "S_4") (pintype "passive"))
      (node (ref "X4") (pin "4") (pinfunction "1_4") (pintype "passive"))
    )
    (net (code "138") (name "Net-(K1C-S)") (class "Default")
      (node (ref "K1") (pin "5") (pinfunction "S_5") (pintype "passive"))
      (node (ref "X4") (pin "5") (pinfunction "1_5") (pintype "passive"))
    )
    (net (code "139") (name "Net-(LED1-C)") (class "Default")
      (node (ref "LED1") (pin "CC") (pinfunction "C_CC") (pintype "passive"))
      (node (ref "R90") (pin "1") (pinfunction "1_1") (pintype "passive"))
    )
    (net (code "140") (name "Net-(LED2A-C)") (class "Default")
      (node (ref "LED2") (pin "BC") (pinfunction "C_BC") (pintype "passive"))
      (node (ref "R138") (pin "2") (pinfunction "2_2") (pintype "passive"))
    )
    (net (code "141") (name "Net-(LED2B-C)") (class "Default")
      (node (ref "LED2") (pin "TC") (pinfunction "C_TC") (pintype "passive"))
      (node (ref "R93") (pin "2") (pinfunction "2_2") (pintype "passive"))
    )
    (net (code "142") (name "Net-(LED3A-C)") (class "Default")
      (node (ref "LED3") (pin "BC") (pinfunction "C_BC") (pintype "passive"))
      (node (ref "R113") (pin "2") (pinfunction "2_2") (pintype "passive"))
    )
    (net (code "143") (name "Net-(LED3B-C)") (class "Default")
      (node (ref "LED3") (pin "TC") (pinfunction "C_TC") (pintype "passive"))
      (node (ref "R108") (pin "1") (pinfunction "1_1") (pintype "passive"))
    )
    (net (code "144") (name "Net-(LED4-PadA)") (class "Default")
      (node (ref "LED4") (pin "A") (pinfunction "A_A") (pintype "passive"))
      (node (ref "R139") (pin "1") (pinfunction "1_1") (pintype "passive"))
    )
    (net (code "145") (name "Net-(Q1-G)") (class "Default")
      (node (ref "D6") (pin "C") (pinfunction "C_C") (pintype "passive"))
      (node (ref "D7") (pin "A") (pinfunction "A_A") (pintype "passive"))
      (node (ref "Q1") (pin "1") (pinfunction "G_1") (pintype "passive"))
      (node (ref "R10") (pin "1") (pinfunction "1_1") (pintype "passive"))
    )
    (net (code "146") (name "Net-(Q2-E)") (class "Default")
      (node (ref "Q2") (pin "3") (pinfunction "E_3") (pintype "passive"))
      (node (ref "R13") (pin "2") (pinfunction "2_2") (pintype "passive"))
    )
    (net (code "147") (name "Net-(Q3-PadB)") (class "Default")
      (node (ref "Q3") (pin "B") (pinfunction "B_B") (pintype "passive"))
      (node (ref "R15") (pin "2") (pinfunction "2_2") (pintype "passive"))
    )
    (net (code "148") (name "Net-(Q4-B)") (class "Default")
      (node (ref "D9") (pin "A") (pinfunction "A_A") (pintype "passive"))
      (node (ref "Q4") (pin "1") (pinfunction "B_1") (pintype "passive"))
      (node (ref "R21") (pin "2") (pinfunction "2_2") (pintype "passive"))
      (node (ref "R22") (pin "1") (pinfunction "1_1") (pintype "passive"))
    )
    (net (code "149") (name "Net-(Q4-E)") (class "Default")
      (node (ref "D6") (pin "A") (pinfunction "A_A") (pintype "passive"))
      (node (ref "Q4") (pin "3") (pinfunction "E_3") (pintype "passive"))
    )
    (net (code "150") (name "Net-(Q5-G)") (class "Default")
      (node (ref "D8") (pin "A") (pinfunction "A_A") (pintype "passive"))
      (node (ref "Q3") (pin "C") (pinfunction "C_C") (pintype "passive"))
      (node (ref "Q5") (pin "1") (pinfunction "G_1") (pintype "passive"))
      (node (ref "R16") (pin "2") (pinfunction "2_2") (pintype "passive"))
    )
    (net (code "151") (name "Net-(Q5-S)") (class "Default")
      (node (ref "Q5") (pin "3") (pinfunction "S_3") (pintype "passive"))
      (node (ref "R11") (pin "1") (pinfunction "1_1") (pintype "passive"))
      (node (ref "R12") (pin "1") (pinfunction "1_1") (pintype "passive"))
      (node (ref "R15") (pin "1") (pinfunction "1_1") (pintype "passive"))
      (node (ref "R16") (pin "1") (pinfunction "1_1") (pintype "passive"))
    )
    (net (code "152") (name "Net-(Q6-E)") (class "Default")
      (node (ref "Q6") (pin "3") (pinfunction "E_3") (pintype "passive"))
      (node (ref "R26") (pin "1") (pinfunction "1_1") (pintype "passive"))
    )
    (net (code "153") (name "Net-(Q7-PadE)") (class "Default")
      (node (ref "Q7") (pin "E") (pinfunction "E_E") (pintype "passive"))
      (node (ref "R19") (pin "1") (pinfunction "1_1") (pintype "passive"))
    )
    (net (code "154") (name "Net-(Q8-PadE)") (class "Default")
      (node (ref "Q8") (pin "E") (pinfunction "E_E") (pintype "passive"))
      (node (ref "R20") (pin "1") (pinfunction "1_1") (pintype "passive"))
    )
    (net (code "155") (name "Net-(Q9-PadB)") (class "Default")
      (node (ref "Q9") (pin "B") (pinfunction "B_B") (pintype "passive"))
      (node (ref "R18") (pin "1") (pinfunction "1_1") (pintype "passive"))
      (node (ref "R27") (pin "2") (pinfunction "2_2") (pintype "passive"))
      (node (ref "R28") (pin "2") (pinfunction "2_2") (pintype "passive"))
    )
    (net (code "156") (name "Net-(Q9-PadE)") (class "Default")
      (node (ref "Q9") (pin "E") (pinfunction "E_E") (pintype "passive"))
      (node (ref "R34") (pin "2") (pinfunction "2_2") (pintype "passive"))
    )
    (net (code "157") (name "Net-(Q10-PadC)") (class "Default")
      (node (ref "Q10") (pin "C") (pinfunction "C_C") (pintype "passive"))
      (node (ref "Q7") (pin "B") (pinfunction "B_B") (pintype "passive"))
      (node (ref "Q7") (pin "C") (pinfunction "C_C") (pintype "passive"))
      (node (ref "Q8") (pin "B") (pinfunction "B_B") (pintype "passive"))
    )
    (net (code "158") (name "Net-(Q10-PadE)") (class "Default")
      (node (ref "Q10") (pin "E") (pinfunction "E_E") (pintype "passive"))
      (node (ref "R35") (pin "2") (pinfunction "2_2") (pintype "passive"))
    )
    (net (code "159") (name "Net-(Q11-S-Pad1)") (class "Default")
      (node (ref "Q11") (pin "1") (pinfunction "S_1") (pintype "passive"))
      (node (ref "Q11") (pin "2") (pinfunction "S_2") (pintype "passive"))
      (node (ref "Q11") (pin "3") (pinfunction "S_3") (pintype "passive"))
      (node (ref "R62") (pin "2") (pinfunction "2_2") (pintype "passive"))
    )
    (net (code "160") (name "Net-(Q12-S-Pad1)") (class "Default")
      (node (ref "Q12") (pin "1") (pinfunction "S_1") (pintype "passive"))
      (node (ref "Q12") (pin "2") (pinfunction "S_2") (pintype "passive"))
      (node (ref "Q12") (pin "3") (pinfunction "S_3") (pintype "passive"))
      (node (ref "R55") (pin "1") (pinfunction "1_1") (pintype "passive"))
      (node (ref "R61") (pin "2") (pinfunction "2_2") (pintype "passive"))
    )
    (net (code "161") (name "Net-(Q13-S-Pad1)") (class "Default")
      (node (ref "Q13") (pin "1") (pinfunction "S_1") (pintype "passive"))
      (node (ref "Q13") (pin "2") (pinfunction "S_2") (pintype "passive"))
      (node (ref "Q13") (pin "3") (pinfunction "S_3") (pintype "passive"))
      (node (ref "R58") (pin "1") (pinfunction "1_1") (pintype "passive"))
      (node (ref "R60") (pin "1") (pinfunction "1_1") (pintype "passive"))
    )
    (net (code "162") (name "Net-(Q16-PadB)") (class "Default")
      (node (ref "Q16") (pin "B") (pinfunction "B_B") (pintype "passive"))
      (node (ref "R56") (pin "1") (pinfunction "1_1") (pintype "passive"))
    )
    (net (code "163") (name "Net-(Q17-PadB)") (class "Default")
      (node (ref "Q17") (pin "B") (pinfunction "B_B") (pintype "passive"))
      (node (ref "R57") (pin "1") (pinfunction "1_1") (pintype "passive"))
    )
    (net (code "164") (name "Net-(Q19-D)") (class "Default")
      (node (ref "Q19") (pin "3") (pinfunction "D_3") (pintype "passive"))
      (node (ref "R94") (pin "2") (pinfunction "2_2") (pintype "passive"))
    )
    (net (code "165") (name "Net-(Q20-PadA2)") (class "Default")
      (node (ref "Q20") (pin "A2") (pinfunction "A2_A2") (pintype "passive"))
      (node (ref "R111") (pin "2") (pinfunction "2_2") (pintype "passive"))
    )
    (net (code "166") (name "Net-(Q20-PadG)") (class "Default")
      (node (ref "Q20") (pin "G") (pinfunction "G_G") (pintype "passive"))
      (node (ref "Q22") (pin "C") (pinfunction "C_C") (pintype "passive"))
      (node (ref "R104") (pin "1") (pinfunction "1_1") (pintype "passive"))
    )
    (net (code "167") (name "Net-(Q22-PadE)") (class "Default")
      (node (ref "Q22") (pin "E") (pinfunction "E_E") (pintype "passive"))
      (node (ref "R117") (pin "2") (pinfunction "2_2") (pintype "passive"))
    )
    (net (code "168") (name "Net-(Q23-D)") (class "Default")
      (node (ref "Q23") (pin "3") (pinfunction "D_3") (pintype "passive"))
      (node (ref "R108") (pin "2") (pinfunction "2_2") (pintype "passive"))
    )
    (net (code "169") (name "Net-(Q24-D)") (class "Default")
      (node (ref "Q24") (pin "3") (pinfunction "D_3") (pintype "passive"))
      (node (ref "R113") (pin "1") (pinfunction "1_1") (pintype "passive"))
    )
    (net (code "170") (name "Net-(Q26-PadE)") (class "Default")
      (node (ref "Q26") (pin "E") (pinfunction "E_E") (pintype "passive"))
      (node (ref "R124") (pin "1") (pinfunction "1_1") (pintype "passive"))
    )
    (net (code "171") (name "Net-(Q29-PadB)") (class "Default")
      (node (ref "Q29") (pin "B") (pinfunction "B_B") (pintype "passive"))
      (node (ref "R132") (pin "1") (pinfunction "1_1") (pintype "passive"))
      (node (ref "R135") (pin "2") (pinfunction "2_2") (pintype "passive"))
    )
    (net (code "172") (name "Net-(Q30-PadC)") (class "Default")
      (node (ref "Q30") (pin "C") (pinfunction "C_C") (pintype "passive"))
      (node (ref "R129") (pin "1") (pinfunction "1_1") (pintype "passive"))
    )
    (net (code "173") (name "Net-(Q31-D)") (class "Default")
      (node (ref "Q31") (pin "3") (pinfunction "D_3") (pintype "passive"))
      (node (ref "R139") (pin "2") (pinfunction "2_2") (pintype "passive"))
    )
    (net (code "174") (name "Net-(R44-Pad2)") (class "Default")
      (node (ref "R44") (pin "2") (pinfunction "2_2") (pintype "passive"))
      (node (ref "R45") (pin "1") (pinfunction "1_1") (pintype "passive"))
    )
    (net (code "175") (name "Net-(R52-Pad1)") (class "Default")
      (node (ref "R52") (pin "1") (pinfunction "1_1") (pintype "passive"))
      (node (ref "R62") (pin "2S") (pinfunction "2S_2S") (pintype "passive"))
    )
    (net (code "176") (name "Net-(R62-Pad1S)") (class "Default")
      (node (ref "R62") (pin "1S") (pinfunction "1S_1S") (pintype "passive"))
      (node (ref "R66") (pin "1") (pinfunction "1_1") (pintype "passive"))
    )
    (net (code "177") (name "Net-(R67-Pad2)") (class "Default")
      (node (ref "R67") (pin "2") (pinfunction "2_2") (pintype "passive"))
      (node (ref "R72") (pin "2S") (pinfunction "2S_2S") (pintype "passive"))
    )
    (net (code "178") (name "Net-(R72-Pad1S)") (class "Default")
      (node (ref "R72") (pin "1S") (pinfunction "1S_1S") (pintype "passive"))
      (node (ref "R73") (pin "2") (pinfunction "2_2") (pintype "passive"))
    )
    (net (code "179") (name "Net-(R97-Pad2)") (class "Default")
      (node (ref "R97") (pin "2") (pinfunction "2_2") (pintype "passive"))
      (node (ref "R98") (pin "1") (pinfunction "1_1") (pintype "passive"))
    )
    (net (code "180") (name "Net-(R98-Pad2)") (class "Default")
      (node (ref "R98") (pin "2") (pinfunction "2_2") (pintype "passive"))
      (node (ref "X4") (pin "1") (pinfunction "1_1") (pintype "passive"))
    )
    (net (code "181") (name "Net-(R129-Pad2)") (class "Default")
      (node (ref "R129") (pin "2") (pinfunction "2_2") (pintype "passive"))
      (node (ref "R130") (pin "1") (pinfunction "1_1") (pintype "passive"))
    )
    (net (code "182") (name "Net-(X2E-1)") (class "Default")
      (node (ref "C1") (pin "1") (pinfunction "1_1") (pintype "passive"))
      (node (ref "R1") (pin "2") (pinfunction "2_2") (pintype "passive"))
      (node (ref "R2") (pin "1") (pinfunction "1_1") (pintype "passive"))
      (node (ref "R3") (pin "1") (pinfunction "1_1") (pintype "passive"))
      (node (ref "X2") (pin "5") (pinfunction "1_5") (pintype "passive"))
    )
    (net (code "183") (name "Net-(X2F-1)") (class "Default")
      (node (ref "JP1") (pin "NC") (pinfunction "NC_NC") (pintype "passive"))
      (node (ref "X2") (pin "6") (pinfunction "1_6") (pintype "passive"))
    )
    (net (code "184") (name "Net-(X2G-1)") (class "Default")
      (node (ref "JP2") (pin "NO") (pinfunction "NO_NO") (pintype "passive"))
      (node (ref "X2") (pin "7") (pinfunction "1_7") (pintype "passive"))
    )
    (net (code "185") (name "Net-(X2H-1)") (class "Default")
      (node (ref "JP2") (pin "NC") (pinfunction "NC_NC") (pintype "passive"))
      (node (ref "X2") (pin "8") (pinfunction "1_8") (pintype "passive"))
    )
    (net (code "186") (name "Net-(X3B-1)") (class "Default")
      (node (ref "FB7") (pin "1") (pinfunction "1_1") (pintype "passive"))
      (node (ref "X3") (pin "2") (pinfunction "1_2") (pintype "passive"))
    )
    (net (code "187") (name "OE_GREEN") (class "Default")
      (node (ref "IC15") (pin "27") (pinfunction "GPA6_27") (pintype "bidirectional"))
      (node (ref "LED1") (pin "GREEN") (pinfunction "AG_GREEN") (pintype "passive"))
    )
    (net (code "188") (name "OE_RED") (class "Default")
      (node (ref "IC15") (pin "28") (pinfunction "GPA7_28") (pintype "bidirectional"))
      (node (ref "LED1") (pin "RED") (pinfunction "AR_RED") (pintype "passive"))
    )
    (net (code "189") (name "OE_SYNC") (class "Default")
      (node (ref "IC5") (pin "4") (pinfunction "A2_4") (pintype "input"))
      (node (ref "X1") (pin "6") (pinfunction "1_6") (pintype "passive"))
    )
    (net (code "190") (name "OE_TRIG") (class "Default")
      (node (ref "IC14") (pin "1") (pinfunction "CLK_1") (pintype "input"))
      (node (ref "IC5") (pin "13") (pinfunction "B2_13") (pintype "output"))
    )
    (net (code "191") (name "OUTC+") (class "Default")
      (node (ref "C77") (pin "+") (pinfunction "+_+") (pintype "passive"))
      (node (ref "C78") (pin "1") (pinfunction "1_1") (pintype "passive"))
      (node (ref "C79") (pin "1") (pinfunction "1_1") (pintype "passive"))
      (node (ref "J1") (pin "1") (pinfunction "1_1") (pintype "passive"))
      (node (ref "J1") (pin "NC1") (pinfunction "1_NC1") (pintype "passive"))
      (node (ref "J1") (pin "NC2") (pinfunction "1_NC2") (pintype "passive"))
      (node (ref "J1") (pin "NC3") (pinfunction "1_NC3") (pintype "passive"))
      (node (ref "J1") (pin "NC4") (pinfunction "1_NC4") (pintype "passive"))
      (node (ref "X5") (pin "1") (pinfunction "1_1") (pintype "passive"))
      (node (ref "X5") (pin "2") (pinfunction "1_2") (pintype "passive"))
      (node (ref "X5") (pin "3") (pinfunction "1_3") (pintype "passive"))
      (node (ref "X5") (pin "4") (pinfunction "1_4") (pintype "passive"))
      (node (ref "X5") (pin "5") (pinfunction "1_5") (pintype "passive"))
    )
    (net (code "192") (name "OUTC-") (class "Default")
      (node (ref "C77") (pin "-") (pinfunction "-_-") (pintype "passive"))
      (node (ref "C78") (pin "2") (pinfunction "2_2") (pintype "passive"))
      (node (ref "C79") (pin "2") (pinfunction "2_2") (pintype "passive"))
      (node (ref "J2") (pin "1") (pinfunction "1_1") (pintype "passive"))
      (node (ref "J2") (pin "NC1") (pinfunction "1_NC1") (pintype "passive"))
      (node (ref "J2") (pin "NC2") (pinfunction "1_NC2") (pintype "passive"))
      (node (ref "J2") (pin "NC3") (pinfunction "1_NC3") (pintype "passive"))
      (node (ref "J2") (pin "NC4") (pinfunction "1_NC4") (pintype "passive"))
      (node (ref "X5") (pin "16") (pinfunction "1_16") (pintype "passive"))
      (node (ref "X5") (pin "17") (pinfunction "1_17") (pintype "passive"))
      (node (ref "X5") (pin "18") (pinfunction "1_18") (pintype "passive"))
      (node (ref "X5") (pin "19") (pinfunction "1_19") (pintype "passive"))
      (node (ref "X5") (pin "20") (pinfunction "1_20") (pintype "passive"))
    )
    (net (code "193") (name "OUTF+") (class "Default")
      (node (ref "F2") (pin "2") (pinfunction "2_2") (pintype "passive"))
      (node (ref "Q20") (pin "A1") (pinfunction "A1_A1") (pintype "passive"))
      (node (ref "R104") (pin "2") (pinfunction "2_2") (pintype "passive"))
      (node (ref "X5") (pin "10") (pinfunction "1_10") (pintype "passive"))
      (node (ref "X5") (pin "6") (pinfunction "1_6") (pintype "passive"))
      (node (ref "X5") (pin "7") (pinfunction "1_7") (pintype "passive"))
      (node (ref "X5") (pin "8") (pinfunction "1_8") (pintype "passive"))
      (node (ref "X5") (pin "9") (pinfunction "1_9") (pintype "passive"))
    )
    (net (code "194") (name "PE") (class "Default")
      (node (ref "C13") (pin "2") (pinfunction "2_2") (pintype "passive"))
      (node (ref "C18") (pin "2") (pinfunction "2_2") (pintype "passive"))
      (node (ref "C19") (pin "2") (pinfunction "2_2") (pintype "passive"))
      (node (ref "C2") (pin "2") (pinfunction "2_2") (pintype "passive"))
      (node (ref "C71") (pin "2") (pinfunction "2_2") (pintype "passive"))
      (node (ref "C75") (pin "1") (pinfunction "1_1") (pintype "passive"))
      (node (ref "C9") (pin "2") (pinfunction "2_2") (pintype "passive"))
      (node (ref "X3") (pin "3") (pinfunction "1_3") (pintype "passive"))
      (node (ref "X4") (pin "3") (pinfunction "1_3") (pintype "passive"))
    )
    (net (code "195") (name "POST_OE") (class "Default")
      (node (ref "Q18") (pin "3") (pinfunction "D_3") (pintype "passive"))
      (node (ref "R35") (pin "1") (pinfunction "1_1") (pintype "passive"))
    )
    (net (code "196") (name "POST_OUT+") (class "Default")
      (node (ref "C24") (pin "2") (pinfunction "2_2") (pintype "passive"))
      (node (ref "C29") (pin "1") (pinfunction "1_1") (pintype "passive"))
      (node (ref "C35") (pin "1") (pinfunction "1_1") (pintype "passive"))
      (node (ref "D5") (pin "A") (pinfunction "A_A") (pintype "passive"))
      (node (ref "F1") (pin "1") (pinfunction "1_1") (pintype "passive"))
      (node (ref "Q1") (pin "3") (pinfunction "S_3") (pintype "passive"))
      (node (ref "Q3") (pin "E") (pinfunction "E_E") (pintype "passive"))
      (node (ref "R1") (pin "1") (pinfunction "1_1") (pintype "passive"))
      (node (ref "R10") (pin "2") (pinfunction "2_2") (pintype "passive"))
      (node (ref "R11") (pin "2") (pinfunction "2_2") (pintype "passive"))
      (node (ref "R12") (pin "2") (pinfunction "2_2") (pintype "passive"))
      (node (ref "R18") (pin "2") (pinfunction "2_2") (pintype "passive"))
      (node (ref "ZD1") (pin "A") (pinfunction "A_A") (pintype "passive"))
    )
    (net (code "197") (name "POST_OUT-") (class "Default")
      (node (ref "C25") (pin "1") (pinfunction "1_1") (pintype "passive"))
      (node (ref "C26") (pin "2") (pinfunction "2_2") (pintype "passive"))
      (node (ref "C74") (pin "-") (pinfunction "-_-") (pintype "passive"))
      (node (ref "C75") (pin "2") (pinfunction "2_2") (pintype "passive"))
      (node (ref "C76") (pin "2") (pinfunction "2_2") (pintype "passive"))
      (node (ref "D15") (pin "A") (pinfunction "A_A") (pintype "passive"))
      (node (ref "D20") (pin "1") (pinfunction "A_1") (pintype "passive"))
      (node (ref "D20") (pin "2") (pinfunction "A_2") (pintype "passive"))
      (node (ref "K1") (pin "7") (pinfunction "O_7") (pintype "passive"))
      (node (ref "Q11") (pin "MB") (pinfunction "D_MB") (pintype "passive"))
      (node (ref "Q12") (pin "MB") (pinfunction "D_MB") (pintype "passive"))
      (node (ref "Q13") (pin "MB") (pinfunction "D_MB") (pintype "passive"))
      (node (ref "Q30") (pin "E") (pinfunction "E_E") (pintype "passive"))
      (node (ref "R133") (pin "1") (pinfunction "1_1") (pintype "passive"))
      (node (ref "R136") (pin "1") (pinfunction "1_1") (pintype "passive"))
      (node (ref "X5") (pin "11") (pinfunction "1_11") (pintype "passive"))
      (node (ref "X5") (pin "12") (pinfunction "1_12") (pintype "passive"))
      (node (ref "X5") (pin "13") (pinfunction "1_13") (pintype "passive"))
      (node (ref "X5") (pin "14") (pinfunction "1_14") (pintype "passive"))
      (node (ref "X5") (pin "15") (pinfunction "1_15") (pintype "passive"))
    )
    (net (code "198") (name "PREG_IN+") (class "Default")
      (node (ref "FB6") (pin "1") (pinfunction "1_1") (pintype "passive"))
      (node (ref "JP2") (pin "COM") (pinfunction "COM_COM") (pintype "passive"))
      (node (ref "X3") (pin "1") (pinfunction "1_1") (pintype "passive"))
    )
    (net (code "199") (name "PREG_IN-") (class "Default")
      (node (ref "C19") (pin "1") (pinfunction "1_1") (pintype "passive"))
      (node (ref "FB7") (pin "2") (pinfunction "2_2") (pintype "passive"))
      (node (ref "Q5") (pin "2") (pinfunction "D_2") (pintype "passive"))
      (node (ref "SH1") (pin "P$1") (pinfunction "GND_A_P$1") (pintype "bidirectional"))
      (node (ref "SH2") (pin "P$1") (pinfunction "GND_A_P$1") (pintype "bidirectional"))
    )
    (net (code "200") (name "PREG_OUT+") (class "Default")
      (node (ref "C18") (pin "1") (pinfunction "1_1") (pintype "passive"))
      (node (ref "FB6") (pin "2") (pinfunction "2_2") (pintype "passive"))
      (node (ref "Q1") (pin "2") (pinfunction "D_2") (pintype "passive"))
    )
    (net (code "201") (name "PREG_OUT-") (class "Default")
      (node (ref "Q2") (pin "1") (pinfunction "B_1") (pintype "passive"))
      (node (ref "R111") (pin "1") (pinfunction "1_1") (pintype "passive"))
      (node (ref "R72") (pin "1") (pinfunction "1_1") (pintype "passive"))
      (node (ref "SH1") (pin "P$2") (pinfunction "GND_B_P$2") (pintype "bidirectional"))
    )
    (net (code "202") (name "PRE_OE") (class "Default")
      (node (ref "IC14") (pin "2") (pinfunction "D_2") (pintype "input"))
      (node (ref "IC15") (pin "2") (pinfunction "GPB1_2") (pintype "bidirectional"))
      (node (ref "JP3") (pin "1") (pinfunction "1_1") (pintype "passive"))
    )
    (net (code "203") (name "PWRGOOD") (class "Default")
      (node (ref "IC1") (pin "5") (pinfunction "~{ERROR}_5") (pintype "input"))
      (node (ref "IC15") (pin "24") (pinfunction "GPA3_24") (pintype "bidirectional"))
      (node (ref "R6") (pin "2") (pinfunction "2_2") (pintype "passive"))
    )
    (net (code "204") (name "RSENSE") (class "Default")
      (node (ref "IC15") (pin "3") (pinfunction "GPB2_3") (pintype "bidirectional"))
      (node (ref "Q32") (pin "1") (pinfunction "G_1") (pintype "passive"))
      (node (ref "R140") (pin "2") (pinfunction "2_2") (pintype "passive"))
    )
    (net (code "205") (name "SCLK") (class "Default")
      (node (ref "IC15") (pin "12") (pinfunction "SCK_12") (pintype "input"))
      (node (ref "IC17") (pin "6") (pinfunction "SCLK_6") (pintype "input"))
      (node (ref "IC19") (pin "1") (pinfunction "SCLK_1") (pintype "input"))
      (node (ref "RN2") (pin "8") (pinfunction "2_8") (pintype "passive"))
    )
    (net (code "206") (name "SENSE+") (class "Default")
      (node (ref "C22") (pin "1") (pinfunction "1_1") (pintype "passive"))
      (node (ref "K1") (pin "3") (pinfunction "P_3") (pintype "passive"))
      (node (ref "R128") (pin "1") (pinfunction "1_1") (pintype "passive"))
      (node (ref "R30") (pin "2") (pinfunction "2_2") (pintype "passive"))
    )
    (net (code "207") (name "SENSE-") (class "Default")
      (node (ref "C28") (pin "1") (pinfunction "1_1") (pintype "passive"))
      (node (ref "K1") (pin "6") (pinfunction "P_6") (pintype "passive"))
      (node (ref "R134") (pin "2") (pinfunction "2_2") (pintype "passive"))
      (node (ref "R39") (pin "2") (pinfunction "2_2") (pintype "passive"))
    )
    (net (code "208") (name "SENSE_ERR") (class "Default")
      (node (ref "IC15") (pin "21") (pinfunction "GPA0_21") (pintype "bidirectional"))
      (node (ref "Q29") (pin "C") (pinfunction "C_C") (pintype "passive"))
      (node (ref "R131") (pin "1") (pinfunction "1_1") (pintype "passive"))
    )
    (net (code "209") (name "SENSE_PROT") (class "Default")
      (node (ref "Q27") (pin "C") (pinfunction "C_C") (pintype "passive"))
      (node (ref "Q8") (pin "C") (pinfunction "C_C") (pintype "passive"))
      (node (ref "Q9") (pin "C") (pinfunction "C_C") (pintype "passive"))
      (node (ref "R22") (pin "2") (pinfunction "2_2") (pintype "passive"))
      (node (ref "R31") (pin "2") (pinfunction "2_2") (pintype "passive"))
    )
    (net (code "210") (name "U_MON") (class "Default")
      (node (ref "IC8") (pin "7") (pinfunction "OUT_7") (pintype "output"))
      (node (ref "R109") (pin "1") (pinfunction "1_1") (pintype "passive"))
      (node (ref "R36") (pin "1") (pinfunction "1_1") (pintype "passive"))
      (node (ref "R37") (pin "1") (pinfunction "1_1") (pintype "passive"))
      (node (ref "R99") (pin "1") (pinfunction "1_1") (pintype "passive"))
    )
    (net (code "211") (name "U_SERVO") (class "Default")
      (node (ref "C27") (pin "2") (pinfunction "2_2") (pintype "passive"))
      (node (ref "D10") (pin "C") (pinfunction "C_C") (pintype "passive"))
      (node (ref "D11") (pin "A") (pinfunction "A_A") (pintype "passive"))
      (node (ref "IC8") (pin "1") (pinfunction "OUT_1") (pintype "output"))
      (node (ref "R102") (pin "1") (pinfunction "1_1") (pintype "passive"))
    )
    (net (code "212") (name "U_SET") (class "Default")
      (node (ref "IC17") (pin "3") (pinfunction "VOUTB_3") (pintype "output"))
      (node (ref "IC18") (pin "3") (pinfunction "NC_3") (pintype "bidirectional"))
      (node (ref "R103") (pin "1") (pinfunction "1_1") (pintype "passive"))
      (node (ref "R96") (pin "1") (pinfunction "1_1") (pintype "passive"))
    )
    (net (code "213") (name "U_SET_OUT") (class "Default")
      (node (ref "IC18") (pin "4") (pinfunction "COM_4") (pintype "bidirectional"))
      (node (ref "R33") (pin "1") (pinfunction "1_1") (pintype "passive"))
    )
    (net (code "214") (name "V+") (class "Default")
      (node (ref "C30") (pin "2") (pinfunction "2_2") (pintype "passive"))
      (node (ref "C31") (pin "2") (pinfunction "2_2") (pintype "passive"))
      (node (ref "C36") (pin "1") (pinfunction "1_1") (pintype "passive"))
      (node (ref "C37") (pin "1") (pinfunction "1_1") (pintype "passive"))
      (node (ref "C38") (pin "1") (pinfunction "1_1") (pintype "passive"))
      (node (ref "C39") (pin "2") (pinfunction "2_2") (pintype "passive"))
      (node (ref "C48") (pin "1") (pinfunction "1_1") (pintype "passive"))
      (node (ref "C49") (pin "1") (pinfunction "1_1") (pintype "passive"))
      (node (ref "C50") (pin "2") (pinfunction "2_2") (pintype "passive"))
      (node (ref "C64") (pin "1") (pinfunction "1_1") (pintype "passive"))
      (node (ref "C65") (pin "2") (pinfunction "2_2") (pintype "passive"))
      (node (ref "C66") (pin "2") (pinfunction "2_2") (pintype "passive"))
      (node (ref "FB2") (pin "P$2") (pinfunction "2_P$2") (pintype "passive"))
      (node (ref "IC10") (pin "4") (pinfunction "V+_4") (pintype "power_in"))
      (node (ref "IC11") (pin "8") (pinfunction "V+_8") (pintype "power_in"))
      (node (ref "IC12") (pin "4") (pinfunction "V+_4") (pintype "power_in"))
      (node (ref "IC13") (pin "14") (pinfunction "VDD_14") (pintype "power_in"))
      (node (ref "IC16") (pin "2") (pinfunction "VIN_2") (pintype "passive"))
      (node (ref "IC17") (pin "1") (pinfunction "VDD_1") (pintype "power_in"))
      (node (ref "IC18") (pin "5") (pinfunction "VDD_5") (pintype "power_in"))
      (node (ref "IC20") (pin "3") (pinfunction "V+_3") (pintype "power_in"))
      (node (ref "IC21") (pin "7") (pinfunction "C_7") (pintype "passive"))
      (node (ref "IC21") (pin "8") (pinfunction "V+_8") (pintype "power_in"))
      (node (ref "IC8") (pin "8") (pinfunction "V+_8") (pintype "power_in"))
      (node (ref "IC9") (pin "8") (pinfunction "V+_8") (pintype "power_in"))
      (node (ref "R101") (pin "1") (pinfunction "1_1") (pintype "passive"))
      (node (ref "R106") (pin "2") (pinfunction "2_2") (pintype "passive"))
      (node (ref "R121") (pin "1") (pinfunction "1_1") (pintype "passive"))
      (node (ref "R47") (pin "1") (pinfunction "1_1") (pintype "passive"))
      (node (ref "R48") (pin "1") (pinfunction "1_1") (pintype "passive"))
      (node (ref "R49") (pin "1") (pinfunction "1_1") (pintype "passive"))
    )
    (net (code "215") (name "V-") (class "Default")
      (node (ref "C33") (pin "2") (pinfunction "2_2") (pintype "passive"))
      (node (ref "C34") (pin "2") (pinfunction "2_2") (pintype "passive"))
      (node (ref "C40") (pin "1") (pinfunction "1_1") (pintype "passive"))
      (node (ref "C41") (pin "1") (pinfunction "1_1") (pintype "passive"))
      (node (ref "C42") (pin "1") (pinfunction "1_1") (pintype "passive"))
      (node (ref "C68") (pin "2") (pinfunction "2_2") (pintype "passive"))
      (node (ref "FB5") (pin "P$2") (pinfunction "2_P$2") (pintype "passive"))
      (node (ref "IC10") (pin "11") (pinfunction "V-_11") (pintype "power_in"))
      (node (ref "IC11") (pin "4") (pinfunction "V-_4") (pintype "power_in"))
      (node (ref "IC12") (pin "11") (pinfunction "V-_11") (pintype "power_in"))
      (node (ref "IC20") (pin "12") (pinfunction "GND_12") (pintype "power_in"))
      (node (ref "IC8") (pin "4") (pinfunction "V-_4") (pintype "power_in"))
      (node (ref "IC9") (pin "4") (pinfunction "V-_4") (pintype "power_in"))
      (node (ref "R120") (pin "1") (pinfunction "1_1") (pintype "passive"))
      (node (ref "R13") (pin "1") (pinfunction "1_1") (pintype "passive"))
    )
    (net (code "216") (name "unconnected-(IC1-SD-Pad3)") (class "Default")
      (node (ref "IC1") (pin "3") (pinfunction "SD_3") (pintype "input"))
    )
    (net (code "217") (name "unconnected-(IC1-SENSE-Pad2)") (class "Default")
      (node (ref "IC1") (pin "2") (pinfunction "SENSE_2") (pintype "input"))
    )
    (net (code "218") (name "unconnected-(IC1-VTAP-Pad6)") (class "Default")
      (node (ref "IC1") (pin "6") (pinfunction "VTAP_6") (pintype "input"))
    )
    (net (code "219") (name "unconnected-(IC3-Y2-Pad5)") (class "Default")
      (node (ref "IC3") (pin "5") (pinfunction "Y2_5") (pintype "output"))
    )
    (net (code "220") (name "unconnected-(IC13D-Z-Pad10)") (class "Default")
      (node (ref "IC13") (pin "10") (pinfunction "Z_10") (pintype "tri_state"))
    )
    (net (code "221") (name "unconnected-(IC14A-~{Q}-Pad3)") (class "Default")
      (node (ref "IC14") (pin "3") (pinfunction "~{Q}_3") (pintype "output"))
    )
    (net (code "222") (name "unconnected-(IC15-GPB7-Pad8)") (class "Default")
      (node (ref "IC15") (pin "8") (pinfunction "GPB7_8") (pintype "bidirectional"))
    )
    (net (code "223") (name "unconnected-(IC15-INTB-Pad19)") (class "Default")
      (node (ref "IC15") (pin "19") (pinfunction "INTB_19") (pintype "output"))
    )
    (net (code "224") (name "unconnected-(IC16-TEMP-Pad3)") (class "Default")
      (node (ref "IC16") (pin "3") (pinfunction "TEMP_3") (pintype "input"))
    )
    (net (code "225") (name "unconnected-(IC21A-BALANCE-Pad5)") (class "Default")
      (node (ref "IC21") (pin "5") (pinfunction "BALANCE_5") (pintype "input"))
    )
    (net (code "226") (name "~{DP_DRIVE}") (class "Default")
      (node (ref "Q6") (pin "1") (pinfunction "B_1") (pintype "passive"))
      (node (ref "R23") (pin "1") (pinfunction "1_1") (pintype "passive"))
      (node (ref "R94") (pin "1") (pinfunction "1_1") (pintype "passive"))
    )
    (net (code "227") (name "~{FAULT_OUT}") (class "Default")
      (node (ref "D17") (pin "A") (pinfunction "A_A") (pintype "passive"))
      (node (ref "D22") (pin "A") (pinfunction "A_A") (pintype "passive"))
      (node (ref "D23") (pin "A") (pinfunction "A_A") (pintype "passive"))
      (node (ref "IC14") (pin "6") (pinfunction "~{CLR}_6") (pintype "input"))
      (node (ref "Q31") (pin "1") (pinfunction "G_1") (pintype "passive"))
      (node (ref "R137") (pin "2") (pinfunction "2_2") (pintype "passive"))
    )
    (net (code "228") (name "~{FAULT}") (class "Default")
      (node (ref "D22") (pin "C") (pinfunction "C_C") (pintype "passive"))
      (node (ref "X2") (pin "4") (pinfunction "1_4") (pintype "passive"))
    )
    (net (code "229") (name "~{OVP_EN}") (class "Default")
      (node (ref "IC15") (pin "26") (pinfunction "GPA5_26") (pintype "bidirectional"))
      (node (ref "Q26") (pin "B") (pinfunction "B_B") (pintype "passive"))
    )
    (net (code "230") (name "~{OVP_FAULT}") (class "Default")
      (node (ref "D23") (pin "C") (pinfunction "C_C") (pintype "passive"))
      (node (ref "IC15") (pin "25") (pinfunction "GPA4_25") (pintype "bidirectional"))
      (node (ref "Q25") (pin "3") (pinfunction "D_3") (pintype "passive"))
      (node (ref "R121") (pin "2") (pinfunction "2_2") (pintype "passive"))
    )
    (net (code "231") (name "~{RESET}") (class "Default")
      (node (ref "D17") (pin "C") (pinfunction "C_C") (pintype "passive"))
      (node (ref "IC15") (pin "18") (pinfunction "~{RESET}_18") (pintype "input"))
      (node (ref "IC5") (pin "12") (pinfunction "B3_12") (pintype "output"))
    )
    (net (code "232") (name "~{SET_DP}") (class "Default")
      (node (ref "IC15") (pin "1") (pinfunction "GPB0_1") (pintype "bidirectional"))
      (node (ref "Q19") (pin "1") (pinfunction "G_1") (pintype "passive"))
      (node (ref "R92") (pin "2") (pinfunction "2_2") (pintype "passive"))
    )
  )
)
